# pork_pi.net
KiCad netlist of a schematic drawn in EAGLE
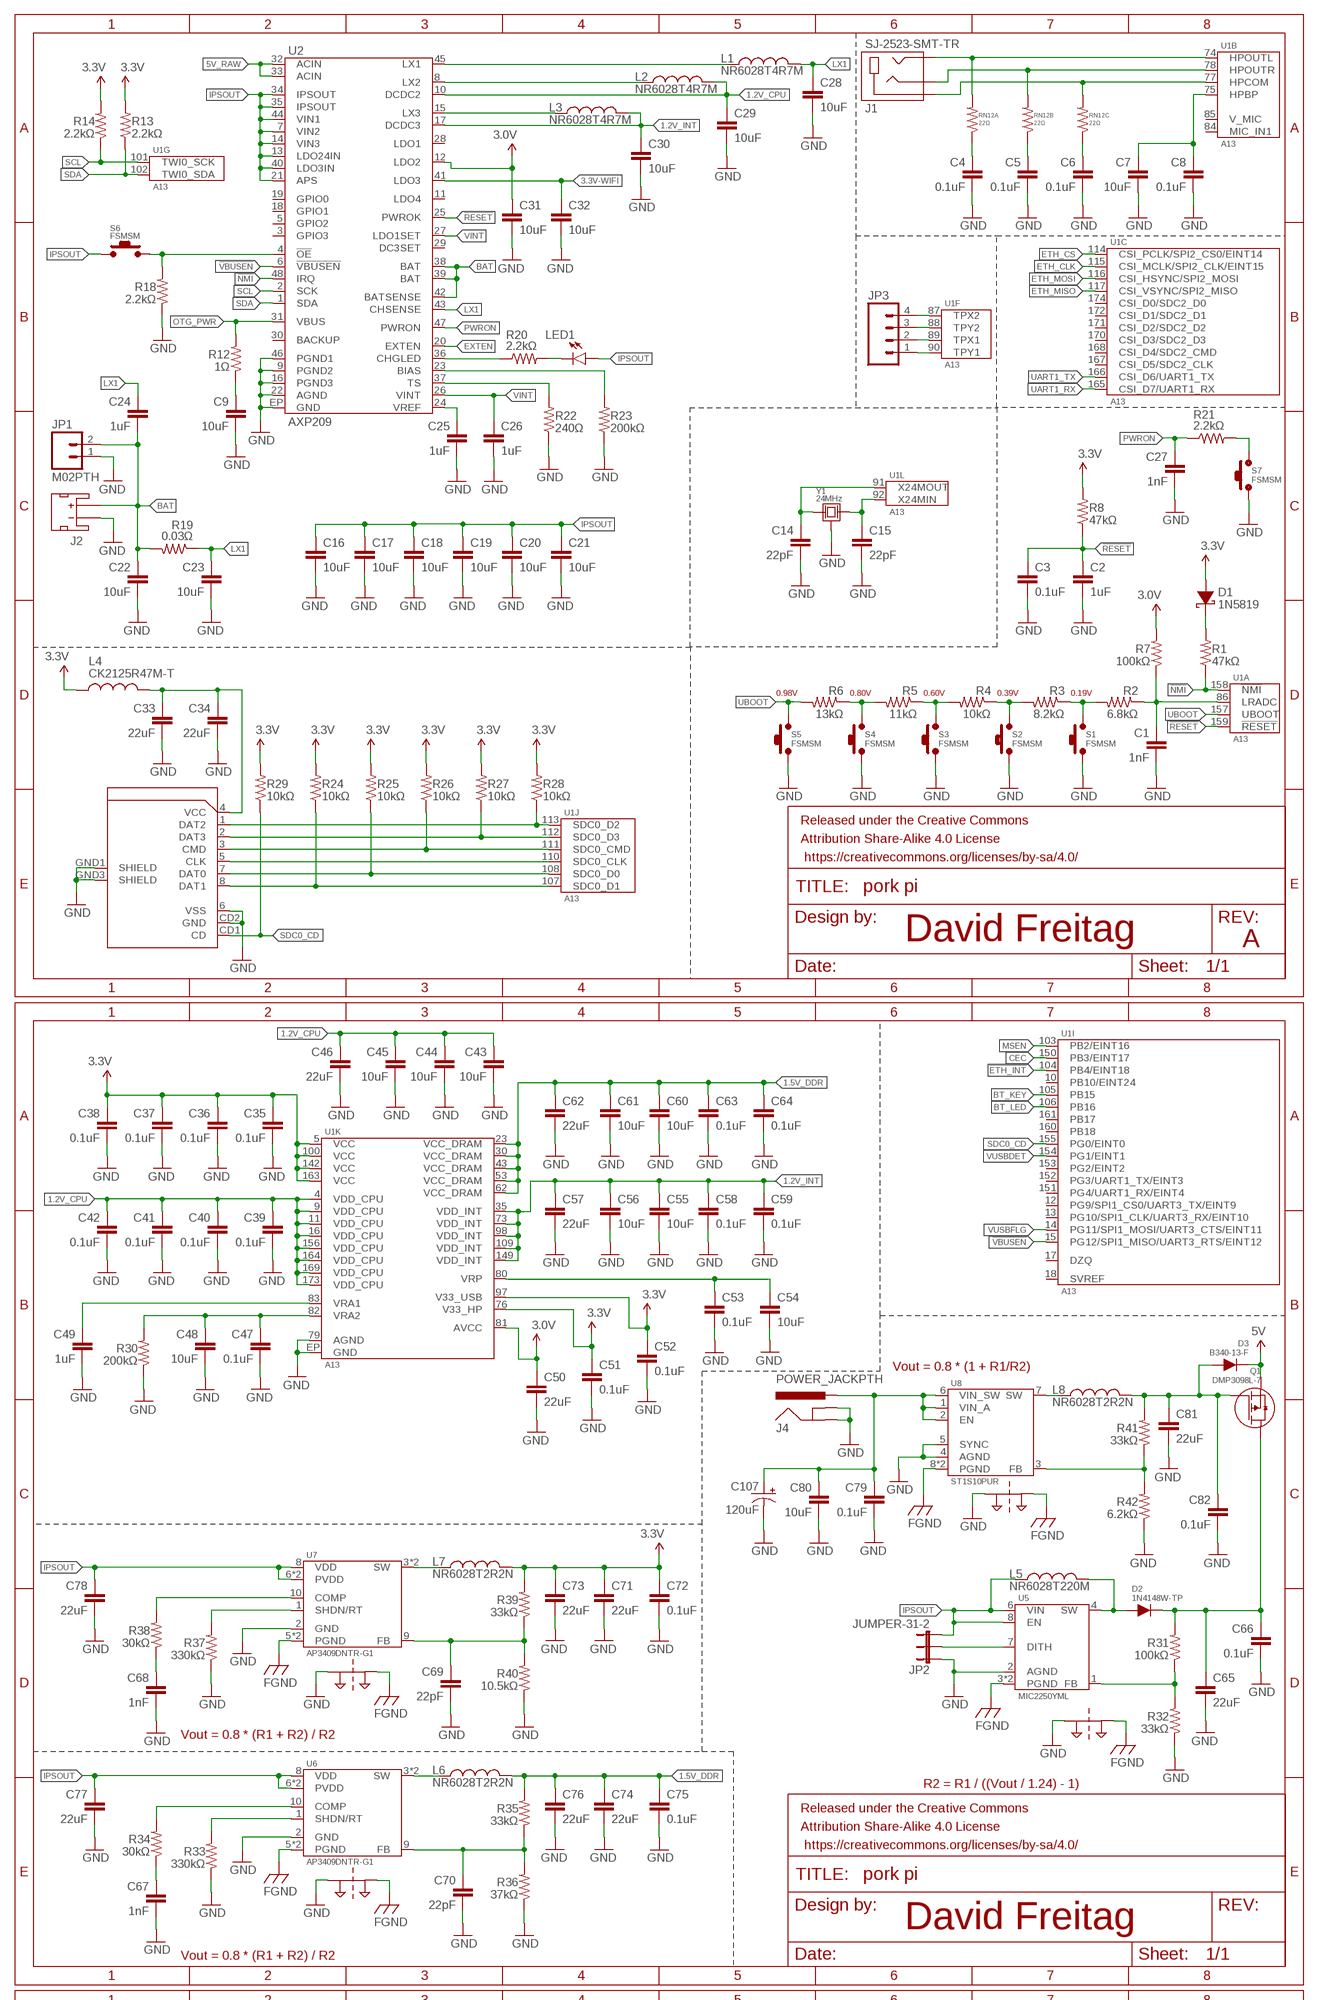
[diagram p0: schematic, sheet 1, part 1 of 3]
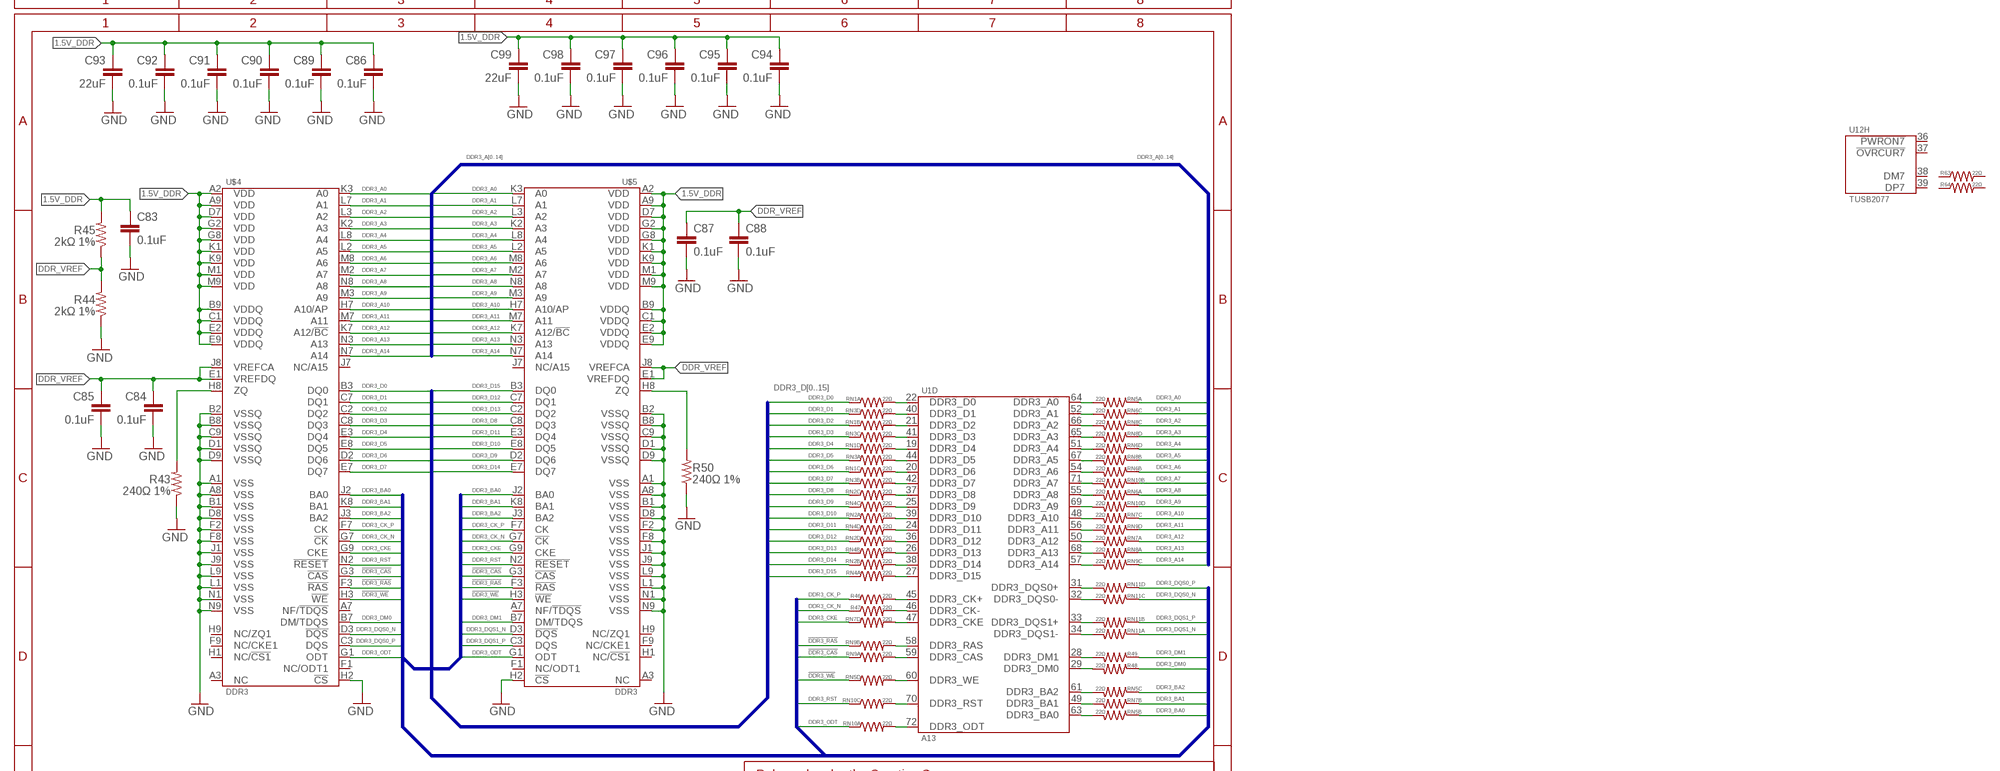
[diagram p1: schematic, sheet 1, part 2 of 3]
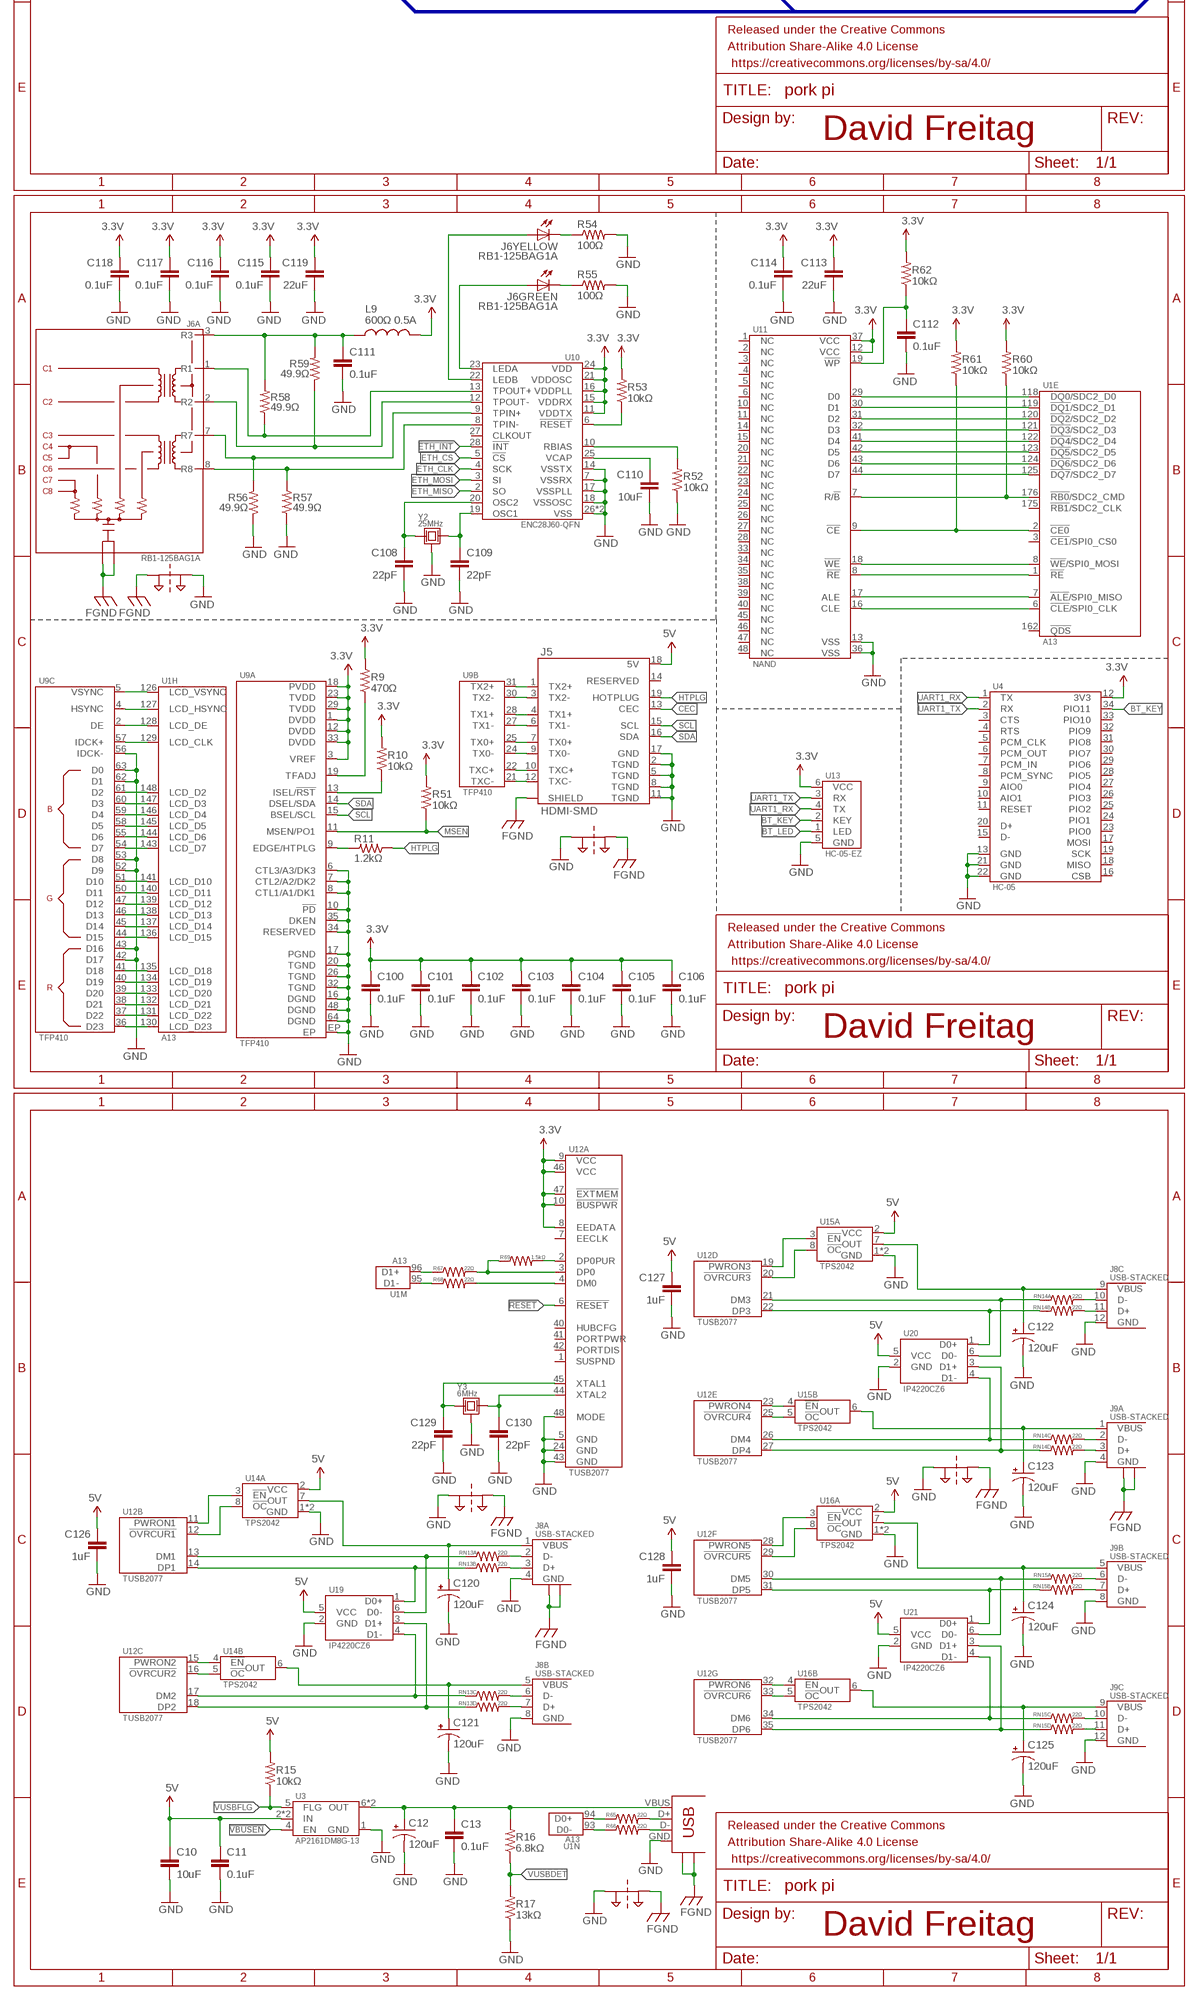
[diagram p2: schematic, sheet 1, part 3 of 3]

(export (version "E")
  (design (tool "Eeschema 10.0.6"))
  (components
    (comp (ref "C1")
      (value "1nF")
      (footprint "eagle-import:0402-CAP")
      (libsource (lib "eagle-import") (part "CAP0402-CAP"))
    )
    (comp (ref "C2")
      (value "1uF")
      (footprint "eagle-import:0402-CAP")
      (libsource (lib "eagle-import") (part "CAP0402-CAP"))
    )
    (comp (ref "C3")
      (value "0.1uF")
      (footprint "eagle-import:0402-CAP")
      (libsource (lib "eagle-import") (part "CAP0402-CAP"))
    )
    (comp (ref "C4")
      (value "0.1uF")
      (footprint "eagle-import:0402-CAP")
      (libsource (lib "eagle-import") (part "CAP0402-CAP"))
    )
    (comp (ref "C5")
      (value "0.1uF")
      (footprint "eagle-import:0402-CAP")
      (libsource (lib "eagle-import") (part "CAP0402-CAP"))
    )
    (comp (ref "C6")
      (value "0.1uF")
      (footprint "eagle-import:0402-CAP")
      (libsource (lib "eagle-import") (part "CAP0402-CAP"))
    )
    (comp (ref "C7")
      (value "10uF")
      (footprint "eagle-import:0603-CAP")
      (libsource (lib "eagle-import") (part "CAP0603-CAP"))
    )
    (comp (ref "C8")
      (value "0.1uF")
      (footprint "eagle-import:0402-CAP")
      (libsource (lib "eagle-import") (part "CAP0402-CAP"))
    )
    (comp (ref "C9")
      (value "10uF")
      (footprint "eagle-import:0603-CAP")
      (libsource (lib "eagle-import") (part "CAP0603-CAP"))
    )
    (comp (ref "C10")
      (value "10uF")
      (footprint "eagle-import:0603-CAP")
      (libsource (lib "eagle-import") (part "CAP0603-CAP"))
    )
    (comp (ref "C11")
      (value "0.1uF")
      (footprint "eagle-import:0402-CAP")
      (libsource (lib "eagle-import") (part "CAP0402-CAP"))
    )
    (comp (ref "C12")
      (value "120uF")
      (footprint "eagle-import:CAP_POLYMER-6.5X6.5")
      (fields (field (name "PARTNUM") "493-7371-1-ND"))
      (libsource (lib "eagle-import") (part "CAP_POL-POLYMER_6.5"))
    )
    (comp (ref "C13")
      (value "0.1uF")
      (footprint "eagle-import:0402-CAP")
      (libsource (lib "eagle-import") (part "CAP0402-CAP"))
    )
    (comp (ref "C14")
      (value "22pF")
      (footprint "eagle-import:0402-CAP")
      (libsource (lib "eagle-import") (part "CAP0402-CAP"))
    )
    (comp (ref "C15")
      (value "22pF")
      (footprint "eagle-import:0402-CAP")
      (libsource (lib "eagle-import") (part "CAP0402-CAP"))
    )
    (comp (ref "C16")
      (value "10uF")
      (footprint "eagle-import:0603-CAP")
      (libsource (lib "eagle-import") (part "CAP0603-CAP"))
    )
    (comp (ref "C17")
      (value "10uF")
      (footprint "eagle-import:0603-CAP")
      (libsource (lib "eagle-import") (part "CAP0603-CAP"))
    )
    (comp (ref "C18")
      (value "10uF")
      (footprint "eagle-import:0603-CAP")
      (libsource (lib "eagle-import") (part "CAP0603-CAP"))
    )
    (comp (ref "C19")
      (value "10uF")
      (footprint "eagle-import:0603-CAP")
      (libsource (lib "eagle-import") (part "CAP0603-CAP"))
    )
    (comp (ref "C20")
      (value "10uF")
      (footprint "eagle-import:0603-CAP")
      (libsource (lib "eagle-import") (part "CAP0603-CAP"))
    )
    (comp (ref "C21")
      (value "10uF")
      (footprint "eagle-import:0603-CAP")
      (libsource (lib "eagle-import") (part "CAP0603-CAP"))
    )
    (comp (ref "C22")
      (value "10uF")
      (footprint "eagle-import:0603-CAP")
      (libsource (lib "eagle-import") (part "CAP0603-CAP"))
    )
    (comp (ref "C23")
      (value "10uF")
      (footprint "eagle-import:0603-CAP")
      (libsource (lib "eagle-import") (part "CAP0603-CAP"))
    )
    (comp (ref "C24")
      (value "1uF")
      (footprint "eagle-import:0402-CAP")
      (libsource (lib "eagle-import") (part "CAP0402-CAP"))
    )
    (comp (ref "C25")
      (value "1uF")
      (footprint "eagle-import:0402-CAP")
      (libsource (lib "eagle-import") (part "CAP0402-CAP"))
    )
    (comp (ref "C26")
      (value "1uF")
      (footprint "eagle-import:0402-CAP")
      (libsource (lib "eagle-import") (part "CAP0402-CAP"))
    )
    (comp (ref "C27")
      (value "1nF")
      (footprint "eagle-import:0402-CAP")
      (libsource (lib "eagle-import") (part "CAP0402-CAP"))
    )
    (comp (ref "C28")
      (value "10uF")
      (footprint "eagle-import:0603-CAP")
      (libsource (lib "eagle-import") (part "CAP0603-CAP"))
    )
    (comp (ref "C29")
      (value "10uF")
      (footprint "eagle-import:0603-CAP")
      (libsource (lib "eagle-import") (part "CAP0603-CAP"))
    )
    (comp (ref "C30")
      (value "10uF")
      (footprint "eagle-import:0603-CAP")
      (libsource (lib "eagle-import") (part "CAP0603-CAP"))
    )
    (comp (ref "C31")
      (value "10uF")
      (footprint "eagle-import:0603-CAP")
      (libsource (lib "eagle-import") (part "CAP0603-CAP"))
    )
    (comp (ref "C32")
      (value "10uF")
      (footprint "eagle-import:0603-CAP")
      (libsource (lib "eagle-import") (part "CAP0603-CAP"))
    )
    (comp (ref "C33")
      (value "22uF")
      (footprint "eagle-import:0603-CAP")
      (libsource (lib "eagle-import") (part "CAP0603-CAP"))
    )
    (comp (ref "C34")
      (value "22uF")
      (footprint "eagle-import:0603-CAP")
      (libsource (lib "eagle-import") (part "CAP0603-CAP"))
    )
    (comp (ref "C35")
      (value "0.1uF")
      (footprint "eagle-import:0402-CAP")
      (libsource (lib "eagle-import") (part "CAP0402-CAP"))
    )
    (comp (ref "C36")
      (value "0.1uF")
      (footprint "eagle-import:0402-CAP")
      (libsource (lib "eagle-import") (part "CAP0402-CAP"))
    )
    (comp (ref "C37")
      (value "0.1uF")
      (footprint "eagle-import:0402-CAP")
      (libsource (lib "eagle-import") (part "CAP0402-CAP"))
    )
    (comp (ref "C38")
      (value "0.1uF")
      (footprint "eagle-import:0402-CAP")
      (libsource (lib "eagle-import") (part "CAP0402-CAP"))
    )
    (comp (ref "C39")
      (value "0.1uF")
      (footprint "eagle-import:0402-CAP")
      (libsource (lib "eagle-import") (part "CAP0402-CAP"))
    )
    (comp (ref "C40")
      (value "0.1uF")
      (footprint "eagle-import:0402-CAP")
      (libsource (lib "eagle-import") (part "CAP0402-CAP"))
    )
    (comp (ref "C41")
      (value "0.1uF")
      (footprint "eagle-import:0402-CAP")
      (libsource (lib "eagle-import") (part "CAP0402-CAP"))
    )
    (comp (ref "C42")
      (value "0.1uF")
      (footprint "eagle-import:0402-CAP")
      (libsource (lib "eagle-import") (part "CAP0402-CAP"))
    )
    (comp (ref "C43")
      (value "10uF")
      (footprint "eagle-import:0603-CAP")
      (libsource (lib "eagle-import") (part "CAP0603-CAP"))
    )
    (comp (ref "C44")
      (value "10uF")
      (footprint "eagle-import:0603-CAP")
      (libsource (lib "eagle-import") (part "CAP0603-CAP"))
    )
    (comp (ref "C45")
      (value "10uF")
      (footprint "eagle-import:0603-CAP")
      (libsource (lib "eagle-import") (part "CAP0603-CAP"))
    )
    (comp (ref "C46")
      (value "22uF")
      (footprint "eagle-import:0603-CAP")
      (libsource (lib "eagle-import") (part "CAP0603-CAP"))
    )
    (comp (ref "C47")
      (value "0.1uF")
      (footprint "eagle-import:0402-CAP")
      (libsource (lib "eagle-import") (part "CAP0402-CAP"))
    )
    (comp (ref "C48")
      (value "10uF")
      (footprint "eagle-import:0603-CAP")
      (libsource (lib "eagle-import") (part "CAP0603-CAP"))
    )
    (comp (ref "C49")
      (value "1uF")
      (footprint "eagle-import:0402-CAP")
      (libsource (lib "eagle-import") (part "CAP0402-CAP"))
    )
    (comp (ref "C50")
      (value "22uF")
      (footprint "eagle-import:0603-CAP")
      (libsource (lib "eagle-import") (part "CAP0603-CAP"))
    )
    (comp (ref "C51")
      (value "0.1uF")
      (footprint "eagle-import:0402-CAP")
      (libsource (lib "eagle-import") (part "CAP0402-CAP"))
    )
    (comp (ref "C52")
      (value "0.1uF")
      (footprint "eagle-import:0402-CAP")
      (libsource (lib "eagle-import") (part "CAP0402-CAP"))
    )
    (comp (ref "C53")
      (value "0.1uF")
      (footprint "eagle-import:0402-CAP")
      (libsource (lib "eagle-import") (part "CAP0402-CAP"))
    )
    (comp (ref "C54")
      (value "10uF")
      (footprint "eagle-import:0603-CAP")
      (libsource (lib "eagle-import") (part "CAP0603-CAP"))
    )
    (comp (ref "C55")
      (value "10uF")
      (footprint "eagle-import:0603-CAP")
      (libsource (lib "eagle-import") (part "CAP0603-CAP"))
    )
    (comp (ref "C56")
      (value "10uF")
      (footprint "eagle-import:0603-CAP")
      (libsource (lib "eagle-import") (part "CAP0603-CAP"))
    )
    (comp (ref "C57")
      (value "22uF")
      (footprint "eagle-import:0603-CAP")
      (libsource (lib "eagle-import") (part "CAP0603-CAP"))
    )
    (comp (ref "C58")
      (value "0.1uF")
      (footprint "eagle-import:0402-CAP")
      (libsource (lib "eagle-import") (part "CAP0402-CAP"))
    )
    (comp (ref "C59")
      (value "0.1uF")
      (footprint "eagle-import:0402-CAP")
      (libsource (lib "eagle-import") (part "CAP0402-CAP"))
    )
    (comp (ref "C60")
      (value "10uF")
      (footprint "eagle-import:0603-CAP")
      (libsource (lib "eagle-import") (part "CAP0603-CAP"))
    )
    (comp (ref "C61")
      (value "10uF")
      (footprint "eagle-import:0603-CAP")
      (libsource (lib "eagle-import") (part "CAP0603-CAP"))
    )
    (comp (ref "C62")
      (value "22uF")
      (footprint "eagle-import:0603-CAP")
      (libsource (lib "eagle-import") (part "CAP0603-CAP"))
    )
    (comp (ref "C63")
      (value "0.1uF")
      (footprint "eagle-import:0402-CAP")
      (libsource (lib "eagle-import") (part "CAP0402-CAP"))
    )
    (comp (ref "C64")
      (value "0.1uF")
      (footprint "eagle-import:0402-CAP")
      (libsource (lib "eagle-import") (part "CAP0402-CAP"))
    )
    (comp (ref "C65")
      (value "22uF")
      (footprint "eagle-import:0603-CAP")
      (libsource (lib "eagle-import") (part "CAP0603-CAP"))
    )
    (comp (ref "C66")
      (value "0.1uF")
      (footprint "eagle-import:0402-CAP")
      (libsource (lib "eagle-import") (part "CAP0402-CAP"))
    )
    (comp (ref "C67")
      (value "1nF")
      (footprint "eagle-import:0402-CAP")
      (libsource (lib "eagle-import") (part "CAP0402-CAP"))
    )
    (comp (ref "C68")
      (value "1nF")
      (footprint "eagle-import:0402-CAP")
      (libsource (lib "eagle-import") (part "CAP0402-CAP"))
    )
    (comp (ref "C69")
      (value "22pF")
      (footprint "eagle-import:0402-CAP")
      (libsource (lib "eagle-import") (part "CAP0402-CAP"))
    )
    (comp (ref "C70")
      (value "22pF")
      (footprint "eagle-import:0402-CAP")
      (libsource (lib "eagle-import") (part "CAP0402-CAP"))
    )
    (comp (ref "C71")
      (value "22uF")
      (footprint "eagle-import:0603-CAP")
      (libsource (lib "eagle-import") (part "CAP0603-CAP"))
    )
    (comp (ref "C72")
      (value "0.1uF")
      (footprint "eagle-import:0402-CAP")
      (libsource (lib "eagle-import") (part "CAP0402-CAP"))
    )
    (comp (ref "C73")
      (value "22uF")
      (footprint "eagle-import:0603-CAP")
      (libsource (lib "eagle-import") (part "CAP0603-CAP"))
    )
    (comp (ref "C74")
      (value "22uF")
      (footprint "eagle-import:0603-CAP")
      (libsource (lib "eagle-import") (part "CAP0603-CAP"))
    )
    (comp (ref "C75")
      (value "0.1uF")
      (footprint "eagle-import:0402-CAP")
      (libsource (lib "eagle-import") (part "CAP0402-CAP"))
    )
    (comp (ref "C76")
      (value "22uF")
      (footprint "eagle-import:0603-CAP")
      (libsource (lib "eagle-import") (part "CAP0603-CAP"))
    )
    (comp (ref "C77")
      (value "22uF")
      (footprint "eagle-import:0603-CAP")
      (libsource (lib "eagle-import") (part "CAP0603-CAP"))
    )
    (comp (ref "C78")
      (value "22uF")
      (footprint "eagle-import:0603-CAP")
      (libsource (lib "eagle-import") (part "CAP0603-CAP"))
    )
    (comp (ref "C79")
      (value "0.1uF")
      (footprint "eagle-import:0402-CAP")
      (libsource (lib "eagle-import") (part "CAP0402-CAP"))
    )
    (comp (ref "C80")
      (value "10uF")
      (footprint "eagle-import:0603-CAP")
      (libsource (lib "eagle-import") (part "CAP0603-CAP"))
    )
    (comp (ref "C81")
      (value "22uF")
      (footprint "eagle-import:0603-CAP")
      (libsource (lib "eagle-import") (part "CAP0603-CAP"))
    )
    (comp (ref "C82")
      (value "0.1uF")
      (footprint "eagle-import:0402-CAP")
      (libsource (lib "eagle-import") (part "CAP0402-CAP"))
    )
    (comp (ref "C83")
      (value "0.1uF")
      (footprint "eagle-import:0402-CAP")
      (libsource (lib "eagle-import") (part "CAP0402-CAP"))
    )
    (comp (ref "C84")
      (value "0.1uF")
      (footprint "eagle-import:0402-CAP")
      (libsource (lib "eagle-import") (part "CAP0402-CAP"))
    )
    (comp (ref "C85")
      (value "0.1uF")
      (footprint "eagle-import:0402-CAP")
      (libsource (lib "eagle-import") (part "CAP0402-CAP"))
    )
    (comp (ref "C86")
      (value "0.1uF")
      (footprint "eagle-import:0402-CAP")
      (libsource (lib "eagle-import") (part "CAP0402-CAP"))
    )
    (comp (ref "C87")
      (value "0.1uF")
      (footprint "eagle-import:0402-CAP")
      (libsource (lib "eagle-import") (part "CAP0402-CAP"))
    )
    (comp (ref "C88")
      (value "0.1uF")
      (footprint "eagle-import:0402-CAP")
      (libsource (lib "eagle-import") (part "CAP0402-CAP"))
    )
    (comp (ref "C89")
      (value "0.1uF")
      (footprint "eagle-import:0402-CAP")
      (libsource (lib "eagle-import") (part "CAP0402-CAP"))
    )
    (comp (ref "C90")
      (value "0.1uF")
      (footprint "eagle-import:0402-CAP")
      (libsource (lib "eagle-import") (part "CAP0402-CAP"))
    )
    (comp (ref "C91")
      (value "0.1uF")
      (footprint "eagle-import:0402-CAP")
      (libsource (lib "eagle-import") (part "CAP0402-CAP"))
    )
    (comp (ref "C92")
      (value "0.1uF")
      (footprint "eagle-import:0402-CAP")
      (libsource (lib "eagle-import") (part "CAP0402-CAP"))
    )
    (comp (ref "C93")
      (value "22uF")
      (footprint "eagle-import:0603-CAP")
      (libsource (lib "eagle-import") (part "CAP0603-CAP"))
    )
    (comp (ref "C94")
      (value "0.1uF")
      (footprint "eagle-import:0402-CAP")
      (libsource (lib "eagle-import") (part "CAP0402-CAP"))
    )
    (comp (ref "C95")
      (value "0.1uF")
      (footprint "eagle-import:0402-CAP")
      (libsource (lib "eagle-import") (part "CAP0402-CAP"))
    )
    (comp (ref "C96")
      (value "0.1uF")
      (footprint "eagle-import:0402-CAP")
      (libsource (lib "eagle-import") (part "CAP0402-CAP"))
    )
    (comp (ref "C97")
      (value "0.1uF")
      (footprint "eagle-import:0402-CAP")
      (libsource (lib "eagle-import") (part "CAP0402-CAP"))
    )
    (comp (ref "C98")
      (value "0.1uF")
      (footprint "eagle-import:0402-CAP")
      (libsource (lib "eagle-import") (part "CAP0402-CAP"))
    )
    (comp (ref "C99")
      (value "22uF")
      (footprint "eagle-import:0603-CAP")
      (libsource (lib "eagle-import") (part "CAP0603-CAP"))
    )
    (comp (ref "C100")
      (value "0.1uF")
      (footprint "eagle-import:0402-CAP")
      (libsource (lib "eagle-import") (part "CAP0402-CAP"))
    )
    (comp (ref "C101")
      (value "0.1uF")
      (footprint "eagle-import:0402-CAP")
      (libsource (lib "eagle-import") (part "CAP0402-CAP"))
    )
    (comp (ref "C102")
      (value "0.1uF")
      (footprint "eagle-import:0402-CAP")
      (libsource (lib "eagle-import") (part "CAP0402-CAP"))
    )
    (comp (ref "C103")
      (value "0.1uF")
      (footprint "eagle-import:0402-CAP")
      (libsource (lib "eagle-import") (part "CAP0402-CAP"))
    )
    (comp (ref "C104")
      (value "0.1uF")
      (footprint "eagle-import:0402-CAP")
      (libsource (lib "eagle-import") (part "CAP0402-CAP"))
    )
    (comp (ref "C105")
      (value "0.1uF")
      (footprint "eagle-import:0402-CAP")
      (libsource (lib "eagle-import") (part "CAP0402-CAP"))
    )
    (comp (ref "C106")
      (value "0.1uF")
      (footprint "eagle-import:0402-CAP")
      (libsource (lib "eagle-import") (part "CAP0402-CAP"))
    )
    (comp (ref "C107")
      (value "120uF")
      (footprint "eagle-import:CAP_POLYMER-6.5X6.5")
      (fields (field (name "PARTNUM") "493-7371-1-ND"))
      (libsource (lib "eagle-import") (part "CAP_POL-POLYMER_6.5"))
    )
    (comp (ref "C108")
      (value "22pF")
      (footprint "eagle-import:0402-CAP")
      (libsource (lib "eagle-import") (part "CAP0402-CAP"))
    )
    (comp (ref "C109")
      (value "22pF")
      (footprint "eagle-import:0402-CAP")
      (libsource (lib "eagle-import") (part "CAP0402-CAP"))
    )
    (comp (ref "C110")
      (value "10uF")
      (footprint "eagle-import:0603-CAP")
      (libsource (lib "eagle-import") (part "CAP0603-CAP"))
    )
    (comp (ref "C111")
      (value "0.1uF")
      (footprint "eagle-import:0402-CAP")
      (libsource (lib "eagle-import") (part "CAP0402-CAP"))
    )
    (comp (ref "C112")
      (value "0.1uF")
      (footprint "eagle-import:0402-CAP")
      (libsource (lib "eagle-import") (part "CAP0402-CAP"))
    )
    (comp (ref "C113")
      (value "22uF")
      (footprint "eagle-import:0603-CAP")
      (libsource (lib "eagle-import") (part "CAP0603-CAP"))
    )
    (comp (ref "C114")
      (value "0.1uF")
      (footprint "eagle-import:0402-CAP")
      (libsource (lib "eagle-import") (part "CAP0402-CAP"))
    )
    (comp (ref "C115")
      (value "0.1uF")
      (footprint "eagle-import:0402-CAP")
      (libsource (lib "eagle-import") (part "CAP0402-CAP"))
    )
    (comp (ref "C116")
      (value "0.1uF")
      (footprint "eagle-import:0402-CAP")
      (libsource (lib "eagle-import") (part "CAP0402-CAP"))
    )
    (comp (ref "C117")
      (value "0.1uF")
      (footprint "eagle-import:0402-CAP")
      (libsource (lib "eagle-import") (part "CAP0402-CAP"))
    )
    (comp (ref "C118")
      (value "0.1uF")
      (footprint "eagle-import:0402-CAP")
      (libsource (lib "eagle-import") (part "CAP0402-CAP"))
    )
    (comp (ref "C119")
      (value "22uF")
      (footprint "eagle-import:0603-CAP")
      (libsource (lib "eagle-import") (part "CAP0603-CAP"))
    )
    (comp (ref "C120")
      (value "120uF")
      (footprint "eagle-import:CAP_POLYMER-6.5X6.5")
      (fields (field (name "PARTNUM") "493-7371-1-ND"))
      (libsource (lib "eagle-import") (part "CAP_POL-POLYMER_6.5"))
    )
    (comp (ref "C121")
      (value "120uF")
      (footprint "eagle-import:CAP_POLYMER-6.5X6.5")
      (fields (field (name "PARTNUM") "493-7371-1-ND"))
      (libsource (lib "eagle-import") (part "CAP_POL-POLYMER_6.5"))
    )
    (comp (ref "C122")
      (value "120uF")
      (footprint "eagle-import:CAP_POLYMER-6.5X6.5")
      (fields (field (name "PARTNUM") "493-7371-1-ND"))
      (libsource (lib "eagle-import") (part "CAP_POL-POLYMER_6.5"))
    )
    (comp (ref "C123")
      (value "120uF")
      (footprint "eagle-import:CAP_POLYMER-6.5X6.5")
      (fields (field (name "PARTNUM") "493-7371-1-ND"))
      (libsource (lib "eagle-import") (part "CAP_POL-POLYMER_6.5"))
    )
    (comp (ref "C124")
      (value "120uF")
      (footprint "eagle-import:CAP_POLYMER-6.5X6.5")
      (fields (field (name "PARTNUM") "493-7371-1-ND"))
      (libsource (lib "eagle-import") (part "CAP_POL-POLYMER_6.5"))
    )
    (comp (ref "C125")
      (value "120uF")
      (footprint "eagle-import:CAP_POLYMER-6.5X6.5")
      (fields (field (name "PARTNUM") "493-7371-1-ND"))
      (libsource (lib "eagle-import") (part "CAP_POL-POLYMER_6.5"))
    )
    (comp (ref "C126")
      (value "1uF")
      (footprint "eagle-import:0402-CAP")
      (libsource (lib "eagle-import") (part "CAP0402-CAP"))
    )
    (comp (ref "C127")
      (value "1uF")
      (footprint "eagle-import:0402-CAP")
      (libsource (lib "eagle-import") (part "CAP0402-CAP"))
    )
    (comp (ref "C128")
      (value "1uF")
      (footprint "eagle-import:0402-CAP")
      (libsource (lib "eagle-import") (part "CAP0402-CAP"))
    )
    (comp (ref "C129")
      (value "22pF")
      (footprint "eagle-import:0402-CAP")
      (libsource (lib "eagle-import") (part "CAP0402-CAP"))
    )
    (comp (ref "C130")
      (value "22pF")
      (footprint "eagle-import:0402-CAP")
      (libsource (lib "eagle-import") (part "CAP0402-CAP"))
    )
    (comp (ref "D1")
      (value "1N5819")
      (footprint "eagle-import:SOD123")
      (libsource (lib "eagle-import") (part "1N5819-SOD123"))
    )
    (comp (ref "D2")
      (value "1N4148W-TP")
      (footprint "eagle-import:SOD-123")
      (libsource (lib "eagle-import") (part "DIODE"))
    )
    (comp (ref "D3")
      (value "B340-13-F")
      (footprint "eagle-import:SMC")
      (libsource (lib "eagle-import") (part "B340-13-F"))
    )
    (comp (ref "J1")
      (value "SJ-2523-SMT-TR")
      (footprint "eagle-import:SJ-2523-SMT-TR")
      (libsource (lib "eagle-import") (part "SJ-2523-SMT-TR"))
    )
    (comp (ref "J2")
      (value "JST_2MM_MALE")
      (footprint "eagle-import:JST-2-SMD")
      (libsource (lib "eagle-import") (part "JST_2MM_MALE"))
    )
    (comp (ref "J3")
      (value "MICRO-SD")
      (footprint "eagle-import:MICRO-SD-SOCKET-PP")
      (libsource (lib "eagle-import") (part "MICRO-SD"))
    )
    (comp (ref "J4")
      (value "POWER_JACKPTH")
      (footprint "eagle-import:POWER_JACK_PTH")
      (libsource (lib "eagle-import") (part "POWER_JACKPTH"))
    )
    (comp (ref "J5")
      (value "HDMI-SMD")
      (footprint "eagle-import:HDMI-SMD")
      (libsource (lib "eagle-import") (part "HDMI-SMD"))
    )
    (comp (ref "J6")
      (value "RB1-125BAG1A")
      (footprint "eagle-import:ETHERNET")
      (libsource (lib "eagle-import") (part "RB1-125BAG1A"))
    )
    (comp (ref "J7")
      (value "USB+SHIELD-MICROB")
      (footprint "eagle-import:USB-MICROB")
      (libsource (lib "eagle-import") (part "USB+SHIELD-MICROB"))
    )
    (comp (ref "J8")
      (value "USB-STACKED")
      (footprint "eagle-import:USB-STACKED")
      (libsource (lib "eagle-import") (part "USB-STACKED"))
    )
    (comp (ref "J9")
      (value "USB-STACKED")
      (footprint "eagle-import:USB-STACKED")
      (libsource (lib "eagle-import") (part "USB-STACKED"))
    )
    (comp (ref "JP1")
      (value "M02PTH")
      (footprint "eagle-import:1X02")
      (libsource (lib "eagle-import") (part "M02PTH"))
    )
    (comp (ref "JP2")
      (value "JUMPER-31-2")
      (footprint "eagle-import:SJ_3_PASTE1&2")
      (libsource (lib "eagle-import") (part "JUMPER-31-2"))
    )
    (comp (ref "JP3")
      (value "M04PTH")
      (footprint "eagle-import:1X04")
      (libsource (lib "eagle-import") (part "M04PTH"))
    )
    (comp (ref "L1")
      (value "NR6028T4R7M")
      (footprint "eagle-import:NR6028T4R7M")
      (libsource (lib "eagle-import") (part "NR6028T4R7M"))
    )
    (comp (ref "L2")
      (value "NR6028T4R7M")
      (footprint "eagle-import:NR6028T4R7M")
      (libsource (lib "eagle-import") (part "NR6028T4R7M"))
    )
    (comp (ref "L3")
      (value "NR6028T4R7M")
      (footprint "eagle-import:NR6028T4R7M")
      (libsource (lib "eagle-import") (part "NR6028T4R7M"))
    )
    (comp (ref "L4")
      (value "CK2125R47M-T")
      (footprint "eagle-import:0805")
      (libsource (lib "eagle-import") (part "INDUCTOR0805"))
    )
    (comp (ref "L5")
      (value "NR6028T220M")
      (footprint "eagle-import:NR6028T4R7M")
      (libsource (lib "eagle-import") (part "NR6028T4R7M"))
    )
    (comp (ref "L6")
      (value "NR6028T2R2N")
      (footprint "eagle-import:NR6028T4R7M")
      (libsource (lib "eagle-import") (part "NR6028T4R7M"))
    )
    (comp (ref "L7")
      (value "NR6028T2R2N")
      (footprint "eagle-import:NR6028T4R7M")
      (libsource (lib "eagle-import") (part "NR6028T4R7M"))
    )
    (comp (ref "L8")
      (value "NR6028T2R2N")
      (footprint "eagle-import:NR6028T4R7M")
      (libsource (lib "eagle-import") (part "NR6028T4R7M"))
    )
    (comp (ref "L9")
      (value "600Ω 0.5A")
      (footprint "eagle-import:0805")
      (libsource (lib "eagle-import") (part "INDUCTOR0805"))
    )
    (comp (ref "LED1")
      (value "LED1206")
      (footprint "eagle-import:LED-1206")
      (libsource (lib "eagle-import") (part "LED1206"))
    )
    (comp (ref "PT1")
      (value "2PT_GND_TIE")
      (footprint "eagle-import:2PT_GND_TIE")
      (libsource (lib "eagle-import") (part "2PT_GND_TIE"))
    )
    (comp (ref "PT2")
      (value "2PT_GND_TIE")
      (footprint "eagle-import:2PT_GND_TIE")
      (libsource (lib "eagle-import") (part "2PT_GND_TIE"))
    )
    (comp (ref "PT3")
      (value "2PT_GND_TIE")
      (footprint "eagle-import:2PT_GND_TIE")
      (libsource (lib "eagle-import") (part "2PT_GND_TIE"))
    )
    (comp (ref "PT4")
      (value "2PT_GND_TIE")
      (footprint "eagle-import:2PT_GND_TIE")
      (libsource (lib "eagle-import") (part "2PT_GND_TIE"))
    )
    (comp (ref "PT5")
      (value "2PT_GND_TIE")
      (footprint "eagle-import:2PT_GND_TIE")
      (libsource (lib "eagle-import") (part "2PT_GND_TIE"))
    )
    (comp (ref "PT6")
      (value "2PT_GND_TIE")
      (footprint "eagle-import:2PT_GND_TIE")
      (libsource (lib "eagle-import") (part "2PT_GND_TIE"))
    )
    (comp (ref "PT7")
      (value "2PT_GND_TIE")
      (footprint "eagle-import:2PT_GND_TIE")
      (libsource (lib "eagle-import") (part "2PT_GND_TIE"))
    )
    (comp (ref "PT8")
      (value "2PT_GND_TIE")
      (footprint "eagle-import:2PT_GND_TIE")
      (libsource (lib "eagle-import") (part "2PT_GND_TIE"))
    )
    (comp (ref "PT9")
      (value "2PT_GND_TIE")
      (footprint "eagle-import:2PT_GND_TIE")
      (libsource (lib "eagle-import") (part "2PT_GND_TIE"))
    )
    (comp (ref "Q1")
      (value "DMP3098L-7")
      (footprint "eagle-import:SOT23-3")
      (libsource (lib "eagle-import") (part "DMP3098L-7"))
    )
    (comp (ref "R1")
      (value "47kΩ")
      (footprint "eagle-import:0402-RES")
      (libsource (lib "eagle-import") (part "RESISTOR0402-RES"))
    )
    (comp (ref "R2")
      (value "6.8kΩ")
      (footprint "eagle-import:0402-RES")
      (libsource (lib "eagle-import") (part "RESISTOR0402-RES"))
    )
    (comp (ref "R3")
      (value "8.2kΩ")
      (footprint "eagle-import:0402-RES")
      (libsource (lib "eagle-import") (part "RESISTOR0402-RES"))
    )
    (comp (ref "R4")
      (value "10kΩ")
      (footprint "eagle-import:0402-RES")
      (libsource (lib "eagle-import") (part "RESISTOR0402-RES"))
    )
    (comp (ref "R5")
      (value "11kΩ")
      (footprint "eagle-import:0402-RES")
      (libsource (lib "eagle-import") (part "RESISTOR0402-RES"))
    )
    (comp (ref "R6")
      (value "13kΩ")
      (footprint "eagle-import:0402-RES")
      (libsource (lib "eagle-import") (part "RESISTOR0402-RES"))
    )
    (comp (ref "R7")
      (value "100kΩ")
      (footprint "eagle-import:0402-RES")
      (libsource (lib "eagle-import") (part "RESISTOR0402-RES"))
    )
    (comp (ref "R8")
      (value "47kΩ")
      (footprint "eagle-import:0402-RES")
      (libsource (lib "eagle-import") (part "RESISTOR0402-RES"))
    )
    (comp (ref "R9")
      (value "470Ω")
      (footprint "eagle-import:0402-RES")
      (libsource (lib "eagle-import") (part "RESISTOR0402-RES"))
    )
    (comp (ref "R10")
      (value "10kΩ")
      (footprint "eagle-import:0402-RES")
      (libsource (lib "eagle-import") (part "RESISTOR0402-RES"))
    )
    (comp (ref "R11")
      (value "1.2kΩ")
      (footprint "eagle-import:0402-RES")
      (libsource (lib "eagle-import") (part "RESISTOR0402-RES"))
    )
    (comp (ref "R12")
      (value "1Ω")
      (footprint "eagle-import:0402-RES")
      (libsource (lib "eagle-import") (part "RESISTOR0402-RES"))
    )
    (comp (ref "R13")
      (value "2.2kΩ")
      (footprint "eagle-import:0402-RES")
      (libsource (lib "eagle-import") (part "RESISTOR0402-RES"))
    )
    (comp (ref "R14")
      (value "2.2kΩ")
      (footprint "eagle-import:0402-RES")
      (libsource (lib "eagle-import") (part "RESISTOR0402-RES"))
    )
    (comp (ref "R15")
      (value "10kΩ")
      (footprint "eagle-import:0402-RES")
      (libsource (lib "eagle-import") (part "RESISTOR0402-RES"))
    )
    (comp (ref "R16")
      (value "6.8kΩ")
      (footprint "eagle-import:0402-RES")
      (libsource (lib "eagle-import") (part "RESISTOR0402-RES"))
    )
    (comp (ref "R17")
      (value "13kΩ")
      (footprint "eagle-import:0402-RES")
      (libsource (lib "eagle-import") (part "RESISTOR0402-RES"))
    )
    (comp (ref "R18")
      (value "2.2kΩ")
      (footprint "eagle-import:0402-RES")
      (libsource (lib "eagle-import") (part "RESISTOR0402-RES"))
    )
    (comp (ref "R19")
      (value "0.03Ω")
      (footprint "eagle-import:0805")
      (libsource (lib "eagle-import") (part "RESISTOR0805-RES"))
    )
    (comp (ref "R20")
      (value "2.2kΩ")
      (footprint "eagle-import:0402-RES")
      (libsource (lib "eagle-import") (part "RESISTOR0402-RES"))
    )
    (comp (ref "R21")
      (value "2.2kΩ")
      (footprint "eagle-import:0402-RES")
      (libsource (lib "eagle-import") (part "RESISTOR0402-RES"))
    )
    (comp (ref "R22")
      (value "240Ω")
      (footprint "eagle-import:0402-RES")
      (libsource (lib "eagle-import") (part "RESISTOR0402-RES"))
    )
    (comp (ref "R23")
      (value "200kΩ")
      (footprint "eagle-import:0402-RES")
      (libsource (lib "eagle-import") (part "RESISTOR0402-RES"))
    )
    (comp (ref "R24")
      (value "10kΩ")
      (footprint "eagle-import:0402-RES")
      (libsource (lib "eagle-import") (part "RESISTOR0402-RES"))
    )
    (comp (ref "R25")
      (value "10kΩ")
      (footprint "eagle-import:0402-RES")
      (libsource (lib "eagle-import") (part "RESISTOR0402-RES"))
    )
    (comp (ref "R26")
      (value "10kΩ")
      (footprint "eagle-import:0402-RES")
      (libsource (lib "eagle-import") (part "RESISTOR0402-RES"))
    )
    (comp (ref "R27")
      (value "10kΩ")
      (footprint "eagle-import:0402-RES")
      (libsource (lib "eagle-import") (part "RESISTOR0402-RES"))
    )
    (comp (ref "R28")
      (value "10kΩ")
      (footprint "eagle-import:0402-RES")
      (libsource (lib "eagle-import") (part "RESISTOR0402-RES"))
    )
    (comp (ref "R29")
      (value "10kΩ")
      (footprint "eagle-import:0402-RES")
      (libsource (lib "eagle-import") (part "RESISTOR0402-RES"))
    )
    (comp (ref "R30")
      (value "200kΩ")
      (footprint "eagle-import:0402-RES")
      (libsource (lib "eagle-import") (part "RESISTOR0402-RES"))
    )
    (comp (ref "R31")
      (value "100kΩ")
      (footprint "eagle-import:0402-RES")
      (libsource (lib "eagle-import") (part "RESISTOR0402-RES"))
    )
    (comp (ref "R32")
      (value "33kΩ")
      (footprint "eagle-import:0402-RES")
      (libsource (lib "eagle-import") (part "RESISTOR0402-RES"))
    )
    (comp (ref "R33")
      (value "330kΩ")
      (footprint "eagle-import:0402-RES")
      (libsource (lib "eagle-import") (part "RESISTOR0402-RES"))
    )
    (comp (ref "R34")
      (value "30kΩ")
      (footprint "eagle-import:0402-RES")
      (libsource (lib "eagle-import") (part "RESISTOR0402-RES"))
    )
    (comp (ref "R35")
      (value "33kΩ")
      (footprint "eagle-import:0402-RES")
      (libsource (lib "eagle-import") (part "RESISTOR0402-RES"))
    )
    (comp (ref "R36")
      (value "37kΩ")
      (footprint "eagle-import:0402-RES")
      (libsource (lib "eagle-import") (part "RESISTOR0402-RES"))
    )
    (comp (ref "R37")
      (value "330kΩ")
      (footprint "eagle-import:0402-RES")
      (libsource (lib "eagle-import") (part "RESISTOR0402-RES"))
    )
    (comp (ref "R38")
      (value "30kΩ")
      (footprint "eagle-import:0402-RES")
      (libsource (lib "eagle-import") (part "RESISTOR0402-RES"))
    )
    (comp (ref "R39")
      (value "33kΩ")
      (footprint "eagle-import:0402-RES")
      (libsource (lib "eagle-import") (part "RESISTOR0402-RES"))
    )
    (comp (ref "R40")
      (value "10.5kΩ")
      (footprint "eagle-import:0402-RES")
      (libsource (lib "eagle-import") (part "RESISTOR0402-RES"))
    )
    (comp (ref "R41")
      (value "33kΩ")
      (footprint "eagle-import:0402-RES")
      (libsource (lib "eagle-import") (part "RESISTOR0402-RES"))
    )
    (comp (ref "R42")
      (value "6.2kΩ")
      (footprint "eagle-import:0402-RES")
      (libsource (lib "eagle-import") (part "RESISTOR0402-RES"))
    )
    (comp (ref "R43")
      (value "240Ω 1%")
      (footprint "eagle-import:0402-RES")
      (libsource (lib "eagle-import") (part "RESISTOR0402-RES"))
    )
    (comp (ref "R44")
      (value "2kΩ 1%")
      (footprint "eagle-import:0402-RES")
      (libsource (lib "eagle-import") (part "RESISTOR0402-RES"))
    )
    (comp (ref "R45")
      (value "2kΩ 1%")
      (footprint "eagle-import:0402-RES")
      (libsource (lib "eagle-import") (part "RESISTOR0402-RES"))
    )
    (comp (ref "R46")
      (value "22Ω")
      (footprint "eagle-import:0402-RES")
      (libsource (lib "eagle-import") (part "RESISTOR0402-RES"))
    )
    (comp (ref "R47")
      (value "22Ω")
      (footprint "eagle-import:0402-RES")
      (libsource (lib "eagle-import") (part "RESISTOR0402-RES"))
    )
    (comp (ref "R48")
      (value "22Ω")
      (footprint "eagle-import:0402-RES")
      (libsource (lib "eagle-import") (part "RESISTOR0402-RES"))
    )
    (comp (ref "R49")
      (value "22Ω")
      (footprint "eagle-import:0402-RES")
      (libsource (lib "eagle-import") (part "RESISTOR0402-RES"))
    )
    (comp (ref "R50")
      (value "240Ω 1%")
      (footprint "eagle-import:0402-RES")
      (libsource (lib "eagle-import") (part "RESISTOR0402-RES"))
    )
    (comp (ref "R51")
      (value "10kΩ")
      (footprint "eagle-import:0402-RES")
      (libsource (lib "eagle-import") (part "RESISTOR0402-RES"))
    )
    (comp (ref "R52")
      (value "10kΩ")
      (footprint "eagle-import:0402-RES")
      (libsource (lib "eagle-import") (part "RESISTOR0402-RES"))
    )
    (comp (ref "R53")
      (value "10kΩ")
      (footprint "eagle-import:0402-RES")
      (libsource (lib "eagle-import") (part "RESISTOR0402-RES"))
    )
    (comp (ref "R54")
      (value "100Ω")
      (footprint "eagle-import:0402-RES")
      (libsource (lib "eagle-import") (part "RESISTOR0402-RES"))
    )
    (comp (ref "R55")
      (value "100Ω")
      (footprint "eagle-import:0402-RES")
      (libsource (lib "eagle-import") (part "RESISTOR0402-RES"))
    )
    (comp (ref "R56")
      (value "49.9Ω")
      (footprint "eagle-import:0805")
      (libsource (lib "eagle-import") (part "RESISTOR0805-RES"))
    )
    (comp (ref "R57")
      (value "49.9Ω")
      (footprint "eagle-import:0805")
      (libsource (lib "eagle-import") (part "RESISTOR0805-RES"))
    )
    (comp (ref "R58")
      (value "49.9Ω")
      (footprint "eagle-import:0805")
      (libsource (lib "eagle-import") (part "RESISTOR0805-RES"))
    )
    (comp (ref "R59")
      (value "49.9Ω")
      (footprint "eagle-import:0805")
      (libsource (lib "eagle-import") (part "RESISTOR0805-RES"))
    )
    (comp (ref "R60")
      (value "10kΩ")
      (footprint "eagle-import:0402-RES")
      (libsource (lib "eagle-import") (part "RESISTOR0402-RES"))
    )
    (comp (ref "R61")
      (value "10kΩ")
      (footprint "eagle-import:0402-RES")
      (libsource (lib "eagle-import") (part "RESISTOR0402-RES"))
    )
    (comp (ref "R62")
      (value "10kΩ")
      (footprint "eagle-import:0402-RES")
      (libsource (lib "eagle-import") (part "RESISTOR0402-RES"))
    )
    (comp (ref "R63")
      (value "22Ω")
      (footprint "eagle-import:0402-RES")
      (libsource (lib "eagle-import") (part "RESISTOR0402-RES"))
    )
    (comp (ref "R64")
      (value "22Ω")
      (footprint "eagle-import:0402-RES")
      (libsource (lib "eagle-import") (part "RESISTOR0402-RES"))
    )
    (comp (ref "R65")
      (value "22Ω")
      (footprint "eagle-import:0402-RES")
      (libsource (lib "eagle-import") (part "RESISTOR0402-RES"))
    )
    (comp (ref "R66")
      (value "22Ω")
      (footprint "eagle-import:0402-RES")
      (libsource (lib "eagle-import") (part "RESISTOR0402-RES"))
    )
    (comp (ref "R67")
      (value "22Ω")
      (footprint "eagle-import:0402-RES")
      (libsource (lib "eagle-import") (part "RESISTOR0402-RES"))
    )
    (comp (ref "R68")
      (value "22Ω")
      (footprint "eagle-import:0402-RES")
      (libsource (lib "eagle-import") (part "RESISTOR0402-RES"))
    )
    (comp (ref "R69")
      (value "1.5kΩ")
      (footprint "eagle-import:0402-RES")
      (libsource (lib "eagle-import") (part "RESISTOR0402-RES"))
    )
    (comp (ref "RN1")
      (value "22Ω")
      (footprint "eagle-import:RESISTOR_NETWORK-1206")
      (libsource (lib "eagle-import") (part "RESISTOR-NETWORK-1206"))
    )
    (comp (ref "RN2")
      (value "22Ω")
      (footprint "eagle-import:RESISTOR_NETWORK-1206")
      (libsource (lib "eagle-import") (part "RESISTOR-NETWORK-1206"))
    )
    (comp (ref "RN3")
      (value "22Ω")
      (footprint "eagle-import:RESISTOR_NETWORK-1206")
      (libsource (lib "eagle-import") (part "RESISTOR-NETWORK-1206"))
    )
    (comp (ref "RN4")
      (value "22Ω")
      (footprint "eagle-import:RESISTOR_NETWORK-1206")
      (libsource (lib "eagle-import") (part "RESISTOR-NETWORK-1206"))
    )
    (comp (ref "RN5")
      (value "22Ω")
      (footprint "eagle-import:RESISTOR_NETWORK-1206")
      (libsource (lib "eagle-import") (part "RESISTOR-NETWORK-1206"))
    )
    (comp (ref "RN6")
      (value "22Ω")
      (footprint "eagle-import:RESISTOR_NETWORK-1206")
      (libsource (lib "eagle-import") (part "RESISTOR-NETWORK-1206"))
    )
    (comp (ref "RN7")
      (value "22Ω")
      (footprint "eagle-import:RESISTOR_NETWORK-1206")
      (libsource (lib "eagle-import") (part "RESISTOR-NETWORK-1206"))
    )
    (comp (ref "RN8")
      (value "22Ω")
      (footprint "eagle-import:RESISTOR_NETWORK-1206")
      (libsource (lib "eagle-import") (part "RESISTOR-NETWORK-1206"))
    )
    (comp (ref "RN9")
      (value "22Ω")
      (footprint "eagle-import:RESISTOR_NETWORK-1206")
      (libsource (lib "eagle-import") (part "RESISTOR-NETWORK-1206"))
    )
    (comp (ref "RN10")
      (value "22Ω")
      (footprint "eagle-import:RESISTOR_NETWORK-1206")
      (libsource (lib "eagle-import") (part "RESISTOR-NETWORK-1206"))
    )
    (comp (ref "RN11")
      (value "22Ω")
      (footprint "eagle-import:RESISTOR_NETWORK-1206")
      (libsource (lib "eagle-import") (part "RESISTOR-NETWORK-1206"))
    )
    (comp (ref "RN12")
      (value "22Ω")
      (footprint "eagle-import:RESISTOR_NETWORK-1206")
      (libsource (lib "eagle-import") (part "RESISTOR-NETWORK-1206"))
    )
    (comp (ref "RN13")
      (value "22Ω")
      (footprint "eagle-import:RESISTOR_NETWORK-1206")
      (libsource (lib "eagle-import") (part "RESISTOR-NETWORK-1206"))
    )
    (comp (ref "RN14")
      (value "22Ω")
      (footprint "eagle-import:RESISTOR_NETWORK-1206")
      (libsource (lib "eagle-import") (part "RESISTOR-NETWORK-1206"))
    )
    (comp (ref "RN15")
      (value "22Ω")
      (footprint "eagle-import:RESISTOR_NETWORK-1206")
      (libsource (lib "eagle-import") (part "RESISTOR-NETWORK-1206"))
    )
    (comp (ref "S1")
      (value "FSMSM")
      (footprint "eagle-import:FSMSM")
      (libsource (lib "eagle-import") (part "FSMSM"))
    )
    (comp (ref "S2")
      (value "FSMSM")
      (footprint "eagle-import:FSMSM")
      (libsource (lib "eagle-import") (part "FSMSM"))
    )
    (comp (ref "S3")
      (value "FSMSM")
      (footprint "eagle-import:FSMSM")
      (libsource (lib "eagle-import") (part "FSMSM"))
    )
    (comp (ref "S4")
      (value "FSMSM")
      (footprint "eagle-import:FSMSM")
      (libsource (lib "eagle-import") (part "FSMSM"))
    )
    (comp (ref "S5")
      (value "FSMSM")
      (footprint "eagle-import:FSMSM")
      (libsource (lib "eagle-import") (part "FSMSM"))
    )
    (comp (ref "S6")
      (value "FSMSM")
      (footprint "eagle-import:FSMSM")
      (libsource (lib "eagle-import") (part "FSMSM"))
    )
    (comp (ref "S7")
      (value "FSMSM")
      (footprint "eagle-import:FSMSM")
      (libsource (lib "eagle-import") (part "FSMSM"))
    )
    (comp (ref "U$4")
      (value "DDR3")
      (footprint "eagle-import:DDR3_78")
      (libsource (lib "eagle-import") (part "DDR3"))
    )
    (comp (ref "U$5")
      (value "DDR3")
      (footprint "eagle-import:DDR3_78")
      (libsource (lib "eagle-import") (part "DDR3"))
    )
    (comp (ref "U1")
      (value "A13")
      (footprint "eagle-import:A13")
      (libsource (lib "eagle-import") (part "A13"))
    )
    (comp (ref "U2")
      (value "AXP209")
      (footprint "eagle-import:QFN-48")
      (libsource (lib "eagle-import") (part "AXP209"))
    )
    (comp (ref "U3")
      (value "AP2161DM8G-13")
      (footprint "eagle-import:MSOP-8")
      (libsource (lib "eagle-import") (part "AP2161DM8G-13"))
    )
    (comp (ref "U4")
      (value "HC-05")
      (footprint "eagle-import:HC-05")
      (libsource (lib "eagle-import") (part "HC-05"))
    )
    (comp (ref "U5")
      (value "MIC2250YML")
      (footprint "eagle-import:MLF-8")
      (libsource (lib "eagle-import") (part "MIC2250YML"))
    )
    (comp (ref "U6")
      (value "AP3409DNTR-G1")
      (footprint "eagle-import:UDFN-10")
      (libsource (lib "eagle-import") (part "AP3409DNTR-G1"))
    )
    (comp (ref "U7")
      (value "AP3409DNTR-G1")
      (footprint "eagle-import:UDFN-10")
      (libsource (lib "eagle-import") (part "AP3409DNTR-G1"))
    )
    (comp (ref "U8")
      (value "ST1S10PUR")
      (footprint "eagle-import:DFN-8")
      (libsource (lib "eagle-import") (part "ST1S10PUR"))
    )
    (comp (ref "U9")
      (value "TFP410")
      (footprint "eagle-import:PQFP-64")
      (libsource (lib "eagle-import") (part "TFP410"))
    )
    (comp (ref "U10")
      (value "ENC28J60-QFN")
      (footprint "eagle-import:QFN-28")
      (libsource (lib "eagle-import") (part "ENC28J60-QFN"))
    )
    (comp (ref "U11")
      (value "NAND")
      (footprint "eagle-import:TSOP1-48")
      (libsource (lib "eagle-import") (part "NAND"))
    )
    (comp (ref "U12")
      (value "TUSB2077")
      (footprint "eagle-import:LQFP-48")
      (libsource (lib "eagle-import") (part "TUSB2077"))
    )
    (comp (ref "U13")
      (value "HC-05-EZ")
      (footprint "eagle-import:M06X1")
      (libsource (lib "eagle-import") (part "HC-05-EZ"))
    )
    (comp (ref "U14")
      (value "TPS2042")
      (footprint "eagle-import:SON-8")
      (libsource (lib "eagle-import") (part "TPS2042"))
    )
    (comp (ref "U15")
      (value "TPS2042")
      (footprint "eagle-import:SON-8")
      (libsource (lib "eagle-import") (part "TPS2042"))
    )
    (comp (ref "U16")
      (value "TPS2042")
      (footprint "eagle-import:SON-8")
      (libsource (lib "eagle-import") (part "TPS2042"))
    )
    (comp (ref "U19")
      (value "IP4220CZ6")
      (footprint "eagle-import:SOT-6")
      (libsource (lib "eagle-import") (part "IP4220CZ6"))
    )
    (comp (ref "U20")
      (value "IP4220CZ6")
      (footprint "eagle-import:SOT-6")
      (libsource (lib "eagle-import") (part "IP4220CZ6"))
    )
    (comp (ref "U21")
      (value "IP4220CZ6")
      (footprint "eagle-import:SOT-6")
      (libsource (lib "eagle-import") (part "IP4220CZ6"))
    )
    (comp (ref "Y1")
      (value "24MHz")
      (footprint "eagle-import:FA-238")
      (libsource (lib "eagle-import") (part "CRYSTAL-3.2X2.5"))
    )
    (comp (ref "Y2")
      (value "25MHz")
      (footprint "eagle-import:FA-238")
      (libsource (lib "eagle-import") (part "CRYSTAL-3.2X2.5"))
    )
    (comp (ref "Y3")
      (value "6MHz")
      (footprint "eagle-import:FA-238")
      (libsource (lib "eagle-import") (part "CRYSTAL-3.2X2.5"))
    )
  )
  (nets
    (net (code "1") (name "/DDR3_A0") (class "Default")
      (node (ref "RN5") (pin "1") (pinfunction "1_1") (pintype "passive"))
      (node (ref "U$4") (pin "K3") (pinfunction "A0_K3") (pintype "bidirectional"))
      (node (ref "U$5") (pin "K3") (pinfunction "A0_K3") (pintype "bidirectional"))
    )
    (net (code "2") (name "/DDR3_A1") (class "Default")
      (node (ref "RN6") (pin "3") (pinfunction "1_3") (pintype "passive"))
      (node (ref "U$4") (pin "L7") (pinfunction "A1_L7") (pintype "bidirectional"))
      (node (ref "U$5") (pin "L7") (pinfunction "A1_L7") (pintype "bidirectional"))
    )
    (net (code "3") (name "/DDR3_A2") (class "Default")
      (node (ref "RN8") (pin "3") (pinfunction "1_3") (pintype "passive"))
      (node (ref "U$4") (pin "L3") (pinfunction "A2_L3") (pintype "bidirectional"))
      (node (ref "U$5") (pin "L3") (pinfunction "A2_L3") (pintype "bidirectional"))
    )
    (net (code "4") (name "/DDR3_A3") (class "Default")
      (node (ref "RN8") (pin "4") (pinfunction "1_4") (pintype "passive"))
      (node (ref "U$4") (pin "K2") (pinfunction "A3_K2") (pintype "bidirectional"))
      (node (ref "U$5") (pin "K2") (pinfunction "A3_K2") (pintype "bidirectional"))
    )
    (net (code "5") (name "/DDR3_A4") (class "Default")
      (node (ref "RN6") (pin "4") (pinfunction "1_4") (pintype "passive"))
      (node (ref "U$4") (pin "L8") (pinfunction "A4_L8") (pintype "bidirectional"))
      (node (ref "U$5") (pin "L8") (pinfunction "A4_L8") (pintype "bidirectional"))
    )
    (net (code "6") (name "/DDR3_A5") (class "Default")
      (node (ref "RN8") (pin "2") (pinfunction "1_2") (pintype "passive"))
      (node (ref "U$4") (pin "L2") (pinfunction "A5_L2") (pintype "bidirectional"))
      (node (ref "U$5") (pin "L2") (pinfunction "A5_L2") (pintype "bidirectional"))
    )
    (net (code "7") (name "/DDR3_A6") (class "Default")
      (node (ref "RN6") (pin "2") (pinfunction "1_2") (pintype "passive"))
      (node (ref "U$4") (pin "M8") (pinfunction "A6_M8") (pintype "bidirectional"))
      (node (ref "U$5") (pin "M8") (pinfunction "A6_M8") (pintype "bidirectional"))
    )
    (net (code "8") (name "/DDR3_A7") (class "Default")
      (node (ref "RN10") (pin "2") (pinfunction "1_2") (pintype "passive"))
      (node (ref "U$4") (pin "M2") (pinfunction "A7_M2") (pintype "bidirectional"))
      (node (ref "U$5") (pin "M2") (pinfunction "A7_M2") (pintype "bidirectional"))
    )
    (net (code "9") (name "/DDR3_A8") (class "Default")
      (node (ref "RN6") (pin "1") (pinfunction "1_1") (pintype "passive"))
      (node (ref "U$4") (pin "N8") (pinfunction "A8_N8") (pintype "bidirectional"))
      (node (ref "U$5") (pin "N8") (pinfunction "A8_N8") (pintype "bidirectional"))
    )
    (net (code "10") (name "/DDR3_A9") (class "Default")
      (node (ref "RN10") (pin "4") (pinfunction "1_4") (pintype "passive"))
      (node (ref "U$4") (pin "M3") (pinfunction "A9_M3") (pintype "bidirectional"))
      (node (ref "U$5") (pin "M3") (pinfunction "A9_M3") (pintype "bidirectional"))
    )
    (net (code "11") (name "/DDR3_A10") (class "Default")
      (node (ref "RN7") (pin "3") (pinfunction "1_3") (pintype "passive"))
      (node (ref "U$4") (pin "H7") (pinfunction "A10/AP_H7") (pintype "bidirectional"))
      (node (ref "U$5") (pin "H7") (pinfunction "A10/AP_H7") (pintype "bidirectional"))
    )
    (net (code "12") (name "/DDR3_A11") (class "Default")
      (node (ref "RN9") (pin "4") (pinfunction "1_4") (pintype "passive"))
      (node (ref "U$4") (pin "M7") (pinfunction "A11_M7") (pintype "bidirectional"))
      (node (ref "U$5") (pin "M7") (pinfunction "A11_M7") (pintype "bidirectional"))
    )
    (net (code "13") (name "/DDR3_A12") (class "Default")
      (node (ref "RN7") (pin "1") (pinfunction "1_1") (pintype "passive"))
      (node (ref "U$4") (pin "K7") (pinfunction "A12/~{BC}_K7") (pintype "bidirectional"))
      (node (ref "U$5") (pin "K7") (pinfunction "A12/~{BC}_K7") (pintype "bidirectional"))
    )
    (net (code "14") (name "/DDR3_A13") (class "Default")
      (node (ref "RN8") (pin "1") (pinfunction "1_1") (pintype "passive"))
      (node (ref "U$4") (pin "N3") (pinfunction "A13_N3") (pintype "bidirectional"))
      (node (ref "U$5") (pin "N3") (pinfunction "A13_N3") (pintype "bidirectional"))
    )
    (net (code "15") (name "/DDR3_A14") (class "Default")
      (node (ref "RN9") (pin "3") (pinfunction "1_3") (pintype "passive"))
      (node (ref "U$4") (pin "N7") (pinfunction "A14_N7") (pintype "bidirectional"))
      (node (ref "U$5") (pin "N7") (pinfunction "A14_N7") (pintype "bidirectional"))
    )
    (net (code "16") (name "/DDR3_BA0") (class "Default")
      (node (ref "RN5") (pin "2") (pinfunction "1_2") (pintype "passive"))
      (node (ref "U$4") (pin "J2") (pinfunction "BA0_J2") (pintype "bidirectional"))
      (node (ref "U$5") (pin "J2") (pinfunction "BA0_J2") (pintype "bidirectional"))
    )
    (net (code "17") (name "/DDR3_BA1") (class "Default")
      (node (ref "RN7") (pin "2") (pinfunction "1_2") (pintype "passive"))
      (node (ref "U$4") (pin "K8") (pinfunction "BA1_K8") (pintype "bidirectional"))
      (node (ref "U$5") (pin "K8") (pinfunction "BA1_K8") (pintype "bidirectional"))
    )
    (net (code "18") (name "/DDR3_BA2") (class "Default")
      (node (ref "RN5") (pin "3") (pinfunction "1_3") (pintype "passive"))
      (node (ref "U$4") (pin "J3") (pinfunction "BA2_J3") (pintype "bidirectional"))
      (node (ref "U$5") (pin "J3") (pinfunction "BA2_J3") (pintype "bidirectional"))
    )
    (net (code "19") (name "/DDR3_CKE") (class "Default")
      (node (ref "RN7") (pin "4") (pinfunction "1_4") (pintype "passive"))
      (node (ref "U$4") (pin "G9") (pinfunction "CKE_G9") (pintype "bidirectional"))
      (node (ref "U$5") (pin "G9") (pinfunction "CKE_G9") (pintype "bidirectional"))
    )
    (net (code "20") (name "/DDR3_CK_N") (class "Default")
      (node (ref "R47") (pin "1") (pinfunction "1_1") (pintype "passive"))
      (node (ref "U$4") (pin "G7") (pinfunction "~{CK}_G7") (pintype "bidirectional"))
      (node (ref "U$5") (pin "G7") (pinfunction "~{CK}_G7") (pintype "bidirectional"))
    )
    (net (code "21") (name "/DDR3_CK_P") (class "Default")
      (node (ref "R46") (pin "1") (pinfunction "1_1") (pintype "passive"))
      (node (ref "U$4") (pin "F7") (pinfunction "CK_F7") (pintype "bidirectional"))
      (node (ref "U$5") (pin "F7") (pinfunction "CK_F7") (pintype "bidirectional"))
    )
    (net (code "22") (name "/DDR3_D0") (class "Default")
      (node (ref "RN1") (pin "1") (pinfunction "1_1") (pintype "passive"))
      (node (ref "U$4") (pin "B3") (pinfunction "DQ0_B3") (pintype "bidirectional"))
    )
    (net (code "23") (name "/DDR3_D1") (class "Default")
      (node (ref "RN3") (pin "4") (pinfunction "1_4") (pintype "passive"))
      (node (ref "U$4") (pin "C7") (pinfunction "DQ1_C7") (pintype "bidirectional"))
    )
    (net (code "24") (name "/DDR3_D2") (class "Default")
      (node (ref "RN1") (pin "2") (pinfunction "1_2") (pintype "passive"))
      (node (ref "U$4") (pin "C2") (pinfunction "DQ2_C2") (pintype "bidirectional"))
    )
    (net (code "25") (name "/DDR3_D3") (class "Default")
      (node (ref "RN3") (pin "3") (pinfunction "1_3") (pintype "passive"))
      (node (ref "U$4") (pin "C8") (pinfunction "DQ3_C8") (pintype "bidirectional"))
    )
    (net (code "26") (name "/DDR3_D4") (class "Default")
      (node (ref "RN1") (pin "4") (pinfunction "1_4") (pintype "passive"))
      (node (ref "U$4") (pin "E3") (pinfunction "DQ4_E3") (pintype "bidirectional"))
    )
    (net (code "27") (name "/DDR3_D5") (class "Default")
      (node (ref "RN3") (pin "1") (pinfunction "1_1") (pintype "passive"))
      (node (ref "U$4") (pin "E8") (pinfunction "DQ5_E8") (pintype "bidirectional"))
    )
    (net (code "28") (name "/DDR3_D6") (class "Default")
      (node (ref "RN1") (pin "3") (pinfunction "1_3") (pintype "passive"))
      (node (ref "U$4") (pin "D2") (pinfunction "DQ6_D2") (pintype "bidirectional"))
    )
    (net (code "29") (name "/DDR3_D7") (class "Default")
      (node (ref "RN3") (pin "2") (pinfunction "1_2") (pintype "passive"))
      (node (ref "U$4") (pin "E7") (pinfunction "DQ7_E7") (pintype "bidirectional"))
    )
    (net (code "30") (name "/DDR3_D8") (class "Default")
      (node (ref "RN2") (pin "3") (pinfunction "1_3") (pintype "passive"))
      (node (ref "U$5") (pin "C8") (pinfunction "DQ3_C8") (pintype "bidirectional"))
    )
    (net (code "31") (name "/DDR3_D9") (class "Default")
      (node (ref "RN4") (pin "3") (pinfunction "1_3") (pintype "passive"))
      (node (ref "U$5") (pin "D2") (pinfunction "DQ6_D2") (pintype "bidirectional"))
    )
    (net (code "32") (name "/DDR3_D10") (class "Default")
      (node (ref "RN2") (pin "1") (pinfunction "1_1") (pintype "passive"))
      (node (ref "U$5") (pin "E8") (pinfunction "DQ5_E8") (pintype "bidirectional"))
    )
    (net (code "33") (name "/DDR3_D11") (class "Default")
      (node (ref "RN4") (pin "4") (pinfunction "1_4") (pintype "passive"))
      (node (ref "U$5") (pin "E3") (pinfunction "DQ4_E3") (pintype "bidirectional"))
    )
    (net (code "34") (name "/DDR3_D12") (class "Default")
      (node (ref "RN2") (pin "4") (pinfunction "1_4") (pintype "passive"))
      (node (ref "U$5") (pin "C7") (pinfunction "DQ1_C7") (pintype "bidirectional"))
    )
    (net (code "35") (name "/DDR3_D13") (class "Default")
      (node (ref "RN4") (pin "2") (pinfunction "1_2") (pintype "passive"))
      (node (ref "U$5") (pin "C2") (pinfunction "DQ2_C2") (pintype "bidirectional"))
    )
    (net (code "36") (name "/DDR3_D14") (class "Default")
      (node (ref "RN2") (pin "2") (pinfunction "1_2") (pintype "passive"))
      (node (ref "U$5") (pin "E7") (pinfunction "DQ7_E7") (pintype "bidirectional"))
    )
    (net (code "37") (name "/DDR3_D15") (class "Default")
      (node (ref "RN4") (pin "1") (pinfunction "1_1") (pintype "passive"))
      (node (ref "U$5") (pin "B3") (pinfunction "DQ0_B3") (pintype "bidirectional"))
    )
    (net (code "38") (name "/DDR3_DM0") (class "Default")
      (node (ref "R48") (pin "1") (pinfunction "1_1") (pintype "passive"))
      (node (ref "U$4") (pin "B7") (pinfunction "DM/TDQS_B7") (pintype "bidirectional"))
    )
    (net (code "39") (name "/DDR3_DM1") (class "Default")
      (node (ref "R49") (pin "1") (pinfunction "1_1") (pintype "passive"))
      (node (ref "U$5") (pin "B7") (pinfunction "DM/TDQS_B7") (pintype "bidirectional"))
    )
    (net (code "40") (name "/DDR3_DQS0_N") (class "Default")
      (node (ref "RN11") (pin "3") (pinfunction "1_3") (pintype "passive"))
      (node (ref "U$4") (pin "D3") (pinfunction "~{DQS}_D3") (pintype "bidirectional"))
    )
    (net (code "41") (name "/DDR3_DQS0_P") (class "Default")
      (node (ref "RN11") (pin "4") (pinfunction "1_4") (pintype "passive"))
      (node (ref "U$4") (pin "C3") (pinfunction "DQS_C3") (pintype "bidirectional"))
    )
    (net (code "42") (name "/DDR3_DQS1_N") (class "Default")
      (node (ref "RN11") (pin "1") (pinfunction "1_1") (pintype "passive"))
      (node (ref "U$5") (pin "D3") (pinfunction "~{DQS}_D3") (pintype "bidirectional"))
    )
    (net (code "43") (name "/DDR3_DQS1_P") (class "Default")
      (node (ref "RN11") (pin "2") (pinfunction "1_2") (pintype "passive"))
      (node (ref "U$5") (pin "C3") (pinfunction "DQS_C3") (pintype "bidirectional"))
    )
    (net (code "45") (name "/DDR3_ODT") (class "Default")
      (node (ref "RN10") (pin "1") (pinfunction "1_1") (pintype "passive"))
      (node (ref "U$4") (pin "G1") (pinfunction "ODT_G1") (pintype "bidirectional"))
      (node (ref "U$5") (pin "G1") (pinfunction "ODT_G1") (pintype "bidirectional"))
    )
    (net (code "46") (name "/DDR3_RST") (class "Default")
      (node (ref "RN10") (pin "3") (pinfunction "1_3") (pintype "passive"))
      (node (ref "U$4") (pin "N2") (pinfunction "~{RESET}_N2") (pintype "bidirectional"))
      (node (ref "U$5") (pin "N2") (pinfunction "~{RESET}_N2") (pintype "bidirectional"))
    )
    (net (code "47") (name "/~{DDR3_CAS}") (class "Default")
      (node (ref "RN9") (pin "1") (pinfunction "1_1") (pintype "passive"))
      (node (ref "U$4") (pin "G3") (pinfunction "~{CAS}_G3") (pintype "bidirectional"))
      (node (ref "U$5") (pin "G3") (pinfunction "~{CAS}_G3") (pintype "bidirectional"))
    )
    (net (code "48") (name "/~{DDR3_RAS}") (class "Default")
      (node (ref "RN9") (pin "2") (pinfunction "1_2") (pintype "passive"))
      (node (ref "U$4") (pin "F3") (pinfunction "~{RAS}_F3") (pintype "bidirectional"))
      (node (ref "U$5") (pin "F3") (pinfunction "~{RAS}_F3") (pintype "bidirectional"))
    )
    (net (code "49") (name "/~{DDR3_WE}") (class "Default")
      (node (ref "RN5") (pin "4") (pinfunction "1_4") (pintype "passive"))
      (node (ref "U$4") (pin "H3") (pinfunction "~{WE}_H3") (pintype "bidirectional"))
      (node (ref "U$5") (pin "H3") (pinfunction "~{WE}_H3") (pintype "bidirectional"))
    )
    (net (code "50") (name "/~{ETH_INT}") (class "Default")
      (node (ref "U1") (pin "104") (pinfunction "PB4/EINT18_104") (pintype "bidirectional"))
      (node (ref "U10") (pin "28") (pinfunction "~{INT}_28") (pintype "bidirectional"))
    )
    (net (code "51") (name "/~{NMI}") (class "Default")
      (node (ref "R1") (pin "1") (pinfunction "1_1") (pintype "passive"))
      (node (ref "U1") (pin "158") (pinfunction "~{NMI}_158") (pintype "bidirectional"))
      (node (ref "U2") (pin "48") (pinfunction "IRQ_48") (pintype "bidirectional"))
    )
    (net (code "52") (name "/~{RESET}") (class "Default")
      (node (ref "C2") (pin "1") (pinfunction "1_1") (pintype "passive"))
      (node (ref "C3") (pin "1") (pinfunction "1_1") (pintype "passive"))
      (node (ref "R8") (pin "1") (pinfunction "1_1") (pintype "passive"))
      (node (ref "U1") (pin "159") (pinfunction "~{RESET}_159") (pintype "bidirectional"))
      (node (ref "U12") (pin "6") (pinfunction "~{RESET}_6") (pintype "bidirectional"))
      (node (ref "U2") (pin "25") (pinfunction "PWROK_25") (pintype "bidirectional"))
    )
    (net (code "53") (name "/~{VBUSEN}") (class "Default")
      (node (ref "U1") (pin "15") (pinfunction "PG12/SPI1_MISO/UART3_RTS/EINT12_15") (pintype "bidirectional"))
      (node (ref "U2") (pin "6") (pinfunction "~{VBUSEN}_6") (pintype "bidirectional"))
      (node (ref "U3") (pin "4") (pinfunction "EN_4") (pintype "bidirectional"))
    )
    (net (code "54") (name "1.2V_CPU") (class "Default")
      (node (ref "C29") (pin "1") (pinfunction "1_1") (pintype "passive"))
      (node (ref "C39") (pin "1") (pinfunction "1_1") (pintype "passive"))
      (node (ref "C40") (pin "1") (pinfunction "1_1") (pintype "passive"))
      (node (ref "C41") (pin "1") (pinfunction "1_1") (pintype "passive"))
      (node (ref "C42") (pin "1") (pinfunction "1_1") (pintype "passive"))
      (node (ref "C43") (pin "1") (pinfunction "1_1") (pintype "passive"))
      (node (ref "C44") (pin "1") (pinfunction "1_1") (pintype "passive"))
      (node (ref "C45") (pin "1") (pinfunction "1_1") (pintype "passive"))
      (node (ref "C46") (pin "1") (pinfunction "1_1") (pintype "passive"))
      (node (ref "L2") (pin "2") (pinfunction "2_2") (pintype "passive"))
      (node (ref "U1") (pin "11") (pinfunction "VDD_CPU_11") (pintype "bidirectional"))
      (node (ref "U1") (pin "156") (pinfunction "VDD_CPU_156") (pintype "bidirectional"))
      (node (ref "U1") (pin "16") (pinfunction "VDD_CPU_16") (pintype "bidirectional"))
      (node (ref "U1") (pin "164") (pinfunction "VDD_CPU_164") (pintype "bidirectional"))
      (node (ref "U1") (pin "169") (pinfunction "VDD_CPU_169") (pintype "bidirectional"))
      (node (ref "U1") (pin "173") (pinfunction "VDD_CPU_173") (pintype "bidirectional"))
      (node (ref "U1") (pin "4") (pinfunction "VDD_CPU_4") (pintype "bidirectional"))
      (node (ref "U1") (pin "9") (pinfunction "VDD_CPU_9") (pintype "bidirectional"))
      (node (ref "U2") (pin "10") (pinfunction "DCDC2_10") (pintype "bidirectional"))
    )
    (net (code "55") (name "1.2V_INT") (class "Default")
      (node (ref "C30") (pin "1") (pinfunction "1_1") (pintype "passive"))
      (node (ref "C55") (pin "1") (pinfunction "1_1") (pintype "passive"))
      (node (ref "C56") (pin "1") (pinfunction "1_1") (pintype "passive"))
      (node (ref "C57") (pin "1") (pinfunction "1_1") (pintype "passive"))
      (node (ref "C58") (pin "1") (pinfunction "1_1") (pintype "passive"))
      (node (ref "C59") (pin "1") (pinfunction "1_1") (pintype "passive"))
      (node (ref "L3") (pin "2") (pinfunction "2_2") (pintype "passive"))
      (node (ref "U1") (pin "109") (pinfunction "VDD_INT_109") (pintype "bidirectional"))
      (node (ref "U1") (pin "149") (pinfunction "VDD_INT_149") (pintype "bidirectional"))
      (node (ref "U1") (pin "35") (pinfunction "VDD_INT_35") (pintype "bidirectional"))
      (node (ref "U1") (pin "73") (pinfunction "VDD_INT_73") (pintype "bidirectional"))
      (node (ref "U1") (pin "98") (pinfunction "VDD_INT_98") (pintype "bidirectional"))
      (node (ref "U2") (pin "17") (pinfunction "DCDC3_17") (pintype "bidirectional"))
    )
    (net (code "56") (name "1.5V_DDR") (class "Default")
      (node (ref "C60") (pin "1") (pinfunction "1_1") (pintype "passive"))
      (node (ref "C61") (pin "1") (pinfunction "1_1") (pintype "passive"))
      (node (ref "C62") (pin "1") (pinfunction "1_1") (pintype "passive"))
      (node (ref "C63") (pin "1") (pinfunction "1_1") (pintype "passive"))
      (node (ref "C64") (pin "1") (pinfunction "1_1") (pintype "passive"))
      (node (ref "C74") (pin "1") (pinfunction "1_1") (pintype "passive"))
      (node (ref "C75") (pin "1") (pinfunction "1_1") (pintype "passive"))
      (node (ref "C76") (pin "1") (pinfunction "1_1") (pintype "passive"))
      (node (ref "C83") (pin "1") (pinfunction "1_1") (pintype "passive"))
      (node (ref "C86") (pin "1") (pinfunction "1_1") (pintype "passive"))
      (node (ref "C89") (pin "1") (pinfunction "1_1") (pintype "passive"))
      (node (ref "C90") (pin "1") (pinfunction "1_1") (pintype "passive"))
      (node (ref "C91") (pin "1") (pinfunction "1_1") (pintype "passive"))
      (node (ref "C92") (pin "1") (pinfunction "1_1") (pintype "passive"))
      (node (ref "C93") (pin "1") (pinfunction "1_1") (pintype "passive"))
      (node (ref "C94") (pin "1") (pinfunction "1_1") (pintype "passive"))
      (node (ref "C95") (pin "1") (pinfunction "1_1") (pintype "passive"))
      (node (ref "C96") (pin "1") (pinfunction "1_1") (pintype "passive"))
      (node (ref "C97") (pin "1") (pinfunction "1_1") (pintype "passive"))
      (node (ref "C98") (pin "1") (pinfunction "1_1") (pintype "passive"))
      (node (ref "C99") (pin "1") (pinfunction "1_1") (pintype "passive"))
      (node (ref "L6") (pin "2") (pinfunction "2_2") (pintype "passive"))
      (node (ref "R35") (pin "2") (pinfunction "2_2") (pintype "passive"))
      (node (ref "R45") (pin "2") (pinfunction "2_2") (pintype "passive"))
      (node (ref "U$4") (pin "A2") (pinfunction "VDD_A2") (pintype "bidirectional"))
      (node (ref "U$4") (pin "A9") (pinfunction "VDD_A9") (pintype "bidirectional"))
      (node (ref "U$4") (pin "B9") (pinfunction "VDDQ_B9") (pintype "bidirectional"))
      (node (ref "U$4") (pin "C1") (pinfunction "VDDQ_C1") (pintype "bidirectional"))
      (node (ref "U$4") (pin "D7") (pinfunction "VDD_D7") (pintype "bidirectional"))
      (node (ref "U$4") (pin "E2") (pinfunction "VDDQ_E2") (pintype "bidirectional"))
      (node (ref "U$4") (pin "E9") (pinfunction "VDDQ_E9") (pintype "bidirectional"))
      (node (ref "U$4") (pin "G2") (pinfunction "VDD_G2") (pintype "bidirectional"))
      (node (ref "U$4") (pin "G8") (pinfunction "VDD_G8") (pintype "bidirectional"))
      (node (ref "U$4") (pin "K1") (pinfunction "VDD_K1") (pintype "bidirectional"))
      (node (ref "U$4") (pin "K9") (pinfunction "VDD_K9") (pintype "bidirectional"))
      (node (ref "U$4") (pin "M1") (pinfunction "VDD_M1") (pintype "bidirectional"))
      (node (ref "U$4") (pin "M9") (pinfunction "VDD_M9") (pintype "bidirectional"))
      (node (ref "U$5") (pin "A2") (pinfunction "VDD_A2") (pintype "bidirectional"))
      (node (ref "U$5") (pin "A9") (pinfunction "VDD_A9") (pintype "bidirectional"))
      (node (ref "U$5") (pin "B9") (pinfunction "VDDQ_B9") (pintype "bidirectional"))
      (node (ref "U$5") (pin "C1") (pinfunction "VDDQ_C1") (pintype "bidirectional"))
      (node (ref "U$5") (pin "D7") (pinfunction "VDD_D7") (pintype "bidirectional"))
      (node (ref "U$5") (pin "E2") (pinfunction "VDDQ_E2") (pintype "bidirectional"))
      (node (ref "U$5") (pin "E9") (pinfunction "VDDQ_E9") (pintype "bidirectional"))
      (node (ref "U$5") (pin "G2") (pinfunction "VDD_G2") (pintype "bidirectional"))
      (node (ref "U$5") (pin "G8") (pinfunction "VDD_G8") (pintype "bidirectional"))
      (node (ref "U$5") (pin "K1") (pinfunction "VDD_K1") (pintype "bidirectional"))
      (node (ref "U$5") (pin "K9") (pinfunction "VDD_K9") (pintype "bidirectional"))
      (node (ref "U$5") (pin "M1") (pinfunction "VDD_M1") (pintype "bidirectional"))
      (node (ref "U$5") (pin "M9") (pinfunction "VDD_M9") (pintype "bidirectional"))
      (node (ref "U1") (pin "23") (pinfunction "VCC_DRAM_23") (pintype "bidirectional"))
      (node (ref "U1") (pin "30") (pinfunction "VCC_DRAM_30") (pintype "bidirectional"))
      (node (ref "U1") (pin "43") (pinfunction "VCC_DRAM_43") (pintype "bidirectional"))
      (node (ref "U1") (pin "53") (pinfunction "VCC_DRAM_53") (pintype "bidirectional"))
      (node (ref "U1") (pin "62") (pinfunction "VCC_DRAM_62") (pintype "bidirectional"))
    )
    (net (code "57") (name "3.0V") (class "Default")
      (node (ref "C31") (pin "1") (pinfunction "1_1") (pintype "passive"))
      (node (ref "C50") (pin "1") (pinfunction "1_1") (pintype "passive"))
      (node (ref "R7") (pin "2") (pinfunction "2_2") (pintype "passive"))
      (node (ref "U1") (pin "81") (pinfunction "AVCC_81") (pintype "bidirectional"))
      (node (ref "U2") (pin "12") (pinfunction "LDO2_12") (pintype "bidirectional"))
    )
    (net (code "58") (name "3.3V") (class "Default")
      (node (ref "C100") (pin "1") (pinfunction "1_1") (pintype "passive"))
      (node (ref "C101") (pin "1") (pinfunction "1_1") (pintype "passive"))
      (node (ref "C102") (pin "1") (pinfunction "1_1") (pintype "passive"))
      (node (ref "C103") (pin "1") (pinfunction "1_1") (pintype "passive"))
      (node (ref "C104") (pin "1") (pinfunction "1_1") (pintype "passive"))
      (node (ref "C105") (pin "1") (pinfunction "1_1") (pintype "passive"))
      (node (ref "C106") (pin "1") (pinfunction "1_1") (pintype "passive"))
      (node (ref "C113") (pin "1") (pinfunction "1_1") (pintype "passive"))
      (node (ref "C114") (pin "1") (pinfunction "1_1") (pintype "passive"))
      (node (ref "C115") (pin "1") (pinfunction "1_1") (pintype "passive"))
      (node (ref "C116") (pin "1") (pinfunction "1_1") (pintype "passive"))
      (node (ref "C117") (pin "1") (pinfunction "1_1") (pintype "passive"))
      (node (ref "C118") (pin "1") (pinfunction "1_1") (pintype "passive"))
      (node (ref "C119") (pin "1") (pinfunction "1_1") (pintype "passive"))
      (node (ref "C35") (pin "1") (pinfunction "1_1") (pintype "passive"))
      (node (ref "C36") (pin "1") (pinfunction "1_1") (pintype "passive"))
      (node (ref "C37") (pin "1") (pinfunction "1_1") (pintype "passive"))
      (node (ref "C38") (pin "1") (pinfunction "1_1") (pintype "passive"))
      (node (ref "C51") (pin "1") (pinfunction "1_1") (pintype "passive"))
      (node (ref "C52") (pin "1") (pinfunction "1_1") (pintype "passive"))
      (node (ref "C71") (pin "1") (pinfunction "1_1") (pintype "passive"))
      (node (ref "C72") (pin "1") (pinfunction "1_1") (pintype "passive"))
      (node (ref "C73") (pin "1") (pinfunction "1_1") (pintype "passive"))
      (node (ref "D1") (pin "ANODE") (pinfunction "ANODE_ANODE") (pintype "bidirectional"))
      (node (ref "L4") (pin "1") (pinfunction "1_1") (pintype "passive"))
      (node (ref "L7") (pin "2") (pinfunction "2_2") (pintype "passive"))
      (node (ref "L9") (pin "2") (pinfunction "2_2") (pintype "passive"))
      (node (ref "R10") (pin "2") (pinfunction "2_2") (pintype "passive"))
      (node (ref "R13") (pin "2") (pinfunction "2_2") (pintype "passive"))
      (node (ref "R14") (pin "2") (pinfunction "2_2") (pintype "passive"))
      (node (ref "R24") (pin "2") (pinfunction "2_2") (pintype "passive"))
      (node (ref "R25") (pin "2") (pinfunction "2_2") (pintype "passive"))
      (node (ref "R26") (pin "2") (pinfunction "2_2") (pintype "passive"))
      (node (ref "R27") (pin "2") (pinfunction "2_2") (pintype "passive"))
      (node (ref "R28") (pin "2") (pinfunction "2_2") (pintype "passive"))
      (node (ref "R29") (pin "2") (pinfunction "2_2") (pintype "passive"))
      (node (ref "R39") (pin "2") (pinfunction "2_2") (pintype "passive"))
      (node (ref "R51") (pin "2") (pinfunction "2_2") (pintype "passive"))
      (node (ref "R53") (pin "2") (pinfunction "2_2") (pintype "passive"))
      (node (ref "R60") (pin "2") (pinfunction "2_2") (pintype "passive"))
      (node (ref "R61") (pin "2") (pinfunction "2_2") (pintype "passive"))
      (node (ref "R62") (pin "2") (pinfunction "2_2") (pintype "passive"))
      (node (ref "R8") (pin "2") (pinfunction "2_2") (pintype "passive"))
      (node (ref "R9") (pin "2") (pinfunction "2_2") (pintype "passive"))
      (node (ref "U1") (pin "100") (pinfunction "VCC_100") (pintype "bidirectional"))
      (node (ref "U1") (pin "142") (pinfunction "VCC_142") (pintype "bidirectional"))
      (node (ref "U1") (pin "163") (pinfunction "VCC_163") (pintype "bidirectional"))
      (node (ref "U1") (pin "5") (pinfunction "VCC_5") (pintype "bidirectional"))
      (node (ref "U1") (pin "76") (pinfunction "V33_HP_76") (pintype "bidirectional"))
      (node (ref "U1") (pin "97") (pinfunction "V33_USB_97") (pintype "bidirectional"))
      (node (ref "U10") (pin "11") (pinfunction "VDDTX_11") (pintype "bidirectional"))
      (node (ref "U10") (pin "15") (pinfunction "VDDRX_15") (pintype "bidirectional"))
      (node (ref "U10") (pin "16") (pinfunction "VDDPLL_16") (pintype "bidirectional"))
      (node (ref "U10") (pin "21") (pinfunction "VDDOSC_21") (pintype "bidirectional"))
      (node (ref "U10") (pin "24") (pinfunction "VDD_24") (pintype "bidirectional"))
      (node (ref "U11") (pin "12") (pinfunction "VCC_12") (pintype "bidirectional"))
      (node (ref "U11") (pin "37") (pinfunction "VCC_37") (pintype "bidirectional"))
      (node (ref "U12") (pin "10") (pinfunction "~{BUSPWR}_10") (pintype "bidirectional"))
      (node (ref "U12") (pin "46") (pinfunction "VCC_46") (pintype "bidirectional"))
      (node (ref "U12") (pin "47") (pinfunction "~{EXTMEM}_47") (pintype "bidirectional"))
      (node (ref "U12") (pin "8") (pinfunction "EEDATA_8") (pintype "bidirectional"))
      (node (ref "U12") (pin "9") (pinfunction "VCC_9") (pintype "bidirectional"))
      (node (ref "U13") (pin "6") (pinfunction "VCC_6") (pintype "bidirectional"))
      (node (ref "U4") (pin "12") (pinfunction "3V3_12") (pintype "bidirectional"))
      (node (ref "U9") (pin "1") (pinfunction "DVDD_1") (pintype "bidirectional"))
      (node (ref "U9") (pin "12") (pinfunction "DVDD_12") (pintype "bidirectional"))
      (node (ref "U9") (pin "18") (pinfunction "PVDD_18") (pintype "bidirectional"))
      (node (ref "U9") (pin "23") (pinfunction "TVDD_23") (pintype "bidirectional"))
      (node (ref "U9") (pin "29") (pinfunction "TVDD_29") (pintype "bidirectional"))
      (node (ref "U9") (pin "3") (pinfunction "VREF_3") (pintype "bidirectional"))
      (node (ref "U9") (pin "33") (pinfunction "DVDD_33") (pintype "bidirectional"))
    )
    (net (code "59") (name "3.3V-WIFI") (class "Default")
      (node (ref "C32") (pin "1") (pinfunction "1_1") (pintype "passive"))
      (node (ref "U2") (pin "41") (pinfunction "LDO3_41") (pintype "bidirectional"))
    )
    (net (code "60") (name "5V") (class "Default")
      (node (ref "C10") (pin "1") (pinfunction "1_1") (pintype "passive"))
      (node (ref "C11") (pin "1") (pinfunction "1_1") (pintype "passive"))
      (node (ref "C126") (pin "1") (pinfunction "1_1") (pintype "passive"))
      (node (ref "C127") (pin "1") (pinfunction "1_1") (pintype "passive"))
      (node (ref "C128") (pin "1") (pinfunction "1_1") (pintype "passive"))
      (node (ref "D3") (pin "C") (pinfunction "C_C") (pintype "bidirectional"))
      (node (ref "J5") (pin "18") (pinfunction "5V_18") (pintype "bidirectional"))
      (node (ref "Q1") (pin "2") (pinfunction "S_2") (pintype "bidirectional"))
      (node (ref "R15") (pin "2") (pinfunction "2_2") (pintype "passive"))
      (node (ref "U14") (pin "2") (pinfunction "VCC_2") (pintype "bidirectional"))
      (node (ref "U15") (pin "2") (pinfunction "VCC_2") (pintype "bidirectional"))
      (node (ref "U16") (pin "2") (pinfunction "VCC_2") (pintype "bidirectional"))
      (node (ref "U19") (pin "5") (pinfunction "VCC_5") (pintype "bidirectional"))
      (node (ref "U20") (pin "5") (pinfunction "VCC_5") (pintype "bidirectional"))
      (node (ref "U21") (pin "5") (pinfunction "VCC_5") (pintype "bidirectional"))
      (node (ref "U3") (pin "2") (pinfunction "IN_2") (pintype "bidirectional"))
      (node (ref "U3") (pin "3") (pinfunction "IN_3") (pintype "bidirectional"))
    )
    (net (code "61") (name "5V_RAW") (class "Default")
      (node (ref "U2") (pin "32") (pinfunction "ACIN_32") (pintype "bidirectional"))
      (node (ref "U2") (pin "33") (pinfunction "ACIN_33") (pintype "bidirectional"))
    )
    (net (code "62") (name "BAT") (class "Default")
      (node (ref "C22") (pin "1") (pinfunction "1_1") (pintype "passive"))
      (node (ref "C24") (pin "2") (pinfunction "2_2") (pintype "passive"))
      (node (ref "J2") (pin "2") (pinfunction "+_2") (pintype "bidirectional"))
      (node (ref "JP1") (pin "2") (pinfunction "2_2") (pintype "passive"))
      (node (ref "R19") (pin "2") (pinfunction "2_2") (pintype "passive"))
      (node (ref "U2") (pin "38") (pinfunction "BAT_38") (pintype "bidirectional"))
      (node (ref "U2") (pin "39") (pinfunction "BAT_39") (pintype "bidirectional"))
      (node (ref "U2") (pin "42") (pinfunction "BATSENSE_42") (pintype "bidirectional"))
    )
    (net (code "63") (name "BT_KEY") (class "Default")
      (node (ref "U1") (pin "105") (pinfunction "PB15_105") (pintype "bidirectional"))
      (node (ref "U13") (pin "2") (pinfunction "KEY_2") (pintype "bidirectional"))
      (node (ref "U4") (pin "34") (pinfunction "PIO11_34") (pintype "bidirectional"))
    )
    (net (code "64") (name "BT_LED") (class "Default")
      (node (ref "U1") (pin "106") (pinfunction "PB16_106") (pintype "bidirectional"))
      (node (ref "U13") (pin "1") (pinfunction "LED_1") (pintype "bidirectional"))
    )
    (net (code "65") (name "CEC") (class "Default")
      (node (ref "J5") (pin "13") (pinfunction "CEC_13") (pintype "bidirectional"))
      (node (ref "U1") (pin "150") (pinfunction "PB3/EINT17_150") (pintype "bidirectional"))
    )
    (net (code "66") (name "DDR_VREF") (class "Default")
      (node (ref "C84") (pin "1") (pinfunction "1_1") (pintype "passive"))
      (node (ref "C85") (pin "1") (pinfunction "1_1") (pintype "passive"))
      (node (ref "C87") (pin "1") (pinfunction "1_1") (pintype "passive"))
      (node (ref "C88") (pin "1") (pinfunction "1_1") (pintype "passive"))
      (node (ref "R44") (pin "2") (pinfunction "2_2") (pintype "passive"))
      (node (ref "R45") (pin "1") (pinfunction "1_1") (pintype "passive"))
      (node (ref "U$4") (pin "E1") (pinfunction "VREFDQ_E1") (pintype "bidirectional"))
      (node (ref "U$4") (pin "J8") (pinfunction "VREFCA_J8") (pintype "bidirectional"))
      (node (ref "U$5") (pin "E1") (pinfunction "VREFDQ_E1") (pintype "bidirectional"))
      (node (ref "U$5") (pin "J8") (pinfunction "VREFCA_J8") (pintype "bidirectional"))
    )
    (net (code "67") (name "ETH_CLK") (class "Default")
      (node (ref "U1") (pin "115") (pinfunction "CSI_MCLK/SPI2_CLK/EINT15_115") (pintype "bidirectional"))
      (node (ref "U10") (pin "4") (pinfunction "SCK_4") (pintype "bidirectional"))
    )
    (net (code "68") (name "ETH_CS") (class "Default")
      (node (ref "U1") (pin "114") (pinfunction "CSI_PCLK/SPI2_CS0/EINT14_114") (pintype "bidirectional"))
      (node (ref "U10") (pin "5") (pinfunction "~{CS}_5") (pintype "bidirectional"))
    )
    (net (code "69") (name "ETH_MISO") (class "Default")
      (node (ref "U1") (pin "117") (pinfunction "CSI_VSYNC/SPI2_MISO_117") (pintype "bidirectional"))
      (node (ref "U10") (pin "2") (pinfunction "SO_2") (pintype "bidirectional"))
    )
    (net (code "70") (name "ETH_MOSI") (class "Default")
      (node (ref "U1") (pin "116") (pinfunction "CSI_HSYNC/SPI2_MOSI_116") (pintype "bidirectional"))
      (node (ref "U10") (pin "3") (pinfunction "SI_3") (pintype "bidirectional"))
    )
    (net (code "71") (name "EXTEN") (class "Default")
      (node (ref "U2") (pin "20") (pinfunction "EXTEN_20") (pintype "bidirectional"))
    )
    (net (code "72") (name "FGND") (class "Default")
      (node (ref "J5") (pin "P$1") (pinfunction "SHIELD_P$1") (pintype "bidirectional"))
      (node (ref "J5") (pin "P$2") (pinfunction "SHIELD_P$2") (pintype "bidirectional"))
      (node (ref "J5") (pin "P$3") (pinfunction "SHIELD_P$3") (pintype "bidirectional"))
      (node (ref "J5") (pin "P$4") (pinfunction "SHIELD_P$4") (pintype "bidirectional"))
      (node (ref "J6") (pin "P$5") (pinfunction "S$1_P$5") (pintype "bidirectional"))
      (node (ref "J6") (pin "P$6") (pinfunction "S$2_P$6") (pintype "bidirectional"))
      (node (ref "J7") (pin "MT1") (pinfunction "S1_MT1") (pintype "bidirectional"))
      (node (ref "J7") (pin "MT2") (pinfunction "S2_MT2") (pintype "bidirectional"))
      (node (ref "J7") (pin "P$1") (pinfunction "S1_P$1") (pintype "bidirectional"))
      (node (ref "J7") (pin "P$2") (pinfunction "S2_P$2") (pintype "bidirectional"))
      (node (ref "J8") (pin "P$1") (pinfunction "P$1_P$1") (pintype "bidirectional"))
      (node (ref "J8") (pin "P$2") (pinfunction "P$1_P$2") (pintype "bidirectional"))
      (node (ref "J8") (pin "P$3") (pinfunction "P$2_P$3") (pintype "bidirectional"))
      (node (ref "J8") (pin "P$4") (pinfunction "P$2_P$4") (pintype "bidirectional"))
      (node (ref "J9") (pin "P$1") (pinfunction "P$1_P$1") (pintype "bidirectional"))
      (node (ref "J9") (pin "P$2") (pinfunction "P$1_P$2") (pintype "bidirectional"))
      (node (ref "J9") (pin "P$3") (pinfunction "P$2_P$3") (pintype "bidirectional"))
      (node (ref "J9") (pin "P$4") (pinfunction "P$2_P$4") (pintype "bidirectional"))
      (node (ref "PT1") (pin "P$2") (pinfunction "P$2_P$2") (pintype "bidirectional"))
      (node (ref "PT2") (pin "P$2") (pinfunction "P$2_P$2") (pintype "bidirectional"))
      (node (ref "PT3") (pin "P$2") (pinfunction "P$2_P$2") (pintype "bidirectional"))
      (node (ref "PT4") (pin "P$2") (pinfunction "P$2_P$2") (pintype "bidirectional"))
      (node (ref "PT5") (pin "P$2") (pinfunction "P$2_P$2") (pintype "bidirectional"))
      (node (ref "PT6") (pin "P$2") (pinfunction "P$2_P$2") (pintype "bidirectional"))
      (node (ref "PT7") (pin "P$2") (pinfunction "P$2_P$2") (pintype "bidirectional"))
      (node (ref "PT8") (pin "P$2") (pinfunction "P$2_P$2") (pintype "bidirectional"))
      (node (ref "PT9") (pin "P$2") (pinfunction "P$2_P$2") (pintype "bidirectional"))
      (node (ref "U5") (pin "3") (pinfunction "PGND_3") (pintype "bidirectional"))
      (node (ref "U5") (pin "EP") (pinfunction "PGND_EP") (pintype "bidirectional"))
      (node (ref "U6") (pin "5") (pinfunction "PGND_5") (pintype "bidirectional"))
      (node (ref "U6") (pin "EP") (pinfunction "PGND_EP") (pintype "bidirectional"))
      (node (ref "U7") (pin "5") (pinfunction "PGND_5") (pintype "bidirectional"))
      (node (ref "U7") (pin "EP") (pinfunction "PGND_EP") (pintype "bidirectional"))
      (node (ref "U8") (pin "8") (pinfunction "PGND_8") (pintype "bidirectional"))
      (node (ref "U8") (pin "EP") (pinfunction "PGND_EP") (pintype "bidirectional"))
    )
    (net (code "73") (name "GND") (class "Default")
      (node (ref "C1") (pin "2") (pinfunction "2_2") (pintype "passive"))
      (node (ref "C10") (pin "2") (pinfunction "2_2") (pintype "passive"))
      (node (ref "C100") (pin "2") (pinfunction "2_2") (pintype "passive"))
      (node (ref "C101") (pin "2") (pinfunction "2_2") (pintype "passive"))
      (node (ref "C102") (pin "2") (pinfunction "2_2") (pintype "passive"))
      (node (ref "C103") (pin "2") (pinfunction "2_2") (pintype "passive"))
      (node (ref "C104") (pin "2") (pinfunction "2_2") (pintype "passive"))
      (node (ref "C105") (pin "2") (pinfunction "2_2") (pintype "passive"))
      (node (ref "C106") (pin "2") (pinfunction "2_2") (pintype "passive"))
      (node (ref "C107") (pin "-") (pinfunction "-_-") (pintype "passive"))
      (node (ref "C108") (pin "2") (pinfunction "2_2") (pintype "passive"))
      (node (ref "C109") (pin "2") (pinfunction "2_2") (pintype "passive"))
      (node (ref "C11") (pin "2") (pinfunction "2_2") (pintype "passive"))
      (node (ref "C110") (pin "2") (pinfunction "2_2") (pintype "passive"))
      (node (ref "C111") (pin "2") (pinfunction "2_2") (pintype "passive"))
      (node (ref "C112") (pin "2") (pinfunction "2_2") (pintype "passive"))
      (node (ref "C113") (pin "2") (pinfunction "2_2") (pintype "passive"))
      (node (ref "C114") (pin "2") (pinfunction "2_2") (pintype "passive"))
      (node (ref "C115") (pin "2") (pinfunction "2_2") (pintype "passive"))
      (node (ref "C116") (pin "2") (pinfunction "2_2") (pintype "passive"))
      (node (ref "C117") (pin "2") (pinfunction "2_2") (pintype "passive"))
      (node (ref "C118") (pin "2") (pinfunction "2_2") (pintype "passive"))
      (node (ref "C119") (pin "2") (pinfunction "2_2") (pintype "passive"))
      (node (ref "C12") (pin "-") (pinfunction "-_-") (pintype "passive"))
      (node (ref "C120") (pin "-") (pinfunction "-_-") (pintype "passive"))
      (node (ref "C121") (pin "-") (pinfunction "-_-") (pintype "passive"))
      (node (ref "C122") (pin "-") (pinfunction "-_-") (pintype "passive"))
      (node (ref "C123") (pin "-") (pinfunction "-_-") (pintype "passive"))
      (node (ref "C124") (pin "-") (pinfunction "-_-") (pintype "passive"))
      (node (ref "C125") (pin "-") (pinfunction "-_-") (pintype "passive"))
      (node (ref "C126") (pin "2") (pinfunction "2_2") (pintype "passive"))
      (node (ref "C127") (pin "2") (pinfunction "2_2") (pintype "passive"))
      (node (ref "C128") (pin "2") (pinfunction "2_2") (pintype "passive"))
      (node (ref "C129") (pin "2") (pinfunction "2_2") (pintype "passive"))
      (node (ref "C13") (pin "2") (pinfunction "2_2") (pintype "passive"))
      (node (ref "C130") (pin "2") (pinfunction "2_2") (pintype "passive"))
      (node (ref "C14") (pin "2") (pinfunction "2_2") (pintype "passive"))
      (node (ref "C15") (pin "2") (pinfunction "2_2") (pintype "passive"))
      (node (ref "C16") (pin "2") (pinfunction "2_2") (pintype "passive"))
      (node (ref "C17") (pin "2") (pinfunction "2_2") (pintype "passive"))
      (node (ref "C18") (pin "2") (pinfunction "2_2") (pintype "passive"))
      (node (ref "C19") (pin "2") (pinfunction "2_2") (pintype "passive"))
      (node (ref "C2") (pin "2") (pinfunction "2_2") (pintype "passive"))
      (node (ref "C20") (pin "2") (pinfunction "2_2") (pintype "passive"))
      (node (ref "C21") (pin "2") (pinfunction "2_2") (pintype "passive"))
      (node (ref "C22") (pin "2") (pinfunction "2_2") (pintype "passive"))
      (node (ref "C23") (pin "2") (pinfunction "2_2") (pintype "passive"))
      (node (ref "C25") (pin "2") (pinfunction "2_2") (pintype "passive"))
      (node (ref "C26") (pin "2") (pinfunction "2_2") (pintype "passive"))
      (node (ref "C27") (pin "2") (pinfunction "2_2") (pintype "passive"))
      (node (ref "C28") (pin "2") (pinfunction "2_2") (pintype "passive"))
      (node (ref "C29") (pin "2") (pinfunction "2_2") (pintype "passive"))
      (node (ref "C3") (pin "2") (pinfunction "2_2") (pintype "passive"))
      (node (ref "C30") (pin "2") (pinfunction "2_2") (pintype "passive"))
      (node (ref "C31") (pin "2") (pinfunction "2_2") (pintype "passive"))
      (node (ref "C32") (pin "2") (pinfunction "2_2") (pintype "passive"))
      (node (ref "C33") (pin "2") (pinfunction "2_2") (pintype "passive"))
      (node (ref "C34") (pin "2") (pinfunction "2_2") (pintype "passive"))
      (node (ref "C35") (pin "2") (pinfunction "2_2") (pintype "passive"))
      (node (ref "C36") (pin "2") (pinfunction "2_2") (pintype "passive"))
      (node (ref "C37") (pin "2") (pinfunction "2_2") (pintype "passive"))
      (node (ref "C38") (pin "2") (pinfunction "2_2") (pintype "passive"))
      (node (ref "C39") (pin "2") (pinfunction "2_2") (pintype "passive"))
      (node (ref "C4") (pin "2") (pinfunction "2_2") (pintype "passive"))
      (node (ref "C40") (pin "2") (pinfunction "2_2") (pintype "passive"))
      (node (ref "C41") (pin "2") (pinfunction "2_2") (pintype "passive"))
      (node (ref "C42") (pin "2") (pinfunction "2_2") (pintype "passive"))
      (node (ref "C43") (pin "2") (pinfunction "2_2") (pintype "passive"))
      (node (ref "C44") (pin "2") (pinfunction "2_2") (pintype "passive"))
      (node (ref "C45") (pin "2") (pinfunction "2_2") (pintype "passive"))
      (node (ref "C46") (pin "2") (pinfunction "2_2") (pintype "passive"))
      (node (ref "C47") (pin "2") (pinfunction "2_2") (pintype "passive"))
      (node (ref "C48") (pin "2") (pinfunction "2_2") (pintype "passive"))
      (node (ref "C49") (pin "2") (pinfunction "2_2") (pintype "passive"))
      (node (ref "C5") (pin "2") (pinfunction "2_2") (pintype "passive"))
      (node (ref "C50") (pin "2") (pinfunction "2_2") (pintype "passive"))
      (node (ref "C51") (pin "2") (pinfunction "2_2") (pintype "passive"))
      (node (ref "C52") (pin "2") (pinfunction "2_2") (pintype "passive"))
      (node (ref "C53") (pin "2") (pinfunction "2_2") (pintype "passive"))
      (node (ref "C54") (pin "2") (pinfunction "2_2") (pintype "passive"))
      (node (ref "C55") (pin "2") (pinfunction "2_2") (pintype "passive"))
      (node (ref "C56") (pin "2") (pinfunction "2_2") (pintype "passive"))
      (node (ref "C57") (pin "2") (pinfunction "2_2") (pintype "passive"))
      (node (ref "C58") (pin "2") (pinfunction "2_2") (pintype "passive"))
      (node (ref "C59") (pin "2") (pinfunction "2_2") (pintype "passive"))
      (node (ref "C6") (pin "2") (pinfunction "2_2") (pintype "passive"))
      (node (ref "C60") (pin "2") (pinfunction "2_2") (pintype "passive"))
      (node (ref "C61") (pin "2") (pinfunction "2_2") (pintype "passive"))
      (node (ref "C62") (pin "2") (pinfunction "2_2") (pintype "passive"))
      (node (ref "C63") (pin "2") (pinfunction "2_2") (pintype "passive"))
      (node (ref "C64") (pin "2") (pinfunction "2_2") (pintype "passive"))
      (node (ref "C65") (pin "2") (pinfunction "2_2") (pintype "passive"))
      (node (ref "C66") (pin "2") (pinfunction "2_2") (pintype "passive"))
      (node (ref "C67") (pin "2") (pinfunction "2_2") (pintype "passive"))
      (node (ref "C68") (pin "2") (pinfunction "2_2") (pintype "passive"))
      (node (ref "C69") (pin "2") (pinfunction "2_2") (pintype "passive"))
      (node (ref "C7") (pin "2") (pinfunction "2_2") (pintype "passive"))
      (node (ref "C70") (pin "2") (pinfunction "2_2") (pintype "passive"))
      (node (ref "C71") (pin "2") (pinfunction "2_2") (pintype "passive"))
      (node (ref "C72") (pin "2") (pinfunction "2_2") (pintype "passive"))
      (node (ref "C73") (pin "2") (pinfunction "2_2") (pintype "passive"))
      (node (ref "C74") (pin "2") (pinfunction "2_2") (pintype "passive"))
      (node (ref "C75") (pin "2") (pinfunction "2_2") (pintype "passive"))
      (node (ref "C76") (pin "2") (pinfunction "2_2") (pintype "passive"))
      (node (ref "C77") (pin "2") (pinfunction "2_2") (pintype "passive"))
      (node (ref "C78") (pin "2") (pinfunction "2_2") (pintype "passive"))
      (node (ref "C79") (pin "2") (pinfunction "2_2") (pintype "passive"))
      (node (ref "C8") (pin "2") (pinfunction "2_2") (pintype "passive"))
      (node (ref "C80") (pin "2") (pinfunction "2_2") (pintype "passive"))
      (node (ref "C81") (pin "2") (pinfunction "2_2") (pintype "passive"))
      (node (ref "C82") (pin "2") (pinfunction "2_2") (pintype "passive"))
      (node (ref "C83") (pin "2") (pinfunction "2_2") (pintype "passive"))
      (node (ref "C84") (pin "2") (pinfunction "2_2") (pintype "passive"))
      (node (ref "C85") (pin "2") (pinfunction "2_2") (pintype "passive"))
      (node (ref "C86") (pin "2") (pinfunction "2_2") (pintype "passive"))
      (node (ref "C87") (pin "2") (pinfunction "2_2") (pintype "passive"))
      (node (ref "C88") (pin "2") (pinfunction "2_2") (pintype "passive"))
      (node (ref "C89") (pin "2") (pinfunction "2_2") (pintype "passive"))
      (node (ref "C9") (pin "2") (pinfunction "2_2") (pintype "passive"))
      (node (ref "C90") (pin "2") (pinfunction "2_2") (pintype "passive"))
      (node (ref "C91") (pin "2") (pinfunction "2_2") (pintype "passive"))
      (node (ref "C92") (pin "2") (pinfunction "2_2") (pintype "passive"))
      (node (ref "C93") (pin "2") (pinfunction "2_2") (pintype "passive"))
      (node (ref "C94") (pin "2") (pinfunction "2_2") (pintype "passive"))
      (node (ref "C95") (pin "2") (pinfunction "2_2") (pintype "passive"))
      (node (ref "C96") (pin "2") (pinfunction "2_2") (pintype "passive"))
      (node (ref "C97") (pin "2") (pinfunction "2_2") (pintype "passive"))
      (node (ref "C98") (pin "2") (pinfunction "2_2") (pintype "passive"))
      (node (ref "C99") (pin "2") (pinfunction "2_2") (pintype "passive"))
      (node (ref "J2") (pin "1") (pinfunction "-_1") (pintype "bidirectional"))
      (node (ref "J3") (pin "6") (pinfunction "VSS_6") (pintype "bidirectional"))
      (node (ref "J3") (pin "CD2") (pinfunction "GND_CD2") (pintype "bidirectional"))
      (node (ref "J3") (pin "GND1") (pinfunction "SHIELD_GND1") (pintype "bidirectional"))
      (node (ref "J3") (pin "GND3") (pinfunction "SHIELD_GND3") (pintype "bidirectional"))
      (node (ref "J4") (pin "GND") (pinfunction "GND_GND") (pintype "bidirectional"))
      (node (ref "J4") (pin "GNDBREAK") (pinfunction "GNDBREAK_GNDBREAK") (pintype "bidirectional"))
      (node (ref "J5") (pin "11") (pinfunction "TGND_11") (pintype "bidirectional"))
      (node (ref "J5") (pin "17") (pinfunction "GND_17") (pintype "bidirectional"))
      (node (ref "J5") (pin "2") (pinfunction "TGND_2") (pintype "bidirectional"))
      (node (ref "J5") (pin "5") (pinfunction "TGND_5") (pintype "bidirectional"))
      (node (ref "J5") (pin "8") (pinfunction "TGND_8") (pintype "bidirectional"))
      (node (ref "J7") (pin "GND") (pinfunction "GND_GND") (pintype "bidirectional"))
      (node (ref "J8") (pin "12") (pinfunction "GND_12") (pintype "bidirectional"))
      (node (ref "J8") (pin "4") (pinfunction "GND_4") (pintype "bidirectional"))
      (node (ref "J8") (pin "8") (pinfunction "GND_8") (pintype "bidirectional"))
      (node (ref "J9") (pin "12") (pinfunction "GND_12") (pintype "bidirectional"))
      (node (ref "J9") (pin "4") (pinfunction "GND_4") (pintype "bidirectional"))
      (node (ref "J9") (pin "8") (pinfunction "GND_8") (pintype "bidirectional"))
      (node (ref "JP1") (pin "1") (pinfunction "1_1") (pintype "passive"))
      (node (ref "JP2") (pin "1") (pinfunction "1_1") (pintype "passive"))
      (node (ref "PT1") (pin "P$1") (pinfunction "P$1_P$1") (pintype "bidirectional"))
      (node (ref "PT2") (pin "P$1") (pinfunction "P$1_P$1") (pintype "bidirectional"))
      (node (ref "PT3") (pin "P$1") (pinfunction "P$1_P$1") (pintype "bidirectional"))
      (node (ref "PT4") (pin "P$1") (pinfunction "P$1_P$1") (pintype "bidirectional"))
      (node (ref "PT5") (pin "P$1") (pinfunction "P$1_P$1") (pintype "bidirectional"))
      (node (ref "PT6") (pin "P$1") (pinfunction "P$1_P$1") (pintype "bidirectional"))
      (node (ref "PT7") (pin "P$1") (pinfunction "P$1_P$1") (pintype "bidirectional"))
      (node (ref "PT8") (pin "P$1") (pinfunction "P$1_P$1") (pintype "bidirectional"))
      (node (ref "PT9") (pin "P$1") (pinfunction "P$1_P$1") (pintype "bidirectional"))
      (node (ref "R17") (pin "1") (pinfunction "1_1") (pintype "passive"))
      (node (ref "R18") (pin "1") (pinfunction "1_1") (pintype "passive"))
      (node (ref "R22") (pin "1") (pinfunction "1_1") (pintype "passive"))
      (node (ref "R23") (pin "1") (pinfunction "1_1") (pintype "passive"))
      (node (ref "R30") (pin "1") (pinfunction "1_1") (pintype "passive"))
      (node (ref "R32") (pin "1") (pinfunction "1_1") (pintype "passive"))
      (node (ref "R33") (pin "1") (pinfunction "1_1") (pintype "passive"))
      (node (ref "R36") (pin "1") (pinfunction "1_1") (pintype "passive"))
      (node (ref "R37") (pin "1") (pinfunction "1_1") (pintype "passive"))
      (node (ref "R40") (pin "1") (pinfunction "1_1") (pintype "passive"))
      (node (ref "R42") (pin "1") (pinfunction "1_1") (pintype "passive"))
      (node (ref "R43") (pin "1") (pinfunction "1_1") (pintype "passive"))
      (node (ref "R44") (pin "1") (pinfunction "1_1") (pintype "passive"))
      (node (ref "R50") (pin "1") (pinfunction "1_1") (pintype "passive"))
      (node (ref "R52") (pin "1") (pinfunction "1_1") (pintype "passive"))
      (node (ref "R54") (pin "2") (pinfunction "2_2") (pintype "passive"))
      (node (ref "R55") (pin "2") (pinfunction "2_2") (pintype "passive"))
      (node (ref "R56") (pin "1") (pinfunction "1_1") (pintype "passive"))
      (node (ref "R57") (pin "1") (pinfunction "1_1") (pintype "passive"))
      (node (ref "S1") (pin "P$1") (pinfunction "P$1_P$1") (pintype "bidirectional"))
      (node (ref "S2") (pin "P$1") (pinfunction "P$1_P$1") (pintype "bidirectional"))
      (node (ref "S3") (pin "P$1") (pinfunction "P$1_P$1") (pintype "bidirectional"))
      (node (ref "S4") (pin "P$1") (pinfunction "P$1_P$1") (pintype "bidirectional"))
      (node (ref "S5") (pin "P$1") (pinfunction "P$1_P$1") (pintype "bidirectional"))
      (node (ref "S7") (pin "P$1") (pinfunction "P$1_P$1") (pintype "bidirectional"))
      (node (ref "U$4") (pin "A1") (pinfunction "VSS_A1") (pintype "bidirectional"))
      (node (ref "U$4") (pin "A8") (pinfunction "VSS_A8") (pintype "bidirectional"))
      (node (ref "U$4") (pin "B1") (pinfunction "VSS_B1") (pintype "bidirectional"))
      (node (ref "U$4") (pin "B2") (pinfunction "VSSQ_B2") (pintype "bidirectional"))
      (node (ref "U$4") (pin "B8") (pinfunction "VSSQ_B8") (pintype "bidirectional"))
      (node (ref "U$4") (pin "C9") (pinfunction "VSSQ_C9") (pintype "bidirectional"))
      (node (ref "U$4") (pin "D1") (pinfunction "VSSQ_D1") (pintype "bidirectional"))
      (node (ref "U$4") (pin "D8") (pinfunction "VSS_D8") (pintype "bidirectional"))
      (node (ref "U$4") (pin "D9") (pinfunction "VSSQ_D9") (pintype "bidirectional"))
      (node (ref "U$4") (pin "F2") (pinfunction "VSS_F2") (pintype "bidirectional"))
      (node (ref "U$4") (pin "F8") (pinfunction "VSS_F8") (pintype "bidirectional"))
      (node (ref "U$4") (pin "H2") (pinfunction "~{CS}_H2") (pintype "bidirectional"))
      (node (ref "U$4") (pin "J1") (pinfunction "VSS_J1") (pintype "bidirectional"))
      (node (ref "U$4") (pin "J9") (pinfunction "VSS_J9") (pintype "bidirectional"))
      (node (ref "U$4") (pin "L1") (pinfunction "VSS_L1") (pintype "bidirectional"))
      (node (ref "U$4") (pin "L9") (pinfunction "VSS_L9") (pintype "bidirectional"))
      (node (ref "U$4") (pin "N1") (pinfunction "VSS_N1") (pintype "bidirectional"))
      (node (ref "U$4") (pin "N9") (pinfunction "VSS_N9") (pintype "bidirectional"))
      (node (ref "U$5") (pin "A1") (pinfunction "VSS_A1") (pintype "bidirectional"))
      (node (ref "U$5") (pin "A8") (pinfunction "VSS_A8") (pintype "bidirectional"))
      (node (ref "U$5") (pin "B1") (pinfunction "VSS_B1") (pintype "bidirectional"))
      (node (ref "U$5") (pin "B2") (pinfunction "VSSQ_B2") (pintype "bidirectional"))
      (node (ref "U$5") (pin "B8") (pinfunction "VSSQ_B8") (pintype "bidirectional"))
      (node (ref "U$5") (pin "C9") (pinfunction "VSSQ_C9") (pintype "bidirectional"))
      (node (ref "U$5") (pin "D1") (pinfunction "VSSQ_D1") (pintype "bidirectional"))
      (node (ref "U$5") (pin "D8") (pinfunction "VSS_D8") (pintype "bidirectional"))
      (node (ref "U$5") (pin "D9") (pinfunction "VSSQ_D9") (pintype "bidirectional"))
      (node (ref "U$5") (pin "F2") (pinfunction "VSS_F2") (pintype "bidirectional"))
      (node (ref "U$5") (pin "F8") (pinfunction "VSS_F8") (pintype "bidirectional"))
      (node (ref "U$5") (pin "H2") (pinfunction "~{CS}_H2") (pintype "bidirectional"))
      (node (ref "U$5") (pin "J1") (pinfunction "VSS_J1") (pintype "bidirectional"))
      (node (ref "U$5") (pin "J9") (pinfunction "VSS_J9") (pintype "bidirectional"))
      (node (ref "U$5") (pin "L1") (pinfunction "VSS_L1") (pintype "bidirectional"))
      (node (ref "U$5") (pin "L9") (pinfunction "VSS_L9") (pintype "bidirectional"))
      (node (ref "U$5") (pin "N1") (pinfunction "VSS_N1") (pintype "bidirectional"))
      (node (ref "U$5") (pin "N9") (pinfunction "VSS_N9") (pintype "bidirectional"))
      (node (ref "U1") (pin "79") (pinfunction "AGND_79") (pintype "bidirectional"))
      (node (ref "U1") (pin "EP") (pinfunction "GND_EP") (pintype "bidirectional"))
      (node (ref "U10") (pin "14") (pinfunction "VSSTX_14") (pintype "bidirectional"))
      (node (ref "U10") (pin "17") (pinfunction "VSSPLL_17") (pintype "bidirectional"))
      (node (ref "U10") (pin "18") (pinfunction "VSSOSC_18") (pintype "bidirectional"))
      (node (ref "U10") (pin "26") (pinfunction "VSS_26") (pintype "bidirectional"))
      (node (ref "U10") (pin "7") (pinfunction "VSSRX_7") (pintype "bidirectional"))
      (node (ref "U10") (pin "EP") (pinfunction "VSS_EP") (pintype "bidirectional"))
      (node (ref "U11") (pin "13") (pinfunction "VSS_13") (pintype "bidirectional"))
      (node (ref "U11") (pin "36") (pinfunction "VSS_36") (pintype "bidirectional"))
      (node (ref "U12") (pin "24") (pinfunction "GND_24") (pintype "bidirectional"))
      (node (ref "U12") (pin "43") (pinfunction "GND_43") (pintype "bidirectional"))
      (node (ref "U12") (pin "48") (pinfunction "MODE_48") (pintype "bidirectional"))
      (node (ref "U12") (pin "5") (pinfunction "GND_5") (pintype "bidirectional"))
      (node (ref "U13") (pin "5") (pinfunction "GND_5") (pintype "bidirectional"))
      (node (ref "U14") (pin "1") (pinfunction "GND_1") (pintype "bidirectional"))
      (node (ref "U14") (pin "EP") (pinfunction "GND_EP") (pintype "bidirectional"))
      (node (ref "U15") (pin "1") (pinfunction "GND_1") (pintype "bidirectional"))
      (node (ref "U15") (pin "EP") (pinfunction "GND_EP") (pintype "bidirectional"))
      (node (ref "U16") (pin "1") (pinfunction "GND_1") (pintype "bidirectional"))
      (node (ref "U16") (pin "EP") (pinfunction "GND_EP") (pintype "bidirectional"))
      (node (ref "U19") (pin "2") (pinfunction "GND_2") (pintype "bidirectional"))
      (node (ref "U2") (pin "16") (pinfunction "PGND3_16") (pintype "bidirectional"))
      (node (ref "U2") (pin "22") (pinfunction "AGND_22") (pintype "bidirectional"))
      (node (ref "U2") (pin "46") (pinfunction "PGND1_46") (pintype "bidirectional"))
      (node (ref "U2") (pin "9") (pinfunction "PGND2_9") (pintype "bidirectional"))
      (node (ref "U2") (pin "EP") (pinfunction "GND_EP") (pintype "bidirectional"))
      (node (ref "U20") (pin "2") (pinfunction "GND_2") (pintype "bidirectional"))
      (node (ref "U21") (pin "2") (pinfunction "GND_2") (pintype "bidirectional"))
      (node (ref "U3") (pin "1") (pinfunction "GND_1") (pintype "bidirectional"))
      (node (ref "U4") (pin "13") (pinfunction "GND_13") (pintype "bidirectional"))
      (node (ref "U4") (pin "21") (pinfunction "GND_21") (pintype "bidirectional"))
      (node (ref "U4") (pin "22") (pinfunction "GND_22") (pintype "bidirectional"))
      (node (ref "U5") (pin "2") (pinfunction "AGND_2") (pintype "bidirectional"))
      (node (ref "U6") (pin "2") (pinfunction "GND_2") (pintype "bidirectional"))
      (node (ref "U7") (pin "2") (pinfunction "GND_2") (pintype "bidirectional"))
      (node (ref "U8") (pin "4") (pinfunction "AGND_4") (pintype "bidirectional"))
      (node (ref "U8") (pin "5") (pinfunction "SYNC_5") (pintype "bidirectional"))
      (node (ref "U9") (pin "10") (pinfunction "~{PD}_10") (pintype "bidirectional"))
      (node (ref "U9") (pin "16") (pinfunction "DGND_16") (pintype "bidirectional"))
      (node (ref "U9") (pin "17") (pinfunction "PGND_17") (pintype "bidirectional"))
      (node (ref "U9") (pin "20") (pinfunction "TGND_20") (pintype "bidirectional"))
      (node (ref "U9") (pin "26") (pinfunction "TGND_26") (pintype "bidirectional"))
      (node (ref "U9") (pin "32") (pinfunction "TGND_32") (pintype "bidirectional"))
      (node (ref "U9") (pin "34") (pinfunction "RESERVED_34") (pintype "bidirectional"))
      (node (ref "U9") (pin "35") (pinfunction "DKEN_35") (pintype "bidirectional"))
      (node (ref "U9") (pin "42") (pinfunction "D17_42") (pintype "bidirectional"))
      (node (ref "U9") (pin "43") (pinfunction "D16_43") (pintype "bidirectional"))
      (node (ref "U9") (pin "48") (pinfunction "DGND_48") (pintype "bidirectional"))
      (node (ref "U9") (pin "52") (pinfunction "D9_52") (pintype "bidirectional"))
      (node (ref "U9") (pin "53") (pinfunction "D8_53") (pintype "bidirectional"))
      (node (ref "U9") (pin "56") (pinfunction "IDCK-_56") (pintype "bidirectional"))
      (node (ref "U9") (pin "6") (pinfunction "CTL3/A3/DK3_6") (pintype "bidirectional"))
      (node (ref "U9") (pin "62") (pinfunction "D1_62") (pintype "bidirectional"))
      (node (ref "U9") (pin "63") (pinfunction "D0_63") (pintype "bidirectional"))
      (node (ref "U9") (pin "64") (pinfunction "DGND_64") (pintype "bidirectional"))
      (node (ref "U9") (pin "7") (pinfunction "CTL2/A2/DK2_7") (pintype "bidirectional"))
      (node (ref "U9") (pin "8") (pinfunction "CTL1/A1/DK1_8") (pintype "bidirectional"))
      (node (ref "U9") (pin "EP") (pinfunction "EP_EP") (pintype "bidirectional"))
      (node (ref "Y1") (pin "2") (pinfunction "GND_2") (pintype "bidirectional"))
      (node (ref "Y1") (pin "4") (pinfunction "GND_4") (pintype "bidirectional"))
      (node (ref "Y2") (pin "2") (pinfunction "GND_2") (pintype "bidirectional"))
      (node (ref "Y2") (pin "4") (pinfunction "GND_4") (pintype "bidirectional"))
      (node (ref "Y3") (pin "2") (pinfunction "GND_2") (pintype "bidirectional"))
      (node (ref "Y3") (pin "4") (pinfunction "GND_4") (pintype "bidirectional"))
    )
    (net (code "74") (name "HTPLG") (class "Default")
      (node (ref "J5") (pin "19") (pinfunction "HOTPLUG_19") (pintype "bidirectional"))
      (node (ref "R11") (pin "1") (pinfunction "1_1") (pintype "passive"))
    )
    (net (code "75") (name "IPSOUT") (class "Default")
      (node (ref "C16") (pin "1") (pinfunction "1_1") (pintype "passive"))
      (node (ref "C17") (pin "1") (pinfunction "1_1") (pintype "passive"))
      (node (ref "C18") (pin "1") (pinfunction "1_1") (pintype "passive"))
      (node (ref "C19") (pin "1") (pinfunction "1_1") (pintype "passive"))
      (node (ref "C20") (pin "1") (pinfunction "1_1") (pintype "passive"))
      (node (ref "C21") (pin "1") (pinfunction "1_1") (pintype "passive"))
      (node (ref "C77") (pin "1") (pinfunction "1_1") (pintype "passive"))
      (node (ref "C78") (pin "1") (pinfunction "1_1") (pintype "passive"))
      (node (ref "JP2") (pin "3") (pinfunction "3_3") (pintype "passive"))
      (node (ref "L5") (pin "1") (pinfunction "1_1") (pintype "passive"))
      (node (ref "LED1") (pin "A") (pinfunction "A_A") (pintype "passive"))
      (node (ref "S6") (pin "P$1") (pinfunction "P$1_P$1") (pintype "bidirectional"))
      (node (ref "U2") (pin "13") (pinfunction "LDO24IN_13") (pintype "bidirectional"))
      (node (ref "U2") (pin "14") (pinfunction "VIN3_14") (pintype "bidirectional"))
      (node (ref "U2") (pin "21") (pinfunction "APS_21") (pintype "bidirectional"))
      (node (ref "U2") (pin "34") (pinfunction "IPSOUT_34") (pintype "bidirectional"))
      (node (ref "U2") (pin "35") (pinfunction "IPSOUT_35") (pintype "bidirectional"))
      (node (ref "U2") (pin "40") (pinfunction "LDO3IN_40") (pintype "bidirectional"))
      (node (ref "U2") (pin "44") (pinfunction "VIN1_44") (pintype "bidirectional"))
      (node (ref "U2") (pin "7") (pinfunction "VIN2_7") (pintype "bidirectional"))
      (node (ref "U5") (pin "6") (pinfunction "VIN_6") (pintype "bidirectional"))
      (node (ref "U5") (pin "8") (pinfunction "EN_8") (pintype "bidirectional"))
      (node (ref "U6") (pin "6") (pinfunction "PVDD_6") (pintype "bidirectional"))
      (node (ref "U6") (pin "7") (pinfunction "PVDD_7") (pintype "bidirectional"))
      (node (ref "U6") (pin "8") (pinfunction "VDD_8") (pintype "bidirectional"))
      (node (ref "U7") (pin "6") (pinfunction "PVDD_6") (pintype "bidirectional"))
      (node (ref "U7") (pin "7") (pinfunction "PVDD_7") (pintype "bidirectional"))
      (node (ref "U7") (pin "8") (pinfunction "VDD_8") (pintype "bidirectional"))
    )
    (net (code "76") (name "LX1") (class "Default")
      (node (ref "C23") (pin "1") (pinfunction "1_1") (pintype "passive"))
      (node (ref "C24") (pin "1") (pinfunction "1_1") (pintype "passive"))
      (node (ref "C28") (pin "1") (pinfunction "1_1") (pintype "passive"))
      (node (ref "L1") (pin "2") (pinfunction "2_2") (pintype "passive"))
      (node (ref "R19") (pin "1") (pinfunction "1_1") (pintype "passive"))
      (node (ref "U2") (pin "43") (pinfunction "CHSENSE_43") (pintype "bidirectional"))
    )
    (net (code "77") (name "MSEN") (class "Default")
      (node (ref "R51") (pin "1") (pinfunction "1_1") (pintype "passive"))
      (node (ref "U1") (pin "103") (pinfunction "PB2/EINT16_103") (pintype "bidirectional"))
      (node (ref "U9") (pin "11") (pinfunction "MSEN/PO1_11") (pintype "bidirectional"))
    )
    (net (code "78") (name "Net-(C4-Pad1)") (class "Default")
      (node (ref "C4") (pin "1") (pinfunction "1_1") (pintype "passive"))
      (node (ref "RN12") (pin "1") (pinfunction "1_1") (pintype "passive"))
    )
    (net (code "79") (name "Net-(C9-Pad1)") (class "Default")
      (node (ref "C9") (pin "1") (pinfunction "1_1") (pintype "passive"))
      (node (ref "R12") (pin "1") (pinfunction "1_1") (pintype "passive"))
    )
    (net (code "80") (name "Net-(C12-Pad+)") (class "Default")
      (node (ref "C12") (pin "+") (pinfunction "+_+") (pintype "passive"))
      (node (ref "C13") (pin "1") (pinfunction "1_1") (pintype "passive"))
      (node (ref "J7") (pin "VBUS") (pinfunction "VBUS_VBUS") (pintype "bidirectional"))
      (node (ref "R16") (pin "2") (pinfunction "2_2") (pintype "passive"))
      (node (ref "U3") (pin "6") (pinfunction "OUT_6") (pintype "bidirectional"))
      (node (ref "U3") (pin "7") (pinfunction "OUT_7") (pintype "bidirectional"))
    )
    (net (code "81") (name "Net-(C67-Pad1)") (class "Default")
      (node (ref "C67") (pin "1") (pinfunction "1_1") (pintype "passive"))
      (node (ref "R34") (pin "1") (pinfunction "1_1") (pintype "passive"))
    )
    (net (code "82") (name "Net-(C68-Pad1)") (class "Default")
      (node (ref "C68") (pin "1") (pinfunction "1_1") (pintype "passive"))
      (node (ref "R38") (pin "1") (pinfunction "1_1") (pintype "passive"))
    )
    (net (code "83") (name "Net-(D1-PadCATHODE)") (class "Default")
      (node (ref "D1") (pin "CATHODE") (pinfunction "CATHODE_CATHODE") (pintype "bidirectional"))
      (node (ref "R1") (pin "2") (pinfunction "2_2") (pintype "passive"))
    )
    (net (code "84") (name "Net-(D2-P$1)") (class "Default")
      (node (ref "D2") (pin "2") (pinfunction "P$1_2") (pintype "bidirectional"))
      (node (ref "L5") (pin "2") (pinfunction "2_2") (pintype "passive"))
      (node (ref "U5") (pin "4") (pinfunction "SW_4") (pintype "bidirectional"))
    )
    (net (code "85") (name "Net-(D2-P$2)") (class "Default")
      (node (ref "C65") (pin "1") (pinfunction "1_1") (pintype "passive"))
      (node (ref "C66") (pin "1") (pinfunction "1_1") (pintype "passive"))
      (node (ref "D2") (pin "1") (pinfunction "P$2_1") (pintype "bidirectional"))
      (node (ref "Q1") (pin "3") (pinfunction "D_3") (pintype "bidirectional"))
      (node (ref "R31") (pin "2") (pinfunction "2_2") (pintype "passive"))
    )
    (net (code "86") (name "Net-(J1-RING)") (class "Default")
      (node (ref "J1") (pin "3") (pinfunction "RING_3") (pintype "bidirectional"))
      (node (ref "RN12") (pin "6") (pinfunction "2_6") (pintype "passive"))
      (node (ref "U1") (pin "78") (pinfunction "HPOUTR_78") (pintype "bidirectional"))
    )
    (net (code "87") (name "Net-(J1-SLEEVE)") (class "Default")
      (node (ref "J1") (pin "1") (pinfunction "SLEEVE_1") (pintype "bidirectional"))
      (node (ref "RN12") (pin "7") (pinfunction "2_7") (pintype "passive"))
      (node (ref "U1") (pin "77") (pinfunction "HPCOM_77") (pintype "bidirectional"))
    )
    (net (code "88") (name "Net-(J1-TIP)") (class "Default")
      (node (ref "J1") (pin "2") (pinfunction "TIP_2") (pintype "bidirectional"))
      (node (ref "RN12") (pin "5") (pinfunction "2_5") (pintype "passive"))
      (node (ref "U1") (pin "74") (pinfunction "HPOUTL_74") (pintype "bidirectional"))
    )
    (net (code "89") (name "Net-(J3-CLK)") (class "Default")
      (node (ref "J3") (pin "5") (pinfunction "CLK_5") (pintype "bidirectional"))
      (node (ref "U1") (pin "110") (pinfunction "SDC0_CLK_110") (pintype "bidirectional"))
    )
    (net (code "90") (name "Net-(J3-CMD)") (class "Default")
      (node (ref "J3") (pin "3") (pinfunction "CMD_3") (pintype "bidirectional"))
      (node (ref "R26") (pin "1") (pinfunction "1_1") (pintype "passive"))
      (node (ref "U1") (pin "111") (pinfunction "SDC0_CMD_111") (pintype "bidirectional"))
    )
    (net (code "91") (name "Net-(J3-DAT0)") (class "Default")
      (node (ref "J3") (pin "7") (pinfunction "DAT0_7") (pintype "bidirectional"))
      (node (ref "R25") (pin "1") (pinfunction "1_1") (pintype "passive"))
      (node (ref "U1") (pin "108") (pinfunction "SDC0_D0_108") (pintype "bidirectional"))
    )
    (net (code "92") (name "Net-(J3-DAT1)") (class "Default")
      (node (ref "J3") (pin "8") (pinfunction "DAT1_8") (pintype "bidirectional"))
      (node (ref "R24") (pin "1") (pinfunction "1_1") (pintype "passive"))
      (node (ref "U1") (pin "107") (pinfunction "SDC0_D1_107") (pintype "bidirectional"))
    )
    (net (code "93") (name "Net-(J3-DAT2)") (class "Default")
      (node (ref "J3") (pin "1") (pinfunction "DAT2_1") (pintype "bidirectional"))
      (node (ref "R28") (pin "1") (pinfunction "1_1") (pintype "passive"))
      (node (ref "U1") (pin "113") (pinfunction "SDC0_D2_113") (pintype "bidirectional"))
    )
    (net (code "94") (name "Net-(J3-DAT3)") (class "Default")
      (node (ref "J3") (pin "2") (pinfunction "DAT3_2") (pintype "bidirectional"))
      (node (ref "R27") (pin "1") (pinfunction "1_1") (pintype "passive"))
      (node (ref "U1") (pin "112") (pinfunction "SDC0_D3_112") (pintype "bidirectional"))
    )
    (net (code "95") (name "Net-(J3-VCC)") (class "Default")
      (node (ref "C33") (pin "1") (pinfunction "1_1") (pintype "passive"))
      (node (ref "C34") (pin "1") (pinfunction "1_1") (pintype "passive"))
      (node (ref "J3") (pin "4") (pinfunction "VCC_4") (pintype "bidirectional"))
      (node (ref "L4") (pin "2") (pinfunction "2_2") (pintype "passive"))
    )
    (net (code "96") (name "Net-(J5-TX0+)") (class "Default")
      (node (ref "J5") (pin "7") (pinfunction "TX0+_7") (pintype "bidirectional"))
      (node (ref "U9") (pin "25") (pinfunction "TX0+_25") (pintype "bidirectional"))
    )
    (net (code "97") (name "Net-(J5-TX0-)") (class "Default")
      (node (ref "J5") (pin "9") (pinfunction "TX0-_9") (pintype "bidirectional"))
      (node (ref "U9") (pin "24") (pinfunction "TX0-_24") (pintype "bidirectional"))
    )
    (net (code "98") (name "Net-(J5-TX1+)") (class "Default")
      (node (ref "J5") (pin "4") (pinfunction "TX1+_4") (pintype "bidirectional"))
      (node (ref "U9") (pin "28") (pinfunction "TX1+_28") (pintype "bidirectional"))
    )
    (net (code "99") (name "Net-(J5-TX1-)") (class "Default")
      (node (ref "J5") (pin "6") (pinfunction "TX1-_6") (pintype "bidirectional"))
      (node (ref "U9") (pin "27") (pinfunction "TX1-_27") (pintype "bidirectional"))
    )
    (net (code "100") (name "Net-(J5-TX2+)") (class "Default")
      (node (ref "J5") (pin "1") (pinfunction "TX2+_1") (pintype "bidirectional"))
      (node (ref "U9") (pin "31") (pinfunction "TX2+_31") (pintype "bidirectional"))
    )
    (net (code "101") (name "Net-(J5-TX2-)") (class "Default")
      (node (ref "J5") (pin "3") (pinfunction "TX2-_3") (pintype "bidirectional"))
      (node (ref "U9") (pin "30") (pinfunction "TX2-_30") (pintype "bidirectional"))
    )
    (net (code "102") (name "Net-(J5-TXC+)") (class "Default")
      (node (ref "J5") (pin "10") (pinfunction "TXC+_10") (pintype "bidirectional"))
      (node (ref "U9") (pin "22") (pinfunction "TXC+_22") (pintype "bidirectional"))
    )
    (net (code "103") (name "Net-(J5-TXC-)") (class "Default")
      (node (ref "J5") (pin "12") (pinfunction "TXC-_12") (pintype "bidirectional"))
      (node (ref "U9") (pin "21") (pinfunction "TXC-_21") (pintype "bidirectional"))
    )
    (net (code "104") (name "Net-(J6A-R1)") (class "Default")
      (node (ref "J6") (pin "1") (pinfunction "R1_1") (pintype "bidirectional"))
      (node (ref "R58") (pin "1") (pinfunction "1_1") (pintype "passive"))
      (node (ref "U10") (pin "13") (pinfunction "TPOUT+_13") (pintype "bidirectional"))
    )
    (net (code "105") (name "Net-(J6A-R2)") (class "Default")
      (node (ref "J6") (pin "2") (pinfunction "R2_2") (pintype "bidirectional"))
      (node (ref "R59") (pin "1") (pinfunction "1_1") (pintype "passive"))
      (node (ref "U10") (pin "12") (pinfunction "TPOUT-_12") (pintype "bidirectional"))
    )
    (net (code "106") (name "Net-(J6A-R3)") (class "Default")
      (node (ref "C111") (pin "1") (pinfunction "1_1") (pintype "passive"))
      (node (ref "J6") (pin "3") (pinfunction "R3_3") (pintype "bidirectional"))
      (node (ref "L9") (pin "1") (pinfunction "1_1") (pintype "passive"))
      (node (ref "R58") (pin "2") (pinfunction "2_2") (pintype "passive"))
      (node (ref "R59") (pin "2") (pinfunction "2_2") (pintype "passive"))
    )
    (net (code "107") (name "Net-(J6A-R7)") (class "Default")
      (node (ref "J6") (pin "7") (pinfunction "R7_7") (pintype "bidirectional"))
      (node (ref "R56") (pin "2") (pinfunction "2_2") (pintype "passive"))
      (node (ref "U10") (pin "9") (pinfunction "TPIN+_9") (pintype "bidirectional"))
    )
    (net (code "108") (name "Net-(J6A-R8)") (class "Default")
      (node (ref "J6") (pin "8") (pinfunction "R8_8") (pintype "bidirectional"))
      (node (ref "R57") (pin "2") (pinfunction "2_2") (pintype "passive"))
      (node (ref "U10") (pin "8") (pinfunction "TPIN-_8") (pintype "bidirectional"))
    )
    (net (code "109") (name "Net-(J6B-A)") (class "Default")
      (node (ref "J6") (pin "L3") (pinfunction "A_L3") (pintype "passive"))
      (node (ref "U10") (pin "23") (pinfunction "LEDA_23") (pintype "bidirectional"))
    )
    (net (code "110") (name "Net-(J6B-C)") (class "Default")
      (node (ref "J6") (pin "L4") (pinfunction "C_L4") (pintype "passive"))
      (node (ref "R55") (pin "1") (pinfunction "1_1") (pintype "passive"))
    )
    (net (code "111") (name "Net-(J6C-A)") (class "Default")
      (node (ref "J6") (pin "L1") (pinfunction "A_L1") (pintype "passive"))
      (node (ref "U10") (pin "22") (pinfunction "LEDB_22") (pintype "bidirectional"))
    )
    (net (code "112") (name "Net-(J6C-C)") (class "Default")
      (node (ref "J6") (pin "L2") (pinfunction "C_L2") (pintype "passive"))
      (node (ref "R54") (pin "1") (pinfunction "1_1") (pintype "passive"))
    )
    (net (code "113") (name "Net-(J7-PadD+)") (class "Default")
      (node (ref "J7") (pin "D+") (pinfunction "D+_D+") (pintype "bidirectional"))
      (node (ref "R65") (pin "2") (pinfunction "2_2") (pintype "passive"))
    )
    (net (code "114") (name "Net-(J7-PadD-)") (class "Default")
      (node (ref "J7") (pin "D-") (pinfunction "D-_D-") (pintype "bidirectional"))
      (node (ref "R66") (pin "2") (pinfunction "2_2") (pintype "passive"))
    )
    (net (code "115") (name "Net-(J8A-D+)") (class "Default")
      (node (ref "J8") (pin "3") (pinfunction "D+_3") (pintype "bidirectional"))
      (node (ref "RN13") (pin "6") (pinfunction "2_6") (pintype "passive"))
    )
    (net (code "116") (name "Net-(J8A-D-)") (class "Default")
      (node (ref "J8") (pin "2") (pinfunction "D-_2") (pintype "bidirectional"))
      (node (ref "RN13") (pin "5") (pinfunction "2_5") (pintype "passive"))
    )
    (net (code "117") (name "Net-(J8A-VBUS)") (class "Default")
      (node (ref "C120") (pin "+") (pinfunction "+_+") (pintype "passive"))
      (node (ref "J8") (pin "1") (pinfunction "VBUS_1") (pintype "bidirectional"))
      (node (ref "U14") (pin "7") (pinfunction "OUT_7") (pintype "bidirectional"))
    )
    (net (code "118") (name "Net-(J8B-D+)") (class "Default")
      (node (ref "J8") (pin "7") (pinfunction "D+_7") (pintype "bidirectional"))
      (node (ref "RN13") (pin "8") (pinfunction "2_8") (pintype "passive"))
    )
    (net (code "119") (name "Net-(J8B-D-)") (class "Default")
      (node (ref "J8") (pin "6") (pinfunction "D-_6") (pintype "bidirectional"))
      (node (ref "RN13") (pin "7") (pinfunction "2_7") (pintype "passive"))
    )
    (net (code "120") (name "Net-(J8B-VBUS)") (class "Default")
      (node (ref "C121") (pin "+") (pinfunction "+_+") (pintype "passive"))
      (node (ref "J8") (pin "5") (pinfunction "VBUS_5") (pintype "bidirectional"))
      (node (ref "U14") (pin "6") (pinfunction "OUT_6") (pintype "bidirectional"))
    )
    (net (code "121") (name "Net-(J8C-D+)") (class "Default")
      (node (ref "J8") (pin "11") (pinfunction "D+_11") (pintype "bidirectional"))
      (node (ref "RN14") (pin "6") (pinfunction "2_6") (pintype "passive"))
    )
    (net (code "122") (name "Net-(J8C-D-)") (class "Default")
      (node (ref "J8") (pin "10") (pinfunction "D-_10") (pintype "bidirectional"))
      (node (ref "RN14") (pin "5") (pinfunction "2_5") (pintype "passive"))
    )
    (net (code "123") (name "Net-(J8C-VBUS)") (class "Default")
      (node (ref "C122") (pin "+") (pinfunction "+_+") (pintype "passive"))
      (node (ref "J8") (pin "9") (pinfunction "VBUS_9") (pintype "bidirectional"))
      (node (ref "U15") (pin "7") (pinfunction "OUT_7") (pintype "bidirectional"))
    )
    (net (code "124") (name "Net-(J9A-D+)") (class "Default")
      (node (ref "J9") (pin "3") (pinfunction "D+_3") (pintype "bidirectional"))
      (node (ref "RN14") (pin "8") (pinfunction "2_8") (pintype "passive"))
    )
    (net (code "125") (name "Net-(J9A-D-)") (class "Default")
      (node (ref "J9") (pin "2") (pinfunction "D-_2") (pintype "bidirectional"))
      (node (ref "RN14") (pin "7") (pinfunction "2_7") (pintype "passive"))
    )
    (net (code "126") (name "Net-(J9A-VBUS)") (class "Default")
      (node (ref "C123") (pin "+") (pinfunction "+_+") (pintype "passive"))
      (node (ref "J9") (pin "1") (pinfunction "VBUS_1") (pintype "bidirectional"))
      (node (ref "U15") (pin "6") (pinfunction "OUT_6") (pintype "bidirectional"))
    )
    (net (code "127") (name "Net-(J9B-D+)") (class "Default")
      (node (ref "J9") (pin "7") (pinfunction "D+_7") (pintype "bidirectional"))
      (node (ref "RN15") (pin "6") (pinfunction "2_6") (pintype "passive"))
    )
    (net (code "128") (name "Net-(J9B-D-)") (class "Default")
      (node (ref "J9") (pin "6") (pinfunction "D-_6") (pintype "bidirectional"))
      (node (ref "RN15") (pin "5") (pinfunction "2_5") (pintype "passive"))
    )
    (net (code "129") (name "Net-(J9B-VBUS)") (class "Default")
      (node (ref "C124") (pin "+") (pinfunction "+_+") (pintype "passive"))
      (node (ref "J9") (pin "5") (pinfunction "VBUS_5") (pintype "bidirectional"))
      (node (ref "U16") (pin "7") (pinfunction "OUT_7") (pintype "bidirectional"))
    )
    (net (code "130") (name "Net-(J9C-D+)") (class "Default")
      (node (ref "J9") (pin "11") (pinfunction "D+_11") (pintype "bidirectional"))
      (node (ref "RN15") (pin "8") (pinfunction "2_8") (pintype "passive"))
    )
    (net (code "131") (name "Net-(J9C-D-)") (class "Default")
      (node (ref "J9") (pin "10") (pinfunction "D-_10") (pintype "bidirectional"))
      (node (ref "RN15") (pin "7") (pinfunction "2_7") (pintype "passive"))
    )
    (net (code "132") (name "Net-(J9C-VBUS)") (class "Default")
      (node (ref "C125") (pin "+") (pinfunction "+_+") (pintype "passive"))
      (node (ref "J9") (pin "9") (pinfunction "VBUS_9") (pintype "bidirectional"))
      (node (ref "U16") (pin "6") (pinfunction "OUT_6") (pintype "bidirectional"))
    )
    (net (code "133") (name "Net-(L6-Pad1)") (class "Default")
      (node (ref "L6") (pin "1") (pinfunction "1_1") (pintype "passive"))
      (node (ref "U6") (pin "3") (pinfunction "SW_3") (pintype "bidirectional"))
      (node (ref "U6") (pin "4") (pinfunction "SW_4") (pintype "bidirectional"))
    )
    (net (code "134") (name "Net-(L7-Pad1)") (class "Default")
      (node (ref "L7") (pin "1") (pinfunction "1_1") (pintype "passive"))
      (node (ref "U7") (pin "3") (pinfunction "SW_3") (pintype "bidirectional"))
      (node (ref "U7") (pin "4") (pinfunction "SW_4") (pintype "bidirectional"))
    )
    (net (code "135") (name "Net-(LED1-PadC)") (class "Default")
      (node (ref "LED1") (pin "C") (pinfunction "C_C") (pintype "passive"))
      (node (ref "R20") (pin "2") (pinfunction "2_2") (pintype "passive"))
    )
    (net (code "136") (name "Net-(Q1-G)") (class "Default")
      (node (ref "C81") (pin "1") (pinfunction "1_1") (pintype "passive"))
      (node (ref "C82") (pin "1") (pinfunction "1_1") (pintype "passive"))
      (node (ref "D3") (pin "A") (pinfunction "A_A") (pintype "bidirectional"))
      (node (ref "L8") (pin "2") (pinfunction "2_2") (pintype "passive"))
      (node (ref "Q1") (pin "1") (pinfunction "G_1") (pintype "bidirectional"))
      (node (ref "R41") (pin "2") (pinfunction "2_2") (pintype "passive"))
    )
    (net (code "137") (name "Net-(R2-Pad2)") (class "Default")
      (node (ref "R2") (pin "2") (pinfunction "2_2") (pintype "passive"))
      (node (ref "R3") (pin "1") (pinfunction "1_1") (pintype "passive"))
      (node (ref "S1") (pin "P$2") (pinfunction "P$2_P$2") (pintype "bidirectional"))
    )
    (net (code "138") (name "Net-(R3-Pad2)") (class "Default")
      (node (ref "R3") (pin "2") (pinfunction "2_2") (pintype "passive"))
      (node (ref "R4") (pin "1") (pinfunction "1_1") (pintype "passive"))
      (node (ref "S2") (pin "P$2") (pinfunction "P$2_P$2") (pintype "bidirectional"))
    )
    (net (code "139") (name "Net-(R4-Pad2)") (class "Default")
      (node (ref "R4") (pin "2") (pinfunction "2_2") (pintype "passive"))
      (node (ref "R5") (pin "1") (pinfunction "1_1") (pintype "passive"))
      (node (ref "S3") (pin "P$2") (pinfunction "P$2_P$2") (pintype "bidirectional"))
    )
    (net (code "140") (name "Net-(R5-Pad2)") (class "Default")
      (node (ref "R5") (pin "2") (pinfunction "2_2") (pintype "passive"))
      (node (ref "R6") (pin "1") (pinfunction "1_1") (pintype "passive"))
      (node (ref "S4") (pin "P$2") (pinfunction "P$2_P$2") (pintype "bidirectional"))
    )
    (net (code "141") (name "Net-(R21-Pad2)") (class "Default")
      (node (ref "R21") (pin "2") (pinfunction "2_2") (pintype "passive"))
      (node (ref "S7") (pin "P$2") (pinfunction "P$2_P$2") (pintype "bidirectional"))
    )
    (net (code "142") (name "Net-(RN1A-2)") (class "Default")
      (node (ref "RN1") (pin "5") (pinfunction "2_5") (pintype "passive"))
      (node (ref "U1") (pin "22") (pinfunction "DDR3_D0_22") (pintype "bidirectional"))
    )
    (net (code "143") (name "Net-(RN1B-2)") (class "Default")
      (node (ref "RN1") (pin "6") (pinfunction "2_6") (pintype "passive"))
      (node (ref "U1") (pin "21") (pinfunction "DDR3_D2_21") (pintype "bidirectional"))
    )
    (net (code "144") (name "Net-(RN1C-2)") (class "Default")
      (node (ref "RN1") (pin "7") (pinfunction "2_7") (pintype "passive"))
      (node (ref "U1") (pin "20") (pinfunction "DDR3_D6_20") (pintype "bidirectional"))
    )
    (net (code "145") (name "Net-(RN1D-2)") (class "Default")
      (node (ref "RN1") (pin "8") (pinfunction "2_8") (pintype "passive"))
      (node (ref "U1") (pin "19") (pinfunction "DDR3_D4_19") (pintype "bidirectional"))
    )
    (net (code "146") (name "Net-(RN2A-2)") (class "Default")
      (node (ref "RN2") (pin "5") (pinfunction "2_5") (pintype "passive"))
      (node (ref "U1") (pin "39") (pinfunction "DDR3_D10_39") (pintype "bidirectional"))
    )
    (net (code "147") (name "Net-(RN2B-2)") (class "Default")
      (node (ref "RN2") (pin "6") (pinfunction "2_6") (pintype "passive"))
      (node (ref "U1") (pin "38") (pinfunction "DDR3_D14_38") (pintype "bidirectional"))
    )
    (net (code "148") (name "Net-(RN2C-2)") (class "Default")
      (node (ref "RN2") (pin "7") (pinfunction "2_7") (pintype "passive"))
      (node (ref "U1") (pin "37") (pinfunction "DDR3_D8_37") (pintype "bidirectional"))
    )
    (net (code "149") (name "Net-(RN2D-2)") (class "Default")
      (node (ref "RN2") (pin "8") (pinfunction "2_8") (pintype "passive"))
      (node (ref "U1") (pin "36") (pinfunction "DDR3_D12_36") (pintype "bidirectional"))
    )
    (net (code "150") (name "Net-(RN3A-2)") (class "Default")
      (node (ref "RN3") (pin "5") (pinfunction "2_5") (pintype "passive"))
      (node (ref "U1") (pin "44") (pinfunction "DDR3_D5_44") (pintype "bidirectional"))
    )
    (net (code "151") (name "Net-(RN3B-2)") (class "Default")
      (node (ref "RN3") (pin "6") (pinfunction "2_6") (pintype "passive"))
      (node (ref "U1") (pin "42") (pinfunction "DDR3_D7_42") (pintype "bidirectional"))
    )
    (net (code "152") (name "Net-(RN3C-2)") (class "Default")
      (node (ref "RN3") (pin "7") (pinfunction "2_7") (pintype "passive"))
      (node (ref "U1") (pin "41") (pinfunction "DDR3_D3_41") (pintype "bidirectional"))
    )
    (net (code "153") (name "Net-(RN3D-2)") (class "Default")
      (node (ref "RN3") (pin "8") (pinfunction "2_8") (pintype "passive"))
      (node (ref "U1") (pin "40") (pinfunction "DDR3_D1_40") (pintype "bidirectional"))
    )
    (net (code "154") (name "Net-(RN4A-2)") (class "Default")
      (node (ref "RN4") (pin "5") (pinfunction "2_5") (pintype "passive"))
      (node (ref "U1") (pin "27") (pinfunction "DDR3_D15_27") (pintype "bidirectional"))
    )
    (net (code "155") (name "Net-(RN4B-2)") (class "Default")
      (node (ref "RN4") (pin "6") (pinfunction "2_6") (pintype "passive"))
      (node (ref "U1") (pin "26") (pinfunction "DDR3_D13_26") (pintype "bidirectional"))
    )
    (net (code "156") (name "Net-(RN4C-2)") (class "Default")
      (node (ref "RN4") (pin "7") (pinfunction "2_7") (pintype "passive"))
      (node (ref "U1") (pin "25") (pinfunction "DDR3_D9_25") (pintype "bidirectional"))
    )
    (net (code "157") (name "Net-(RN4D-2)") (class "Default")
      (node (ref "RN4") (pin "8") (pinfunction "2_8") (pintype "passive"))
      (node (ref "U1") (pin "24") (pinfunction "DDR3_D11_24") (pintype "bidirectional"))
    )
    (net (code "158") (name "Net-(RN5A-2)") (class "Default")
      (node (ref "RN5") (pin "5") (pinfunction "2_5") (pintype "passive"))
      (node (ref "U1") (pin "64") (pinfunction "DDR3_A0_64") (pintype "bidirectional"))
    )
    (net (code "159") (name "Net-(RN5B-2)") (class "Default")
      (node (ref "RN5") (pin "6") (pinfunction "2_6") (pintype "passive"))
      (node (ref "U1") (pin "63") (pinfunction "DDR3_BA0_63") (pintype "bidirectional"))
    )
    (net (code "160") (name "Net-(RN5C-2)") (class "Default")
      (node (ref "RN5") (pin "7") (pinfunction "2_7") (pintype "passive"))
      (node (ref "U1") (pin "61") (pinfunction "DDR3_BA2_61") (pintype "bidirectional"))
    )
    (net (code "161") (name "Net-(RN5D-2)") (class "Default")
      (node (ref "RN5") (pin "8") (pinfunction "2_8") (pintype "passive"))
      (node (ref "U1") (pin "60") (pinfunction "DDR3_WE_60") (pintype "bidirectional"))
    )
    (net (code "162") (name "Net-(RN6A-2)") (class "Default")
      (node (ref "RN6") (pin "5") (pinfunction "2_5") (pintype "passive"))
      (node (ref "U1") (pin "55") (pinfunction "DDR3_A8_55") (pintype "bidirectional"))
    )
    (net (code "163") (name "Net-(RN6B-2)") (class "Default")
      (node (ref "RN6") (pin "6") (pinfunction "2_6") (pintype "passive"))
      (node (ref "U1") (pin "54") (pinfunction "DDR3_A6_54") (pintype "bidirectional"))
    )
    (net (code "164") (name "Net-(RN6C-2)") (class "Default")
      (node (ref "RN6") (pin "7") (pinfunction "2_7") (pintype "passive"))
      (node (ref "U1") (pin "52") (pinfunction "DDR3_A1_52") (pintype "bidirectional"))
    )
    (net (code "165") (name "Net-(RN6D-2)") (class "Default")
      (node (ref "RN6") (pin "8") (pinfunction "2_8") (pintype "passive"))
      (node (ref "U1") (pin "51") (pinfunction "DDR3_A4_51") (pintype "bidirectional"))
    )
    (net (code "166") (name "Net-(RN7A-2)") (class "Default")
      (node (ref "RN7") (pin "5") (pinfunction "2_5") (pintype "passive"))
      (node (ref "U1") (pin "50") (pinfunction "DDR3_A12_50") (pintype "bidirectional"))
    )
    (net (code "167") (name "Net-(RN7B-2)") (class "Default")
      (node (ref "RN7") (pin "6") (pinfunction "2_6") (pintype "passive"))
      (node (ref "U1") (pin "49") (pinfunction "DDR3_BA1_49") (pintype "bidirectional"))
    )
    (net (code "168") (name "Net-(RN7C-2)") (class "Default")
      (node (ref "RN7") (pin "7") (pinfunction "2_7") (pintype "passive"))
      (node (ref "U1") (pin "48") (pinfunction "DDR3_A10_48") (pintype "bidirectional"))
    )
    (net (code "169") (name "Net-(RN7D-2)") (class "Default")
      (node (ref "RN7") (pin "8") (pinfunction "2_8") (pintype "passive"))
      (node (ref "U1") (pin "47") (pinfunction "DDR3_CKE_47") (pintype "bidirectional"))
    )
    (net (code "170") (name "Net-(RN8A-2)") (class "Default")
      (node (ref "RN8") (pin "5") (pinfunction "2_5") (pintype "passive"))
      (node (ref "U1") (pin "68") (pinfunction "DDR3_A13_68") (pintype "bidirectional"))
    )
    (net (code "171") (name "Net-(RN8B-2)") (class "Default")
      (node (ref "RN8") (pin "6") (pinfunction "2_6") (pintype "passive"))
      (node (ref "U1") (pin "67") (pinfunction "DDR3_A5_67") (pintype "bidirectional"))
    )
    (net (code "172") (name "Net-(RN8C-2)") (class "Default")
      (node (ref "RN8") (pin "7") (pinfunction "2_7") (pintype "passive"))
      (node (ref "U1") (pin "66") (pinfunction "DDR3_A2_66") (pintype "bidirectional"))
    )
    (net (code "173") (name "Net-(RN8D-2)") (class "Default")
      (node (ref "RN8") (pin "8") (pinfunction "2_8") (pintype "passive"))
      (node (ref "U1") (pin "65") (pinfunction "DDR3_A3_65") (pintype "bidirectional"))
    )
    (net (code "174") (name "Net-(RN9A-2)") (class "Default")
      (node (ref "RN9") (pin "5") (pinfunction "2_5") (pintype "passive"))
      (node (ref "U1") (pin "59") (pinfunction "DDR3_CAS_59") (pintype "bidirectional"))
    )
    (net (code "175") (name "Net-(RN9B-2)") (class "Default")
      (node (ref "RN9") (pin "6") (pinfunction "2_6") (pintype "passive"))
      (node (ref "U1") (pin "58") (pinfunction "DDR3_RAS_58") (pintype "bidirectional"))
    )
    (net (code "176") (name "Net-(RN9C-2)") (class "Default")
      (node (ref "RN9") (pin "7") (pinfunction "2_7") (pintype "passive"))
      (node (ref "U1") (pin "57") (pinfunction "DDR3_A14_57") (pintype "bidirectional"))
    )
    (net (code "177") (name "Net-(RN9D-2)") (class "Default")
      (node (ref "RN9") (pin "8") (pinfunction "2_8") (pintype "passive"))
      (node (ref "U1") (pin "56") (pinfunction "DDR3_A11_56") (pintype "bidirectional"))
    )
    (net (code "178") (name "Net-(RN10A-2)") (class "Default")
      (node (ref "RN10") (pin "5") (pinfunction "2_5") (pintype "passive"))
      (node (ref "U1") (pin "72") (pinfunction "DDR3_ODT_72") (pintype "bidirectional"))
    )
    (net (code "179") (name "Net-(RN10B-2)") (class "Default")
      (node (ref "RN10") (pin "6") (pinfunction "2_6") (pintype "passive"))
      (node (ref "U1") (pin "71") (pinfunction "DDR3_A7_71") (pintype "bidirectional"))
    )
    (net (code "180") (name "Net-(RN10C-2)") (class "Default")
      (node (ref "RN10") (pin "7") (pinfunction "2_7") (pintype "passive"))
      (node (ref "U1") (pin "70") (pinfunction "DDR3_RST_70") (pintype "bidirectional"))
    )
    (net (code "181") (name "Net-(RN10D-2)") (class "Default")
      (node (ref "RN10") (pin "8") (pinfunction "2_8") (pintype "passive"))
      (node (ref "U1") (pin "69") (pinfunction "DDR3_A9_69") (pintype "bidirectional"))
    )
    (net (code "182") (name "Net-(RN11A-2)") (class "Default")
      (node (ref "RN11") (pin "5") (pinfunction "2_5") (pintype "passive"))
      (node (ref "U1") (pin "34") (pinfunction "DDR3_DQS1-_34") (pintype "bidirectional"))
    )
    (net (code "183") (name "Net-(RN11B-2)") (class "Default")
      (node (ref "RN11") (pin "6") (pinfunction "2_6") (pintype "passive"))
      (node (ref "U1") (pin "33") (pinfunction "DDR3_DQS1+_33") (pintype "bidirectional"))
    )
    (net (code "184") (name "Net-(RN11C-2)") (class "Default")
      (node (ref "RN11") (pin "7") (pinfunction "2_7") (pintype "passive"))
      (node (ref "U1") (pin "32") (pinfunction "DDR3_DQS0-_32") (pintype "bidirectional"))
    )
    (net (code "185") (name "Net-(RN11D-2)") (class "Default")
      (node (ref "RN11") (pin "8") (pinfunction "2_8") (pintype "passive"))
      (node (ref "U1") (pin "31") (pinfunction "DDR3_DQS0+_31") (pintype "bidirectional"))
    )
    (net (code "186") (name "Net-(RN12B-1)") (class "Default")
      (node (ref "C5") (pin "1") (pinfunction "1_1") (pintype "passive"))
      (node (ref "RN12") (pin "2") (pinfunction "1_2") (pintype "passive"))
    )
    (net (code "187") (name "Net-(RN12C-1)") (class "Default")
      (node (ref "C6") (pin "1") (pinfunction "1_1") (pintype "passive"))
      (node (ref "RN12") (pin "3") (pinfunction "1_3") (pintype "passive"))
    )
    (net (code "188") (name "Net-(RN13B-1)") (class "Default")
      (node (ref "RN13") (pin "2") (pinfunction "1_2") (pintype "passive"))
      (node (ref "U12") (pin "14") (pinfunction "DP1_14") (pintype "bidirectional"))
      (node (ref "U19") (pin "1") (pinfunction "D0+_1") (pintype "bidirectional"))
    )
    (net (code "189") (name "Net-(RN13C-1)") (class "Default")
      (node (ref "RN13") (pin "3") (pinfunction "1_3") (pintype "passive"))
      (node (ref "U12") (pin "17") (pinfunction "DM2_17") (pintype "bidirectional"))
      (node (ref "U19") (pin "4") (pinfunction "D1-_4") (pintype "bidirectional"))
    )
    (net (code "190") (name "Net-(RN13D-1)") (class "Default")
      (node (ref "RN13") (pin "4") (pinfunction "1_4") (pintype "passive"))
      (node (ref "U12") (pin "18") (pinfunction "DP2_18") (pintype "bidirectional"))
      (node (ref "U19") (pin "3") (pinfunction "D1+_3") (pintype "bidirectional"))
    )
    (net (code "191") (name "Net-(RN14B-1)") (class "Default")
      (node (ref "RN14") (pin "2") (pinfunction "1_2") (pintype "passive"))
      (node (ref "U12") (pin "22") (pinfunction "DP3_22") (pintype "bidirectional"))
      (node (ref "U20") (pin "1") (pinfunction "D0+_1") (pintype "bidirectional"))
    )
    (net (code "192") (name "Net-(RN14C-1)") (class "Default")
      (node (ref "RN14") (pin "3") (pinfunction "1_3") (pintype "passive"))
      (node (ref "U12") (pin "26") (pinfunction "DM4_26") (pintype "bidirectional"))
      (node (ref "U20") (pin "4") (pinfunction "D1-_4") (pintype "bidirectional"))
    )
    (net (code "193") (name "Net-(RN14D-1)") (class "Default")
      (node (ref "RN14") (pin "4") (pinfunction "1_4") (pintype "passive"))
      (node (ref "U12") (pin "27") (pinfunction "DP4_27") (pintype "bidirectional"))
      (node (ref "U20") (pin "3") (pinfunction "D1+_3") (pintype "bidirectional"))
    )
    (net (code "194") (name "Net-(RN15B-1)") (class "Default")
      (node (ref "RN15") (pin "2") (pinfunction "1_2") (pintype "passive"))
      (node (ref "U12") (pin "31") (pinfunction "DP5_31") (pintype "bidirectional"))
      (node (ref "U21") (pin "1") (pinfunction "D0+_1") (pintype "bidirectional"))
    )
    (net (code "195") (name "Net-(RN15C-1)") (class "Default")
      (node (ref "RN15") (pin "3") (pinfunction "1_3") (pintype "passive"))
      (node (ref "U12") (pin "34") (pinfunction "DM6_34") (pintype "bidirectional"))
      (node (ref "U21") (pin "4") (pinfunction "D1-_4") (pintype "bidirectional"))
    )
    (net (code "196") (name "Net-(RN15D-1)") (class "Default")
      (node (ref "RN15") (pin "4") (pinfunction "1_4") (pintype "passive"))
      (node (ref "U12") (pin "35") (pinfunction "DP6_35") (pintype "bidirectional"))
      (node (ref "U21") (pin "3") (pinfunction "D1+_3") (pintype "bidirectional"))
    )
    (net (code "197") (name "Net-(U$4-ZQ)") (class "Default")
      (node (ref "R43") (pin "2") (pinfunction "2_2") (pintype "passive"))
      (node (ref "U$4") (pin "H8") (pinfunction "ZQ_H8") (pintype "bidirectional"))
    )
    (net (code "198") (name "Net-(U$5-ZQ)") (class "Default")
      (node (ref "R50") (pin "2") (pinfunction "2_2") (pintype "passive"))
      (node (ref "U$5") (pin "H8") (pinfunction "ZQ_H8") (pintype "bidirectional"))
    )
    (net (code "199") (name "Net-(U1A-LRADC)") (class "Default")
      (node (ref "C1") (pin "1") (pinfunction "1_1") (pintype "passive"))
      (node (ref "R2") (pin "1") (pinfunction "1_1") (pintype "passive"))
      (node (ref "R7") (pin "1") (pinfunction "1_1") (pintype "passive"))
      (node (ref "U1") (pin "86") (pinfunction "LRADC_86") (pintype "bidirectional"))
    )
    (net (code "200") (name "Net-(U1B-HPBP)") (class "Default")
      (node (ref "C7") (pin "1") (pinfunction "1_1") (pintype "passive"))
      (node (ref "C8") (pin "1") (pinfunction "1_1") (pintype "passive"))
      (node (ref "U1") (pin "75") (pinfunction "HPBP_75") (pintype "bidirectional"))
    )
    (net (code "201") (name "Net-(U1D-DDR3_CK+)") (class "Default")
      (node (ref "R46") (pin "2") (pinfunction "2_2") (pintype "passive"))
      (node (ref "U1") (pin "45") (pinfunction "DDR3_CK+_45") (pintype "bidirectional"))
    )
    (net (code "202") (name "Net-(U1D-DDR3_CK-)") (class "Default")
      (node (ref "R47") (pin "2") (pinfunction "2_2") (pintype "passive"))
      (node (ref "U1") (pin "46") (pinfunction "DDR3_CK-_46") (pintype "bidirectional"))
    )
    (net (code "203") (name "Net-(U1D-DDR3_DM0)") (class "Default")
      (node (ref "R48") (pin "2") (pinfunction "2_2") (pintype "passive"))
      (node (ref "U1") (pin "29") (pinfunction "DDR3_DM0_29") (pintype "bidirectional"))
    )
    (net (code "204") (name "Net-(U1D-DDR3_DM1)") (class "Default")
      (node (ref "R49") (pin "2") (pinfunction "2_2") (pintype "passive"))
      (node (ref "U1") (pin "28") (pinfunction "DDR3_DM1_28") (pintype "bidirectional"))
    )
    (net (code "205") (name "Net-(U1F-TPX1)") (class "Default")
      (node (ref "JP3") (pin "2") (pinfunction "2_2") (pintype "passive"))
      (node (ref "U1") (pin "89") (pinfunction "TPX1_89") (pintype "bidirectional"))
    )
    (net (code "206") (name "Net-(U1F-TPX2)") (class "Default")
      (node (ref "JP3") (pin "4") (pinfunction "4_4") (pintype "passive"))
      (node (ref "U1") (pin "87") (pinfunction "TPX2_87") (pintype "bidirectional"))
    )
    (net (code "207") (name "Net-(U1F-TPY1)") (class "Default")
      (node (ref "JP3") (pin "1") (pinfunction "1_1") (pintype "passive"))
      (node (ref "U1") (pin "90") (pinfunction "TPY1_90") (pintype "bidirectional"))
    )
    (net (code "208") (name "Net-(U1F-TPY2)") (class "Default")
      (node (ref "JP3") (pin "3") (pinfunction "3_3") (pintype "passive"))
      (node (ref "U1") (pin "88") (pinfunction "TPY2_88") (pintype "bidirectional"))
    )
    (net (code "209") (name "Net-(U1H-LCD_CLK)") (class "Default")
      (node (ref "U1") (pin "129") (pinfunction "LCD_CLK_129") (pintype "bidirectional"))
      (node (ref "U9") (pin "57") (pinfunction "IDCK+_57") (pintype "bidirectional"))
    )
    (net (code "210") (name "Net-(U1H-LCD_D2)") (class "Default")
      (node (ref "U1") (pin "148") (pinfunction "LCD_D2_148") (pintype "bidirectional"))
      (node (ref "U9") (pin "61") (pinfunction "D2_61") (pintype "bidirectional"))
    )
    (net (code "211") (name "Net-(U1H-LCD_D3)") (class "Default")
      (node (ref "U1") (pin "147") (pinfunction "LCD_D3_147") (pintype "bidirectional"))
      (node (ref "U9") (pin "60") (pinfunction "D3_60") (pintype "bidirectional"))
    )
    (net (code "212") (name "Net-(U1H-LCD_D4)") (class "Default")
      (node (ref "U1") (pin "146") (pinfunction "LCD_D4_146") (pintype "bidirectional"))
      (node (ref "U9") (pin "59") (pinfunction "D4_59") (pintype "bidirectional"))
    )
    (net (code "213") (name "Net-(U1H-LCD_D5)") (class "Default")
      (node (ref "U1") (pin "145") (pinfunction "LCD_D5_145") (pintype "bidirectional"))
      (node (ref "U9") (pin "58") (pinfunction "D5_58") (pintype "bidirectional"))
    )
    (net (code "214") (name "Net-(U1H-LCD_D6)") (class "Default")
      (node (ref "U1") (pin "144") (pinfunction "LCD_D6_144") (pintype "bidirectional"))
      (node (ref "U9") (pin "55") (pinfunction "D6_55") (pintype "bidirectional"))
    )
    (net (code "215") (name "Net-(U1H-LCD_D7)") (class "Default")
      (node (ref "U1") (pin "143") (pinfunction "LCD_D7_143") (pintype "bidirectional"))
      (node (ref "U9") (pin "54") (pinfunction "D7_54") (pintype "bidirectional"))
    )
    (net (code "216") (name "Net-(U1H-LCD_D10)") (class "Default")
      (node (ref "U1") (pin "141") (pinfunction "LCD_D10_141") (pintype "bidirectional"))
      (node (ref "U9") (pin "51") (pinfunction "D10_51") (pintype "bidirectional"))
    )
    (net (code "217") (name "Net-(U1H-LCD_D11)") (class "Default")
      (node (ref "U1") (pin "140") (pinfunction "LCD_D11_140") (pintype "bidirectional"))
      (node (ref "U9") (pin "50") (pinfunction "D11_50") (pintype "bidirectional"))
    )
    (net (code "218") (name "Net-(U1H-LCD_D12)") (class "Default")
      (node (ref "U1") (pin "139") (pinfunction "LCD_D12_139") (pintype "bidirectional"))
      (node (ref "U9") (pin "47") (pinfunction "D12_47") (pintype "bidirectional"))
    )
    (net (code "219") (name "Net-(U1H-LCD_D13)") (class "Default")
      (node (ref "U1") (pin "138") (pinfunction "LCD_D13_138") (pintype "bidirectional"))
      (node (ref "U9") (pin "46") (pinfunction "D13_46") (pintype "bidirectional"))
    )
    (net (code "220") (name "Net-(U1H-LCD_D14)") (class "Default")
      (node (ref "U1") (pin "137") (pinfunction "LCD_D14_137") (pintype "bidirectional"))
      (node (ref "U9") (pin "45") (pinfunction "D14_45") (pintype "bidirectional"))
    )
    (net (code "221") (name "Net-(U1H-LCD_D15)") (class "Default")
      (node (ref "U1") (pin "136") (pinfunction "LCD_D15_136") (pintype "bidirectional"))
      (node (ref "U9") (pin "44") (pinfunction "D15_44") (pintype "bidirectional"))
    )
    (net (code "222") (name "Net-(U1H-LCD_D18)") (class "Default")
      (node (ref "U1") (pin "135") (pinfunction "LCD_D18_135") (pintype "bidirectional"))
      (node (ref "U9") (pin "41") (pinfunction "D18_41") (pintype "bidirectional"))
    )
    (net (code "223") (name "Net-(U1H-LCD_D19)") (class "Default")
      (node (ref "U1") (pin "134") (pinfunction "LCD_D19_134") (pintype "bidirectional"))
      (node (ref "U9") (pin "40") (pinfunction "D19_40") (pintype "bidirectional"))
    )
    (net (code "224") (name "Net-(U1H-LCD_D20)") (class "Default")
      (node (ref "U1") (pin "133") (pinfunction "LCD_D20_133") (pintype "bidirectional"))
      (node (ref "U9") (pin "39") (pinfunction "D20_39") (pintype "bidirectional"))
    )
    (net (code "225") (name "Net-(U1H-LCD_D21)") (class "Default")
      (node (ref "U1") (pin "132") (pinfunction "LCD_D21_132") (pintype "bidirectional"))
      (node (ref "U9") (pin "38") (pinfunction "D21_38") (pintype "bidirectional"))
    )
    (net (code "226") (name "Net-(U1H-LCD_D22)") (class "Default")
      (node (ref "U1") (pin "131") (pinfunction "LCD_D22_131") (pintype "bidirectional"))
      (node (ref "U9") (pin "37") (pinfunction "D22_37") (pintype "bidirectional"))
    )
    (net (code "227") (name "Net-(U1H-LCD_D23)") (class "Default")
      (node (ref "U1") (pin "130") (pinfunction "LCD_D23_130") (pintype "bidirectional"))
      (node (ref "U9") (pin "36") (pinfunction "D23_36") (pintype "bidirectional"))
    )
    (net (code "228") (name "Net-(U1H-LCD_DE)") (class "Default")
      (node (ref "U1") (pin "128") (pinfunction "LCD_DE_128") (pintype "bidirectional"))
      (node (ref "U9") (pin "2") (pinfunction "DE_2") (pintype "bidirectional"))
    )
    (net (code "229") (name "Net-(U1H-LCD_HSYNC)") (class "Default")
      (node (ref "U1") (pin "127") (pinfunction "LCD_HSYNC_127") (pintype "bidirectional"))
      (node (ref "U9") (pin "4") (pinfunction "HSYNC_4") (pintype "bidirectional"))
    )
    (net (code "230") (name "Net-(U1H-LCD_VSYNC)") (class "Default")
      (node (ref "U1") (pin "126") (pinfunction "LCD_VSYNC_126") (pintype "bidirectional"))
      (node (ref "U9") (pin "5") (pinfunction "VSYNC_5") (pintype "bidirectional"))
    )
    (net (code "231") (name "Net-(U1K-VRA1)") (class "Default")
      (node (ref "C49") (pin "1") (pinfunction "1_1") (pintype "passive"))
      (node (ref "U1") (pin "83") (pinfunction "VRA1_83") (pintype "bidirectional"))
    )
    (net (code "232") (name "Net-(U1K-VRA2)") (class "Default")
      (node (ref "C47") (pin "1") (pinfunction "1_1") (pintype "passive"))
      (node (ref "C48") (pin "1") (pinfunction "1_1") (pintype "passive"))
      (node (ref "R30") (pin "2") (pinfunction "2_2") (pintype "passive"))
      (node (ref "U1") (pin "82") (pinfunction "VRA2_82") (pintype "bidirectional"))
    )
    (net (code "233") (name "Net-(U1K-VRP)") (class "Default")
      (node (ref "C53") (pin "1") (pinfunction "1_1") (pintype "passive"))
      (node (ref "C54") (pin "1") (pinfunction "1_1") (pintype "passive"))
      (node (ref "U1") (pin "80") (pinfunction "VRP_80") (pintype "bidirectional"))
    )
    (net (code "234") (name "Net-(U1L-X24MIN)") (class "Default")
      (node (ref "C15") (pin "1") (pinfunction "1_1") (pintype "passive"))
      (node (ref "U1") (pin "92") (pinfunction "X24MIN_92") (pintype "bidirectional"))
      (node (ref "Y1") (pin "3") (pinfunction "2_3") (pintype "bidirectional"))
    )
    (net (code "235") (name "Net-(U1L-X24MOUT)") (class "Default")
      (node (ref "C14") (pin "1") (pinfunction "1_1") (pintype "passive"))
      (node (ref "U1") (pin "91") (pinfunction "X24MOUT_91") (pintype "bidirectional"))
      (node (ref "Y1") (pin "1") (pinfunction "1_1") (pintype "bidirectional"))
    )
    (net (code "236") (name "Net-(U1M-D1+)") (class "Default")
      (node (ref "R67") (pin "1") (pinfunction "1_1") (pintype "passive"))
      (node (ref "U1") (pin "96") (pinfunction "D1+_96") (pintype "bidirectional"))
    )
    (net (code "237") (name "Net-(U1M-D1-)") (class "Default")
      (node (ref "R68") (pin "1") (pinfunction "1_1") (pintype "passive"))
      (node (ref "U1") (pin "95") (pinfunction "D1-_95") (pintype "bidirectional"))
    )
    (net (code "238") (name "Net-(U1N-D0+)") (class "Default")
      (node (ref "R65") (pin "1") (pinfunction "1_1") (pintype "passive"))
      (node (ref "U1") (pin "94") (pinfunction "D0+_94") (pintype "bidirectional"))
    )
    (net (code "239") (name "Net-(U1N-D0-)") (class "Default")
      (node (ref "R66") (pin "1") (pinfunction "1_1") (pintype "passive"))
      (node (ref "U1") (pin "93") (pinfunction "D0-_93") (pintype "bidirectional"))
    )
    (net (code "240") (name "Net-(U2-BIAS)") (class "Default")
      (node (ref "R23") (pin "2") (pinfunction "2_2") (pintype "passive"))
      (node (ref "U2") (pin "23") (pinfunction "BIAS_23") (pintype "bidirectional"))
    )
    (net (code "241") (name "Net-(U2-CHGLED)") (class "Default")
      (node (ref "R20") (pin "1") (pinfunction "1_1") (pintype "passive"))
      (node (ref "U2") (pin "36") (pinfunction "CHGLED_36") (pintype "bidirectional"))
    )
    (net (code "242") (name "Net-(U2-LX1)") (class "Default")
      (node (ref "L1") (pin "1") (pinfunction "1_1") (pintype "passive"))
      (node (ref "U2") (pin "45") (pinfunction "LX1_45") (pintype "bidirectional"))
    )
    (net (code "243") (name "Net-(U2-LX2)") (class "Default")
      (node (ref "L2") (pin "1") (pinfunction "1_1") (pintype "passive"))
      (node (ref "U2") (pin "8") (pinfunction "LX2_8") (pintype "bidirectional"))
    )
    (net (code "244") (name "Net-(U2-LX3)") (class "Default")
      (node (ref "L3") (pin "1") (pinfunction "1_1") (pintype "passive"))
      (node (ref "U2") (pin "15") (pinfunction "LX3_15") (pintype "bidirectional"))
    )
    (net (code "245") (name "Net-(U2-TS)") (class "Default")
      (node (ref "R22") (pin "2") (pinfunction "2_2") (pintype "passive"))
      (node (ref "U2") (pin "37") (pinfunction "TS_37") (pintype "bidirectional"))
    )
    (net (code "246") (name "Net-(U2-VREF)") (class "Default")
      (node (ref "C25") (pin "1") (pinfunction "1_1") (pintype "passive"))
      (node (ref "U2") (pin "24") (pinfunction "VREF_24") (pintype "bidirectional"))
    )
    (net (code "247") (name "Net-(U2-~{OE})") (class "Default")
      (node (ref "R18") (pin "2") (pinfunction "2_2") (pintype "passive"))
      (node (ref "S6") (pin "P$2") (pinfunction "P$2_P$2") (pintype "bidirectional"))
      (node (ref "U2") (pin "4") (pinfunction "~{OE}_4") (pintype "bidirectional"))
    )
    (net (code "248") (name "Net-(U5-DITH)") (class "Default")
      (node (ref "JP2") (pin "2") (pinfunction "2_2") (pintype "passive"))
      (node (ref "U5") (pin "7") (pinfunction "DITH_7") (pintype "bidirectional"))
    )
    (net (code "249") (name "Net-(U5-FB)") (class "Default")
      (node (ref "R31") (pin "1") (pinfunction "1_1") (pintype "passive"))
      (node (ref "R32") (pin "2") (pinfunction "2_2") (pintype "passive"))
      (node (ref "U5") (pin "1") (pinfunction "FB_1") (pintype "bidirectional"))
    )
    (net (code "250") (name "Net-(U6-COMP)") (class "Default")
      (node (ref "R34") (pin "2") (pinfunction "2_2") (pintype "passive"))
      (node (ref "U6") (pin "10") (pinfunction "COMP_10") (pintype "bidirectional"))
    )
    (net (code "251") (name "Net-(U6-FB)") (class "Default")
      (node (ref "C70") (pin "1") (pinfunction "1_1") (pintype "passive"))
      (node (ref "R35") (pin "1") (pinfunction "1_1") (pintype "passive"))
      (node (ref "R36") (pin "2") (pinfunction "2_2") (pintype "passive"))
      (node (ref "U6") (pin "9") (pinfunction "FB_9") (pintype "bidirectional"))
    )
    (net (code "252") (name "Net-(U6-SHDN{slash}RT)") (class "Default")
      (node (ref "R33") (pin "2") (pinfunction "2_2") (pintype "passive"))
      (node (ref "U6") (pin "1") (pinfunction "SHDN/RT_1") (pintype "bidirectional"))
    )
    (net (code "253") (name "Net-(U7-COMP)") (class "Default")
      (node (ref "R38") (pin "2") (pinfunction "2_2") (pintype "passive"))
      (node (ref "U7") (pin "10") (pinfunction "COMP_10") (pintype "bidirectional"))
    )
    (net (code "254") (name "Net-(U7-FB)") (class "Default")
      (node (ref "C69") (pin "1") (pinfunction "1_1") (pintype "passive"))
      (node (ref "R39") (pin "1") (pinfunction "1_1") (pintype "passive"))
      (node (ref "R40") (pin "2") (pinfunction "2_2") (pintype "passive"))
      (node (ref "U7") (pin "9") (pinfunction "FB_9") (pintype "bidirectional"))
    )
    (net (code "255") (name "Net-(U7-SHDN{slash}RT)") (class "Default")
      (node (ref "R37") (pin "2") (pinfunction "2_2") (pintype "passive"))
      (node (ref "U7") (pin "1") (pinfunction "SHDN/RT_1") (pintype "bidirectional"))
    )
    (net (code "256") (name "Net-(U8-EN)") (class "Default")
      (node (ref "C107") (pin "+") (pinfunction "+_+") (pintype "passive"))
      (node (ref "C79") (pin "1") (pinfunction "1_1") (pintype "passive"))
      (node (ref "C80") (pin "1") (pinfunction "1_1") (pintype "passive"))
      (node (ref "J4") (pin "PWR") (pinfunction "PWR_PWR") (pintype "bidirectional"))
      (node (ref "U8") (pin "1") (pinfunction "VIN_A_1") (pintype "bidirectional"))
      (node (ref "U8") (pin "2") (pinfunction "EN_2") (pintype "bidirectional"))
      (node (ref "U8") (pin "6") (pinfunction "VIN_SW_6") (pintype "bidirectional"))
    )
    (net (code "257") (name "Net-(U8-FB)") (class "Default")
      (node (ref "R41") (pin "1") (pinfunction "1_1") (pintype "passive"))
      (node (ref "R42") (pin "2") (pinfunction "2_2") (pintype "passive"))
      (node (ref "U8") (pin "3") (pinfunction "FB_3") (pintype "bidirectional"))
    )
    (net (code "258") (name "Net-(U8-SW)") (class "Default")
      (node (ref "L8") (pin "1") (pinfunction "1_1") (pintype "passive"))
      (node (ref "U8") (pin "7") (pinfunction "SW_7") (pintype "bidirectional"))
    )
    (net (code "259") (name "Net-(U9A-EDGE{slash}HTPLG)") (class "Default")
      (node (ref "R11") (pin "2") (pinfunction "2_2") (pintype "passive"))
      (node (ref "U9") (pin "9") (pinfunction "EDGE/HTPLG_9") (pintype "bidirectional"))
    )
    (net (code "260") (name "Net-(U9A-ISEL{slash}~{RST})") (class "Default")
      (node (ref "R10") (pin "1") (pinfunction "1_1") (pintype "passive"))
      (node (ref "U9") (pin "13") (pinfunction "ISEL/~{RST}_13") (pintype "bidirectional"))
    )
    (net (code "261") (name "Net-(U9A-TFADJ)") (class "Default")
      (node (ref "R9") (pin "1") (pinfunction "1_1") (pintype "passive"))
      (node (ref "U9") (pin "19") (pinfunction "TFADJ_19") (pintype "bidirectional"))
    )
    (net (code "262") (name "Net-(U10-OSC1)") (class "Default")
      (node (ref "C109") (pin "1") (pinfunction "1_1") (pintype "passive"))
      (node (ref "U10") (pin "19") (pinfunction "OSC1_19") (pintype "bidirectional"))
      (node (ref "Y2") (pin "3") (pinfunction "2_3") (pintype "bidirectional"))
    )
    (net (code "263") (name "Net-(U10-OSC2)") (class "Default")
      (node (ref "C108") (pin "1") (pinfunction "1_1") (pintype "passive"))
      (node (ref "U10") (pin "20") (pinfunction "OSC2_20") (pintype "bidirectional"))
      (node (ref "Y2") (pin "1") (pinfunction "1_1") (pintype "bidirectional"))
    )
    (net (code "264") (name "Net-(U10-RBIAS)") (class "Default")
      (node (ref "R52") (pin "2") (pinfunction "2_2") (pintype "passive"))
      (node (ref "U10") (pin "10") (pinfunction "RBIAS_10") (pintype "bidirectional"))
    )
    (net (code "265") (name "Net-(U10-VCAP)") (class "Default")
      (node (ref "C110") (pin "1") (pinfunction "1_1") (pintype "passive"))
      (node (ref "U10") (pin "25") (pinfunction "VCAP_25") (pintype "bidirectional"))
    )
    (net (code "266") (name "Net-(U10-~{RESET})") (class "Default")
      (node (ref "R53") (pin "1") (pinfunction "1_1") (pintype "passive"))
      (node (ref "U10") (pin "6") (pinfunction "~{RESET}_6") (pintype "bidirectional"))
    )
    (net (code "267") (name "Net-(U11-ALE)") (class "Default")
      (node (ref "U1") (pin "7") (pinfunction "~{ALE}/SPI0_MISO_7") (pintype "bidirectional"))
      (node (ref "U11") (pin "17") (pinfunction "ALE_17") (pintype "bidirectional"))
    )
    (net (code "268") (name "Net-(U11-CLE)") (class "Default")
      (node (ref "U1") (pin "6") (pinfunction "~{CLE}/SPI0_CLK_6") (pintype "bidirectional"))
      (node (ref "U11") (pin "16") (pinfunction "CLE_16") (pintype "bidirectional"))
    )
    (net (code "269") (name "Net-(U11-D0)") (class "Default")
      (node (ref "U1") (pin "118") (pinfunction "~{DQ0}/SDC2_D0_118") (pintype "bidirectional"))
      (node (ref "U11") (pin "29") (pinfunction "D0_29") (pintype "bidirectional"))
    )
    (net (code "270") (name "Net-(U11-D1)") (class "Default")
      (node (ref "U1") (pin "119") (pinfunction "~{DQ1}/SDC2_D1_119") (pintype "bidirectional"))
      (node (ref "U11") (pin "30") (pinfunction "D1_30") (pintype "bidirectional"))
    )
    (net (code "271") (name "Net-(U11-D2)") (class "Default")
      (node (ref "U1") (pin "120") (pinfunction "~{DQ2}/SDC2_D2_120") (pintype "bidirectional"))
      (node (ref "U11") (pin "31") (pinfunction "D2_31") (pintype "bidirectional"))
    )
    (net (code "272") (name "Net-(U11-D3)") (class "Default")
      (node (ref "U1") (pin "121") (pinfunction "~{DQ3}/SDC2_D3_121") (pintype "bidirectional"))
      (node (ref "U11") (pin "32") (pinfunction "D3_32") (pintype "bidirectional"))
    )
    (net (code "273") (name "Net-(U11-D4)") (class "Default")
      (node (ref "U1") (pin "122") (pinfunction "~{DQ4}/SDC2_D4_122") (pintype "bidirectional"))
      (node (ref "U11") (pin "41") (pinfunction "D4_41") (pintype "bidirectional"))
    )
    (net (code "274") (name "Net-(U11-D5)") (class "Default")
      (node (ref "U1") (pin "123") (pinfunction "~{DQ5}/SDC2_D5_123") (pintype "bidirectional"))
      (node (ref "U11") (pin "42") (pinfunction "D5_42") (pintype "bidirectional"))
    )
    (net (code "275") (name "Net-(U11-D6)") (class "Default")
      (node (ref "U1") (pin "124") (pinfunction "~{DQ6}/SDC2_D6_124") (pintype "bidirectional"))
      (node (ref "U11") (pin "43") (pinfunction "D6_43") (pintype "bidirectional"))
    )
    (net (code "276") (name "Net-(U11-D7)") (class "Default")
      (node (ref "U1") (pin "125") (pinfunction "~{DQ7}/SDC2_D7_125") (pintype "bidirectional"))
      (node (ref "U11") (pin "44") (pinfunction "D7_44") (pintype "bidirectional"))
    )
    (net (code "277") (name "Net-(U11-R{slash}~{B})") (class "Default")
      (node (ref "R60") (pin "1") (pinfunction "1_1") (pintype "passive"))
      (node (ref "U1") (pin "176") (pinfunction "~{RB0}/SDC2_CMD_176") (pintype "bidirectional"))
      (node (ref "U11") (pin "7") (pinfunction "R/~{B}_7") (pintype "bidirectional"))
    )
    (net (code "278") (name "Net-(U11-~{CE})") (class "Default")
      (node (ref "R61") (pin "1") (pinfunction "1_1") (pintype "passive"))
      (node (ref "U1") (pin "2") (pinfunction "~{CE0}_2") (pintype "bidirectional"))
      (node (ref "U11") (pin "9") (pinfunction "~{CE}_9") (pintype "bidirectional"))
    )
    (net (code "279") (name "Net-(U11-~{RE})") (class "Default")
      (node (ref "U1") (pin "1") (pinfunction "~{RE}_1") (pintype "bidirectional"))
      (node (ref "U11") (pin "8") (pinfunction "~{RE}_8") (pintype "bidirectional"))
    )
    (net (code "280") (name "Net-(U11-~{WE})") (class "Default")
      (node (ref "U1") (pin "8") (pinfunction "~{WE}/SPI0_MOSI_8") (pintype "bidirectional"))
      (node (ref "U11") (pin "18") (pinfunction "~{WE}_18") (pintype "bidirectional"))
    )
    (net (code "281") (name "Net-(U11-~{WP})") (class "Default")
      (node (ref "C112") (pin "1") (pinfunction "1_1") (pintype "passive"))
      (node (ref "R62") (pin "1") (pinfunction "1_1") (pintype "passive"))
      (node (ref "U11") (pin "19") (pinfunction "~{WP}_19") (pintype "bidirectional"))
    )
    (net (code "282") (name "Net-(U12A-DM0)") (class "Default")
      (node (ref "R68") (pin "2") (pinfunction "2_2") (pintype "passive"))
      (node (ref "U12") (pin "4") (pinfunction "DM0_4") (pintype "bidirectional"))
    )
    (net (code "283") (name "Net-(U12A-DP0)") (class "Default")
      (node (ref "R67") (pin "2") (pinfunction "2_2") (pintype "passive"))
      (node (ref "R69") (pin "1") (pinfunction "1_1") (pintype "passive"))
      (node (ref "U12") (pin "3") (pinfunction "DP0_3") (pintype "bidirectional"))
    )
    (net (code "284") (name "Net-(U12A-DP0PUR)") (class "Default")
      (node (ref "R69") (pin "2") (pinfunction "2_2") (pintype "passive"))
      (node (ref "U12") (pin "2") (pinfunction "DP0PUR_2") (pintype "bidirectional"))
    )
    (net (code "285") (name "Net-(U12A-XTAL1)") (class "Default")
      (node (ref "C129") (pin "1") (pinfunction "1_1") (pintype "passive"))
      (node (ref "U12") (pin "45") (pinfunction "XTAL1_45") (pintype "bidirectional"))
      (node (ref "Y3") (pin "1") (pinfunction "1_1") (pintype "bidirectional"))
    )
    (net (code "286") (name "Net-(U12A-XTAL2)") (class "Default")
      (node (ref "C130") (pin "1") (pinfunction "1_1") (pintype "passive"))
      (node (ref "U12") (pin "44") (pinfunction "XTAL2_44") (pintype "bidirectional"))
      (node (ref "Y3") (pin "3") (pinfunction "2_3") (pintype "bidirectional"))
    )
    (net (code "287") (name "Net-(U12B-DM1)") (class "Default")
      (node (ref "RN13") (pin "1") (pinfunction "1_1") (pintype "passive"))
      (node (ref "U12") (pin "13") (pinfunction "DM1_13") (pintype "bidirectional"))
      (node (ref "U19") (pin "6") (pinfunction "D0-_6") (pintype "bidirectional"))
    )
    (net (code "288") (name "Net-(U12B-~{OVRCUR1})") (class "Default")
      (node (ref "U12") (pin "12") (pinfunction "~{OVRCUR1}_12") (pintype "bidirectional"))
      (node (ref "U14") (pin "8") (pinfunction "~{OC}_8") (pintype "bidirectional"))
    )
    (net (code "289") (name "Net-(U12B-~{PWRON1})") (class "Default")
      (node (ref "U12") (pin "11") (pinfunction "~{PWRON1}_11") (pintype "bidirectional"))
      (node (ref "U14") (pin "3") (pinfunction "~{EN}_3") (pintype "bidirectional"))
    )
    (net (code "290") (name "Net-(U12C-~{OVRCUR2})") (class "Default")
      (node (ref "U12") (pin "16") (pinfunction "~{OVRCUR2}_16") (pintype "bidirectional"))
      (node (ref "U14") (pin "5") (pinfunction "~{OC}_5") (pintype "bidirectional"))
    )
    (net (code "291") (name "Net-(U12C-~{PWRON2})") (class "Default")
      (node (ref "U12") (pin "15") (pinfunction "~{PWRON2}_15") (pintype "bidirectional"))
      (node (ref "U14") (pin "4") (pinfunction "~{EN}_4") (pintype "bidirectional"))
    )
    (net (code "292") (name "Net-(U12D-DM3)") (class "Default")
      (node (ref "RN14") (pin "1") (pinfunction "1_1") (pintype "passive"))
      (node (ref "U12") (pin "21") (pinfunction "DM3_21") (pintype "bidirectional"))
      (node (ref "U20") (pin "6") (pinfunction "D0-_6") (pintype "bidirectional"))
    )
    (net (code "293") (name "Net-(U12D-~{OVRCUR3})") (class "Default")
      (node (ref "U12") (pin "20") (pinfunction "~{OVRCUR3}_20") (pintype "bidirectional"))
      (node (ref "U15") (pin "8") (pinfunction "~{OC}_8") (pintype "bidirectional"))
    )
    (net (code "294") (name "Net-(U12D-~{PWRON3})") (class "Default")
      (node (ref "U12") (pin "19") (pinfunction "~{PWRON3}_19") (pintype "bidirectional"))
      (node (ref "U15") (pin "3") (pinfunction "~{EN}_3") (pintype "bidirectional"))
    )
    (net (code "295") (name "Net-(U12E-~{OVRCUR4})") (class "Default")
      (node (ref "U12") (pin "25") (pinfunction "~{OVRCUR4}_25") (pintype "bidirectional"))
      (node (ref "U15") (pin "5") (pinfunction "~{OC}_5") (pintype "bidirectional"))
    )
    (net (code "296") (name "Net-(U12E-~{PWRON4})") (class "Default")
      (node (ref "U12") (pin "23") (pinfunction "~{PWRON4}_23") (pintype "bidirectional"))
      (node (ref "U15") (pin "4") (pinfunction "~{EN}_4") (pintype "bidirectional"))
    )
    (net (code "297") (name "Net-(U12F-DM5)") (class "Default")
      (node (ref "RN15") (pin "1") (pinfunction "1_1") (pintype "passive"))
      (node (ref "U12") (pin "30") (pinfunction "DM5_30") (pintype "bidirectional"))
      (node (ref "U21") (pin "6") (pinfunction "D0-_6") (pintype "bidirectional"))
    )
    (net (code "298") (name "Net-(U12F-~{OVRCUR5})") (class "Default")
      (node (ref "U12") (pin "29") (pinfunction "~{OVRCUR5}_29") (pintype "bidirectional"))
      (node (ref "U16") (pin "8") (pinfunction "~{OC}_8") (pintype "bidirectional"))
    )
    (net (code "299") (name "Net-(U12F-~{PWRON5})") (class "Default")
      (node (ref "U12") (pin "28") (pinfunction "~{PWRON5}_28") (pintype "bidirectional"))
      (node (ref "U16") (pin "3") (pinfunction "~{EN}_3") (pintype "bidirectional"))
    )
    (net (code "300") (name "Net-(U12G-~{OVRCUR6})") (class "Default")
      (node (ref "U12") (pin "33") (pinfunction "~{OVRCUR6}_33") (pintype "bidirectional"))
      (node (ref "U16") (pin "5") (pinfunction "~{OC}_5") (pintype "bidirectional"))
    )
    (net (code "301") (name "Net-(U12G-~{PWRON6})") (class "Default")
      (node (ref "U12") (pin "32") (pinfunction "~{PWRON6}_32") (pintype "bidirectional"))
      (node (ref "U16") (pin "4") (pinfunction "~{EN}_4") (pintype "bidirectional"))
    )
    (net (code "302") (name "OTG_PWR") (class "Default")
      (node (ref "R12") (pin "2") (pinfunction "2_2") (pintype "passive"))
      (node (ref "U2") (pin "31") (pinfunction "VBUS_31") (pintype "bidirectional"))
    )
    (net (code "303") (name "PWRON") (class "Default")
      (node (ref "C27") (pin "1") (pinfunction "1_1") (pintype "passive"))
      (node (ref "R21") (pin "1") (pinfunction "1_1") (pintype "passive"))
      (node (ref "U2") (pin "47") (pinfunction "PWRON_47") (pintype "bidirectional"))
    )
    (net (code "304") (name "SCL") (class "Default")
      (node (ref "J5") (pin "15") (pinfunction "SCL_15") (pintype "bidirectional"))
      (node (ref "R14") (pin "1") (pinfunction "1_1") (pintype "passive"))
      (node (ref "U1") (pin "101") (pinfunction "TWI0_SCK_101") (pintype "bidirectional"))
      (node (ref "U2") (pin "2") (pinfunction "SCK_2") (pintype "bidirectional"))
      (node (ref "U9") (pin "15") (pinfunction "BSEL/SCL_15") (pintype "bidirectional"))
    )
    (net (code "305") (name "SDA") (class "Default")
      (node (ref "J5") (pin "16") (pinfunction "SDA_16") (pintype "bidirectional"))
      (node (ref "R13") (pin "1") (pinfunction "1_1") (pintype "passive"))
      (node (ref "U1") (pin "102") (pinfunction "TWI0_SDA_102") (pintype "bidirectional"))
      (node (ref "U2") (pin "1") (pinfunction "SDA_1") (pintype "bidirectional"))
      (node (ref "U9") (pin "14") (pinfunction "DSEL/SDA_14") (pintype "bidirectional"))
    )
    (net (code "306") (name "SDC0_CD") (class "Default")
      (node (ref "J3") (pin "CD1") (pinfunction "CD_CD1") (pintype "bidirectional"))
      (node (ref "R29") (pin "1") (pinfunction "1_1") (pintype "passive"))
      (node (ref "U1") (pin "155") (pinfunction "PG0/EINT0_155") (pintype "bidirectional"))
    )
    (net (code "307") (name "UART1_RX") (class "Default")
      (node (ref "U1") (pin "165") (pinfunction "CSI_D7/UART1_RX_165") (pintype "bidirectional"))
      (node (ref "U13") (pin "4") (pinfunction "TX_4") (pintype "bidirectional"))
      (node (ref "U4") (pin "1") (pinfunction "TX_1") (pintype "bidirectional"))
    )
    (net (code "308") (name "UART1_TX") (class "Default")
      (node (ref "U1") (pin "166") (pinfunction "CSI_D6/UART1_TX_166") (pintype "bidirectional"))
      (node (ref "U13") (pin "3") (pinfunction "RX_3") (pintype "bidirectional"))
      (node (ref "U4") (pin "2") (pinfunction "RX_2") (pintype "bidirectional"))
    )
    (net (code "309") (name "UBOOT") (class "Default")
      (node (ref "R6") (pin "2") (pinfunction "2_2") (pintype "passive"))
      (node (ref "S5") (pin "P$2") (pinfunction "P$2_P$2") (pintype "bidirectional"))
      (node (ref "U1") (pin "157") (pinfunction "UBOOT_157") (pintype "bidirectional"))
    )
    (net (code "310") (name "VINT") (class "Default")
      (node (ref "C26") (pin "1") (pinfunction "1_1") (pintype "passive"))
      (node (ref "U2") (pin "26") (pinfunction "VINT_26") (pintype "bidirectional"))
      (node (ref "U2") (pin "27") (pinfunction "LDO1SET_27") (pintype "bidirectional"))
    )
    (net (code "311") (name "VUSBDET") (class "Default")
      (node (ref "R16") (pin "1") (pinfunction "1_1") (pintype "passive"))
      (node (ref "R17") (pin "2") (pinfunction "2_2") (pintype "passive"))
      (node (ref "U1") (pin "154") (pinfunction "PG1/EINT1_154") (pintype "bidirectional"))
    )
    (net (code "312") (name "VUSBFLG") (class "Default")
      (node (ref "R15") (pin "1") (pinfunction "1_1") (pintype "passive"))
      (node (ref "U1") (pin "14") (pinfunction "PG11/SPI1_MOSI/UART3_CTS/EINT11_14") (pintype "bidirectional"))
      (node (ref "U3") (pin "5") (pinfunction "FLG_5") (pintype "bidirectional"))
    )
    (net (code "313") (name "unconnected-(J2-PAD1-PadNC1)") (class "Default")
      (node (ref "J2") (pin "NC1") (pinfunction "PAD1_NC1") (pintype "bidirectional"))
    )
    (net (code "314") (name "unconnected-(J2-PAD2-PadNC2)") (class "Default")
      (node (ref "J2") (pin "NC2") (pinfunction "PAD2_NC2") (pintype "bidirectional"))
    )
    (net (code "315") (name "unconnected-(J5-RESERVED-Pad14)") (class "Default")
      (node (ref "J5") (pin "14") (pinfunction "RESERVED_14") (pintype "bidirectional"))
    )
    (net (code "316") (name "unconnected-(R63-Pad1)") (class "Default")
      (node (ref "R63") (pin "1") (pinfunction "1_1") (pintype "passive"))
    )
    (net (code "317") (name "unconnected-(R63-Pad2)") (class "Default")
      (node (ref "R63") (pin "2") (pinfunction "2_2") (pintype "passive"))
    )
    (net (code "318") (name "unconnected-(R64-Pad1)") (class "Default")
      (node (ref "R64") (pin "1") (pinfunction "1_1") (pintype "passive"))
    )
    (net (code "319") (name "unconnected-(R64-Pad2)") (class "Default")
      (node (ref "R64") (pin "2") (pinfunction "2_2") (pintype "passive"))
    )
    (net (code "320") (name "unconnected-(U$4-NC-PadA3)") (class "Default")
      (node (ref "U$4") (pin "A3") (pinfunction "NC_A3") (pintype "bidirectional"))
    )
    (net (code "321") (name "unconnected-(U$4-NC{slash}A15-PadJ7)") (class "Default")
      (node (ref "U$4") (pin "J7") (pinfunction "NC/A15_J7") (pintype "bidirectional"))
    )
    (net (code "322") (name "unconnected-(U$4-NC{slash}CKE1-PadF9)") (class "Default")
      (node (ref "U$4") (pin "F9") (pinfunction "NC/CKE1_F9") (pintype "bidirectional"))
    )
    (net (code "323") (name "unconnected-(U$4-NC{slash}ODT1-PadF1)") (class "Default")
      (node (ref "U$4") (pin "F1") (pinfunction "NC/ODT1_F1") (pintype "bidirectional"))
    )
    (net (code "324") (name "unconnected-(U$4-NC{slash}ZQ1-PadH9)") (class "Default")
      (node (ref "U$4") (pin "H9") (pinfunction "NC/ZQ1_H9") (pintype "bidirectional"))
    )
    (net (code "325") (name "unconnected-(U$4-NC{slash}~{CS1}-PadH1)") (class "Default")
      (node (ref "U$4") (pin "H1") (pinfunction "NC/~{CS1}_H1") (pintype "bidirectional"))
    )
    (net (code "326") (name "unconnected-(U$4-NF{slash}~{TDQS}-PadA7)") (class "Default")
      (node (ref "U$4") (pin "A7") (pinfunction "NF/~{TDQS}_A7") (pintype "bidirectional"))
    )
    (net (code "327") (name "unconnected-(U$5-NC-PadA3)") (class "Default")
      (node (ref "U$5") (pin "A3") (pinfunction "NC_A3") (pintype "bidirectional"))
    )
    (net (code "328") (name "unconnected-(U$5-NC{slash}A15-PadJ7)") (class "Default")
      (node (ref "U$5") (pin "J7") (pinfunction "NC/A15_J7") (pintype "bidirectional"))
    )
    (net (code "329") (name "unconnected-(U$5-NC{slash}CKE1-PadF9)") (class "Default")
      (node (ref "U$5") (pin "F9") (pinfunction "NC/CKE1_F9") (pintype "bidirectional"))
    )
    (net (code "330") (name "unconnected-(U$5-NC{slash}ODT1-PadF1)") (class "Default")
      (node (ref "U$5") (pin "F1") (pinfunction "NC/ODT1_F1") (pintype "bidirectional"))
    )
    (net (code "331") (name "unconnected-(U$5-NC{slash}ZQ1-PadH9)") (class "Default")
      (node (ref "U$5") (pin "H9") (pinfunction "NC/ZQ1_H9") (pintype "bidirectional"))
    )
    (net (code "332") (name "unconnected-(U$5-NC{slash}~{CS1}-PadH1)") (class "Default")
      (node (ref "U$5") (pin "H1") (pinfunction "NC/~{CS1}_H1") (pintype "bidirectional"))
    )
    (net (code "333") (name "unconnected-(U$5-NF{slash}~{TDQS}-PadA7)") (class "Default")
      (node (ref "U$5") (pin "A7") (pinfunction "NF/~{TDQS}_A7") (pintype "bidirectional"))
    )
    (net (code "334") (name "unconnected-(U1B-MIC_IN1-Pad84)") (class "Default")
      (node (ref "U1") (pin "84") (pinfunction "MIC_IN1_84") (pintype "bidirectional"))
    )
    (net (code "335") (name "unconnected-(U1B-V_MIC-Pad85)") (class "Default")
      (node (ref "U1") (pin "85") (pinfunction "V_MIC_85") (pintype "bidirectional"))
    )
    (net (code "336") (name "unconnected-(U1C-CSI_D0{slash}SDC2_D0-Pad174)") (class "Default")
      (node (ref "U1") (pin "174") (pinfunction "CSI_D0/SDC2_D0_174") (pintype "bidirectional"))
    )
    (net (code "337") (name "unconnected-(U1C-CSI_D1{slash}SDC2_D1-Pad172)") (class "Default")
      (node (ref "U1") (pin "172") (pinfunction "CSI_D1/SDC2_D1_172") (pintype "bidirectional"))
    )
    (net (code "338") (name "unconnected-(U1C-CSI_D2{slash}SDC2_D2-Pad171)") (class "Default")
      (node (ref "U1") (pin "171") (pinfunction "CSI_D2/SDC2_D2_171") (pintype "bidirectional"))
    )
    (net (code "339") (name "unconnected-(U1C-CSI_D3{slash}SDC2_D3-Pad170)") (class "Default")
      (node (ref "U1") (pin "170") (pinfunction "CSI_D3/SDC2_D3_170") (pintype "bidirectional"))
    )
    (net (code "340") (name "unconnected-(U1C-CSI_D4{slash}SDC2_CMD-Pad168)") (class "Default")
      (node (ref "U1") (pin "168") (pinfunction "CSI_D4/SDC2_CMD_168") (pintype "bidirectional"))
    )
    (net (code "341") (name "unconnected-(U1C-CSI_D5{slash}SDC2_CLK-Pad167)") (class "Default")
      (node (ref "U1") (pin "167") (pinfunction "CSI_D5/SDC2_CLK_167") (pintype "bidirectional"))
    )
    (net (code "342") (name "unconnected-(U1E-~{CE1}{slash}SPI0_CS0-Pad3)") (class "Default")
      (node (ref "U1") (pin "3") (pinfunction "~{CE1}/SPI0_CS0_3") (pintype "bidirectional"))
    )
    (net (code "343") (name "unconnected-(U1E-~{QDS}-Pad162)") (class "Default")
      (node (ref "U1") (pin "162") (pinfunction "~{QDS}_162") (pintype "bidirectional"))
    )
    (net (code "344") (name "unconnected-(U1E-~{RB1}{slash}SDC2_CLK-Pad175)") (class "Default")
      (node (ref "U1") (pin "175") (pinfunction "~{RB1}/SDC2_CLK_175") (pintype "bidirectional"))
    )
    (net (code "345") (name "unconnected-(U1I-DZQ-Pad17)") (class "Default")
      (node (ref "U1") (pin "17") (pinfunction "DZQ_17") (pintype "bidirectional"))
    )
    (net (code "346") (name "unconnected-(U1I-PB10{slash}EINT24-Pad10)") (class "Default")
      (node (ref "U1") (pin "10") (pinfunction "PB10/EINT24_10") (pintype "bidirectional"))
    )
    (net (code "347") (name "unconnected-(U1I-PB17-Pad161)") (class "Default")
      (node (ref "U1") (pin "161") (pinfunction "PB17_161") (pintype "bidirectional"))
    )
    (net (code "348") (name "unconnected-(U1I-PB18-Pad160)") (class "Default")
      (node (ref "U1") (pin "160") (pinfunction "PB18_160") (pintype "bidirectional"))
    )
    (net (code "349") (name "unconnected-(U1I-PG2{slash}EINT2-Pad153)") (class "Default")
      (node (ref "U1") (pin "153") (pinfunction "PG2/EINT2_153") (pintype "bidirectional"))
    )
    (net (code "350") (name "unconnected-(U1I-PG3{slash}UART1_TX{slash}EINT3-Pad152)") (class "Default")
      (node (ref "U1") (pin "152") (pinfunction "PG3/UART1_TX/EINT3_152") (pintype "bidirectional"))
    )
    (net (code "351") (name "unconnected-(U1I-PG4{slash}UART1_RX{slash}EINT4-Pad151)") (class "Default")
      (node (ref "U1") (pin "151") (pinfunction "PG4/UART1_RX/EINT4_151") (pintype "bidirectional"))
    )
    (net (code "352") (name "unconnected-(U1I-PG9{slash}SPI1_CS0{slash}UART3_TX{slash}EINT9-Pad12)") (class "Default")
      (node (ref "U1") (pin "12") (pinfunction "PG9/SPI1_CS0/UART3_TX/EINT9_12") (pintype "bidirectional"))
    )
    (net (code "353") (name "unconnected-(U1I-PG10{slash}SPI1_CLK{slash}UART3_RX{slash}EINT10-Pad13)") (class "Default")
      (node (ref "U1") (pin "13") (pinfunction "PG10/SPI1_CLK/UART3_RX/EINT10_13") (pintype "bidirectional"))
    )
    (net (code "354") (name "unconnected-(U1I-SVREF-Pad18)") (class "Default")
      (node (ref "U1") (pin "18") (pinfunction "SVREF_18") (pintype "bidirectional"))
    )
    (net (code "355") (name "unconnected-(U2-BACKUP-Pad30)") (class "Default")
      (node (ref "U2") (pin "30") (pinfunction "BACKUP_30") (pintype "bidirectional"))
    )
    (net (code "356") (name "unconnected-(U2-DC3SET-Pad29)") (class "Default")
      (node (ref "U2") (pin "29") (pinfunction "DC3SET_29") (pintype "bidirectional"))
    )
    (net (code "357") (name "unconnected-(U2-GPIO0-Pad19)") (class "Default")
      (node (ref "U2") (pin "19") (pinfunction "GPIO0_19") (pintype "bidirectional"))
    )
    (net (code "358") (name "unconnected-(U2-GPIO1-Pad18)") (class "Default")
      (node (ref "U2") (pin "18") (pinfunction "GPIO1_18") (pintype "bidirectional"))
    )
    (net (code "359") (name "unconnected-(U2-GPIO2-Pad5)") (class "Default")
      (node (ref "U2") (pin "5") (pinfunction "GPIO2_5") (pintype "bidirectional"))
    )
    (net (code "360") (name "unconnected-(U2-GPIO3-Pad3)") (class "Default")
      (node (ref "U2") (pin "3") (pinfunction "GPIO3_3") (pintype "bidirectional"))
    )
    (net (code "361") (name "unconnected-(U2-LDO1-Pad28)") (class "Default")
      (node (ref "U2") (pin "28") (pinfunction "LDO1_28") (pintype "bidirectional"))
    )
    (net (code "362") (name "unconnected-(U2-LDO4-Pad11)") (class "Default")
      (node (ref "U2") (pin "11") (pinfunction "LDO4_11") (pintype "bidirectional"))
    )
    (net (code "363") (name "unconnected-(U4-AIO0-Pad9)") (class "Default")
      (node (ref "U4") (pin "9") (pinfunction "AIO0_9") (pintype "bidirectional"))
    )
    (net (code "364") (name "unconnected-(U4-AIO1-Pad10)") (class "Default")
      (node (ref "U4") (pin "10") (pinfunction "AIO1_10") (pintype "bidirectional"))
    )
    (net (code "365") (name "unconnected-(U4-CSB-Pad16)") (class "Default")
      (node (ref "U4") (pin "16") (pinfunction "CSB_16") (pintype "bidirectional"))
    )
    (net (code "366") (name "unconnected-(U4-CTS-Pad3)") (class "Default")
      (node (ref "U4") (pin "3") (pinfunction "CTS_3") (pintype "bidirectional"))
    )
    (net (code "367") (name "unconnected-(U4-D+-Pad20)") (class "Default")
      (node (ref "U4") (pin "20") (pinfunction "D+_20") (pintype "bidirectional"))
    )
    (net (code "368") (name "unconnected-(U4-D--Pad15)") (class "Default")
      (node (ref "U4") (pin "15") (pinfunction "D-_15") (pintype "bidirectional"))
    )
    (net (code "369") (name "unconnected-(U4-MISO-Pad18)") (class "Default")
      (node (ref "U4") (pin "18") (pinfunction "MISO_18") (pintype "bidirectional"))
    )
    (net (code "370") (name "unconnected-(U4-MOSI-Pad17)") (class "Default")
      (node (ref "U4") (pin "17") (pinfunction "MOSI_17") (pintype "bidirectional"))
    )
    (net (code "371") (name "unconnected-(U4-PCM_CLK-Pad5)") (class "Default")
      (node (ref "U4") (pin "5") (pinfunction "PCM_CLK_5") (pintype "bidirectional"))
    )
    (net (code "372") (name "unconnected-(U4-PCM_IN-Pad7)") (class "Default")
      (node (ref "U4") (pin "7") (pinfunction "PCM_IN_7") (pintype "bidirectional"))
    )
    (net (code "373") (name "unconnected-(U4-PCM_OUT-Pad6)") (class "Default")
      (node (ref "U4") (pin "6") (pinfunction "PCM_OUT_6") (pintype "bidirectional"))
    )
    (net (code "374") (name "unconnected-(U4-PCM_SYNC-Pad8)") (class "Default")
      (node (ref "U4") (pin "8") (pinfunction "PCM_SYNC_8") (pintype "bidirectional"))
    )
    (net (code "375") (name "unconnected-(U4-PIO0-Pad23)") (class "Default")
      (node (ref "U4") (pin "23") (pinfunction "PIO0_23") (pintype "bidirectional"))
    )
    (net (code "376") (name "unconnected-(U4-PIO1-Pad24)") (class "Default")
      (node (ref "U4") (pin "24") (pinfunction "PIO1_24") (pintype "bidirectional"))
    )
    (net (code "377") (name "unconnected-(U4-PIO2-Pad25)") (class "Default")
      (node (ref "U4") (pin "25") (pinfunction "PIO2_25") (pintype "bidirectional"))
    )
    (net (code "378") (name "unconnected-(U4-PIO3-Pad26)") (class "Default")
      (node (ref "U4") (pin "26") (pinfunction "PIO3_26") (pintype "bidirectional"))
    )
    (net (code "379") (name "unconnected-(U4-PIO4-Pad27)") (class "Default")
      (node (ref "U4") (pin "27") (pinfunction "PIO4_27") (pintype "bidirectional"))
    )
    (net (code "380") (name "unconnected-(U4-PIO5-Pad28)") (class "Default")
      (node (ref "U4") (pin "28") (pinfunction "PIO5_28") (pintype "bidirectional"))
    )
    (net (code "381") (name "unconnected-(U4-PIO6-Pad29)") (class "Default")
      (node (ref "U4") (pin "29") (pinfunction "PIO6_29") (pintype "bidirectional"))
    )
    (net (code "382") (name "unconnected-(U4-PIO7-Pad30)") (class "Default")
      (node (ref "U4") (pin "30") (pinfunction "PIO7_30") (pintype "bidirectional"))
    )
    (net (code "383") (name "unconnected-(U4-PIO8-Pad31)") (class "Default")
      (node (ref "U4") (pin "31") (pinfunction "PIO8_31") (pintype "bidirectional"))
    )
    (net (code "384") (name "unconnected-(U4-PIO9-Pad32)") (class "Default")
      (node (ref "U4") (pin "32") (pinfunction "PIO9_32") (pintype "bidirectional"))
    )
    (net (code "385") (name "unconnected-(U4-PIO10-Pad33)") (class "Default")
      (node (ref "U4") (pin "33") (pinfunction "PIO10_33") (pintype "bidirectional"))
    )
    (net (code "386") (name "unconnected-(U4-RESET-Pad11)") (class "Default")
      (node (ref "U4") (pin "11") (pinfunction "RESET_11") (pintype "bidirectional"))
    )
    (net (code "387") (name "unconnected-(U4-RTS-Pad4)") (class "Default")
      (node (ref "U4") (pin "4") (pinfunction "RTS_4") (pintype "bidirectional"))
    )
    (net (code "388") (name "unconnected-(U4-SCK-Pad19)") (class "Default")
      (node (ref "U4") (pin "19") (pinfunction "SCK_19") (pintype "bidirectional"))
    )
    (net (code "389") (name "unconnected-(U10-CLKOUT-Pad27)") (class "Default")
      (node (ref "U10") (pin "27") (pinfunction "CLKOUT_27") (pintype "bidirectional"))
    )
    (net (code "390") (name "unconnected-(U11-NC-Pad1)") (class "Default")
      (node (ref "U11") (pin "1") (pinfunction "NC_1") (pintype "bidirectional"))
    )
    (net (code "391") (name "unconnected-(U11-NC-Pad2)") (class "Default")
      (node (ref "U11") (pin "2") (pinfunction "NC_2") (pintype "bidirectional"))
    )
    (net (code "392") (name "unconnected-(U11-NC-Pad3)") (class "Default")
      (node (ref "U11") (pin "3") (pinfunction "NC_3") (pintype "bidirectional"))
    )
    (net (code "393") (name "unconnected-(U11-NC-Pad4)") (class "Default")
      (node (ref "U11") (pin "4") (pinfunction "NC_4") (pintype "bidirectional"))
    )
    (net (code "394") (name "unconnected-(U11-NC-Pad5)") (class "Default")
      (node (ref "U11") (pin "5") (pinfunction "NC_5") (pintype "bidirectional"))
    )
    (net (code "395") (name "unconnected-(U11-NC-Pad6)") (class "Default")
      (node (ref "U11") (pin "6") (pinfunction "NC_6") (pintype "bidirectional"))
    )
    (net (code "396") (name "unconnected-(U11-NC-Pad10)") (class "Default")
      (node (ref "U11") (pin "10") (pinfunction "NC_10") (pintype "bidirectional"))
    )
    (net (code "397") (name "unconnected-(U11-NC-Pad11)") (class "Default")
      (node (ref "U11") (pin "11") (pinfunction "NC_11") (pintype "bidirectional"))
    )
    (net (code "398") (name "unconnected-(U11-NC-Pad14)") (class "Default")
      (node (ref "U11") (pin "14") (pinfunction "NC_14") (pintype "bidirectional"))
    )
    (net (code "399") (name "unconnected-(U11-NC-Pad15)") (class "Default")
      (node (ref "U11") (pin "15") (pinfunction "NC_15") (pintype "bidirectional"))
    )
    (net (code "400") (name "unconnected-(U11-NC-Pad20)") (class "Default")
      (node (ref "U11") (pin "20") (pinfunction "NC_20") (pintype "bidirectional"))
    )
    (net (code "401") (name "unconnected-(U11-NC-Pad21)") (class "Default")
      (node (ref "U11") (pin "21") (pinfunction "NC_21") (pintype "bidirectional"))
    )
    (net (code "402") (name "unconnected-(U11-NC-Pad22)") (class "Default")
      (node (ref "U11") (pin "22") (pinfunction "NC_22") (pintype "bidirectional"))
    )
    (net (code "403") (name "unconnected-(U11-NC-Pad23)") (class "Default")
      (node (ref "U11") (pin "23") (pinfunction "NC_23") (pintype "bidirectional"))
    )
    (net (code "404") (name "unconnected-(U11-NC-Pad24)") (class "Default")
      (node (ref "U11") (pin "24") (pinfunction "NC_24") (pintype "bidirectional"))
    )
    (net (code "405") (name "unconnected-(U11-NC-Pad25)") (class "Default")
      (node (ref "U11") (pin "25") (pinfunction "NC_25") (pintype "bidirectional"))
    )
    (net (code "406") (name "unconnected-(U11-NC-Pad26)") (class "Default")
      (node (ref "U11") (pin "26") (pinfunction "NC_26") (pintype "bidirectional"))
    )
    (net (code "407") (name "unconnected-(U11-NC-Pad27)") (class "Default")
      (node (ref "U11") (pin "27") (pinfunction "NC_27") (pintype "bidirectional"))
    )
    (net (code "408") (name "unconnected-(U11-NC-Pad28)") (class "Default")
      (node (ref "U11") (pin "28") (pinfunction "NC_28") (pintype "bidirectional"))
    )
    (net (code "409") (name "unconnected-(U11-NC-Pad33)") (class "Default")
      (node (ref "U11") (pin "33") (pinfunction "NC_33") (pintype "bidirectional"))
    )
    (net (code "410") (name "unconnected-(U11-NC-Pad34)") (class "Default")
      (node (ref "U11") (pin "34") (pinfunction "NC_34") (pintype "bidirectional"))
    )
    (net (code "411") (name "unconnected-(U11-NC-Pad35)") (class "Default")
      (node (ref "U11") (pin "35") (pinfunction "NC_35") (pintype "bidirectional"))
    )
    (net (code "412") (name "unconnected-(U11-NC-Pad38)") (class "Default")
      (node (ref "U11") (pin "38") (pinfunction "NC_38") (pintype "bidirectional"))
    )
    (net (code "413") (name "unconnected-(U11-NC-Pad39)") (class "Default")
      (node (ref "U11") (pin "39") (pinfunction "NC_39") (pintype "bidirectional"))
    )
    (net (code "414") (name "unconnected-(U11-NC-Pad40)") (class "Default")
      (node (ref "U11") (pin "40") (pinfunction "NC_40") (pintype "bidirectional"))
    )
    (net (code "415") (name "unconnected-(U11-NC-Pad45)") (class "Default")
      (node (ref "U11") (pin "45") (pinfunction "NC_45") (pintype "bidirectional"))
    )
    (net (code "416") (name "unconnected-(U11-NC-Pad46)") (class "Default")
      (node (ref "U11") (pin "46") (pinfunction "NC_46") (pintype "bidirectional"))
    )
    (net (code "417") (name "unconnected-(U11-NC-Pad47)") (class "Default")
      (node (ref "U11") (pin "47") (pinfunction "NC_47") (pintype "bidirectional"))
    )
    (net (code "418") (name "unconnected-(U11-NC-Pad48)") (class "Default")
      (node (ref "U11") (pin "48") (pinfunction "NC_48") (pintype "bidirectional"))
    )
    (net (code "419") (name "unconnected-(U12A-EECLK-Pad7)") (class "Default")
      (node (ref "U12") (pin "7") (pinfunction "EECLK_7") (pintype "bidirectional"))
    )
    (net (code "420") (name "unconnected-(U12A-HUBCFG-Pad40)") (class "Default")
      (node (ref "U12") (pin "40") (pinfunction "HUBCFG_40") (pintype "bidirectional"))
    )
    (net (code "421") (name "unconnected-(U12A-PORTDIS-Pad42)") (class "Default")
      (node (ref "U12") (pin "42") (pinfunction "PORTDIS_42") (pintype "bidirectional"))
    )
    (net (code "422") (name "unconnected-(U12A-PORTPWR-Pad41)") (class "Default")
      (node (ref "U12") (pin "41") (pinfunction "PORTPWR_41") (pintype "bidirectional"))
    )
    (net (code "423") (name "unconnected-(U12A-SUSPND-Pad1)") (class "Default")
      (node (ref "U12") (pin "1") (pinfunction "SUSPND_1") (pintype "bidirectional"))
    )
    (net (code "424") (name "unconnected-(U12H-DM7-Pad38)") (class "Default")
      (node (ref "U12") (pin "38") (pinfunction "DM7_38") (pintype "bidirectional"))
    )
    (net (code "425") (name "unconnected-(U12H-DP7-Pad39)") (class "Default")
      (node (ref "U12") (pin "39") (pinfunction "DP7_39") (pintype "bidirectional"))
    )
    (net (code "426") (name "unconnected-(U12H-~{OVRCUR7}-Pad37)") (class "Default")
      (node (ref "U12") (pin "37") (pinfunction "~{OVRCUR7}_37") (pintype "bidirectional"))
    )
    (net (code "427") (name "unconnected-(U12H-~{PWRON7}-Pad36)") (class "Default")
      (node (ref "U12") (pin "36") (pinfunction "~{PWRON7}_36") (pintype "bidirectional"))
    )
  )
)
